# Sheet1.net
KiCad netlist of a schematic drawn in Altium Designer
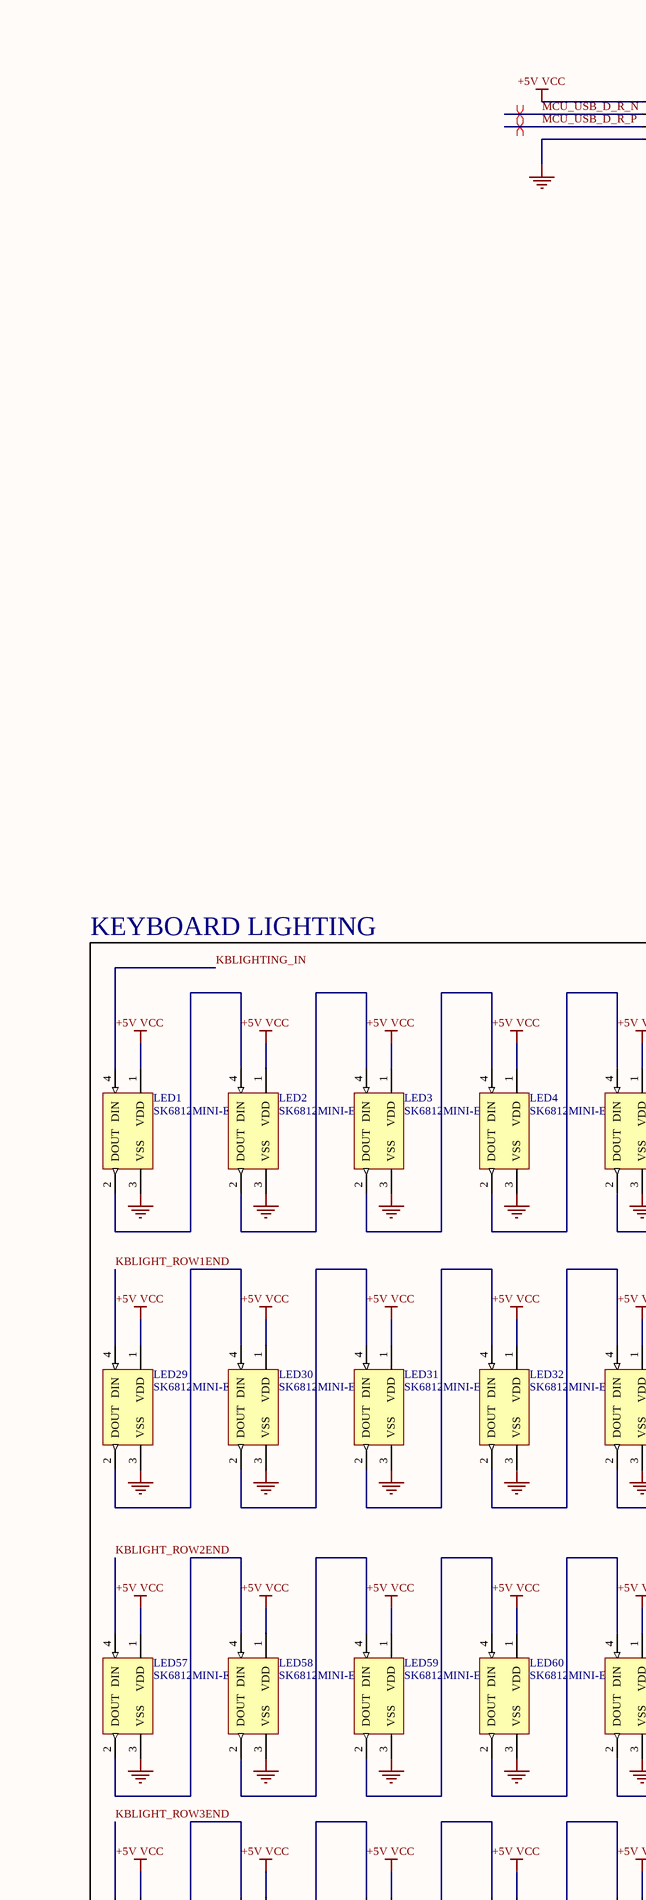
[diagram p0: Sheet1.SchDoc, top left]
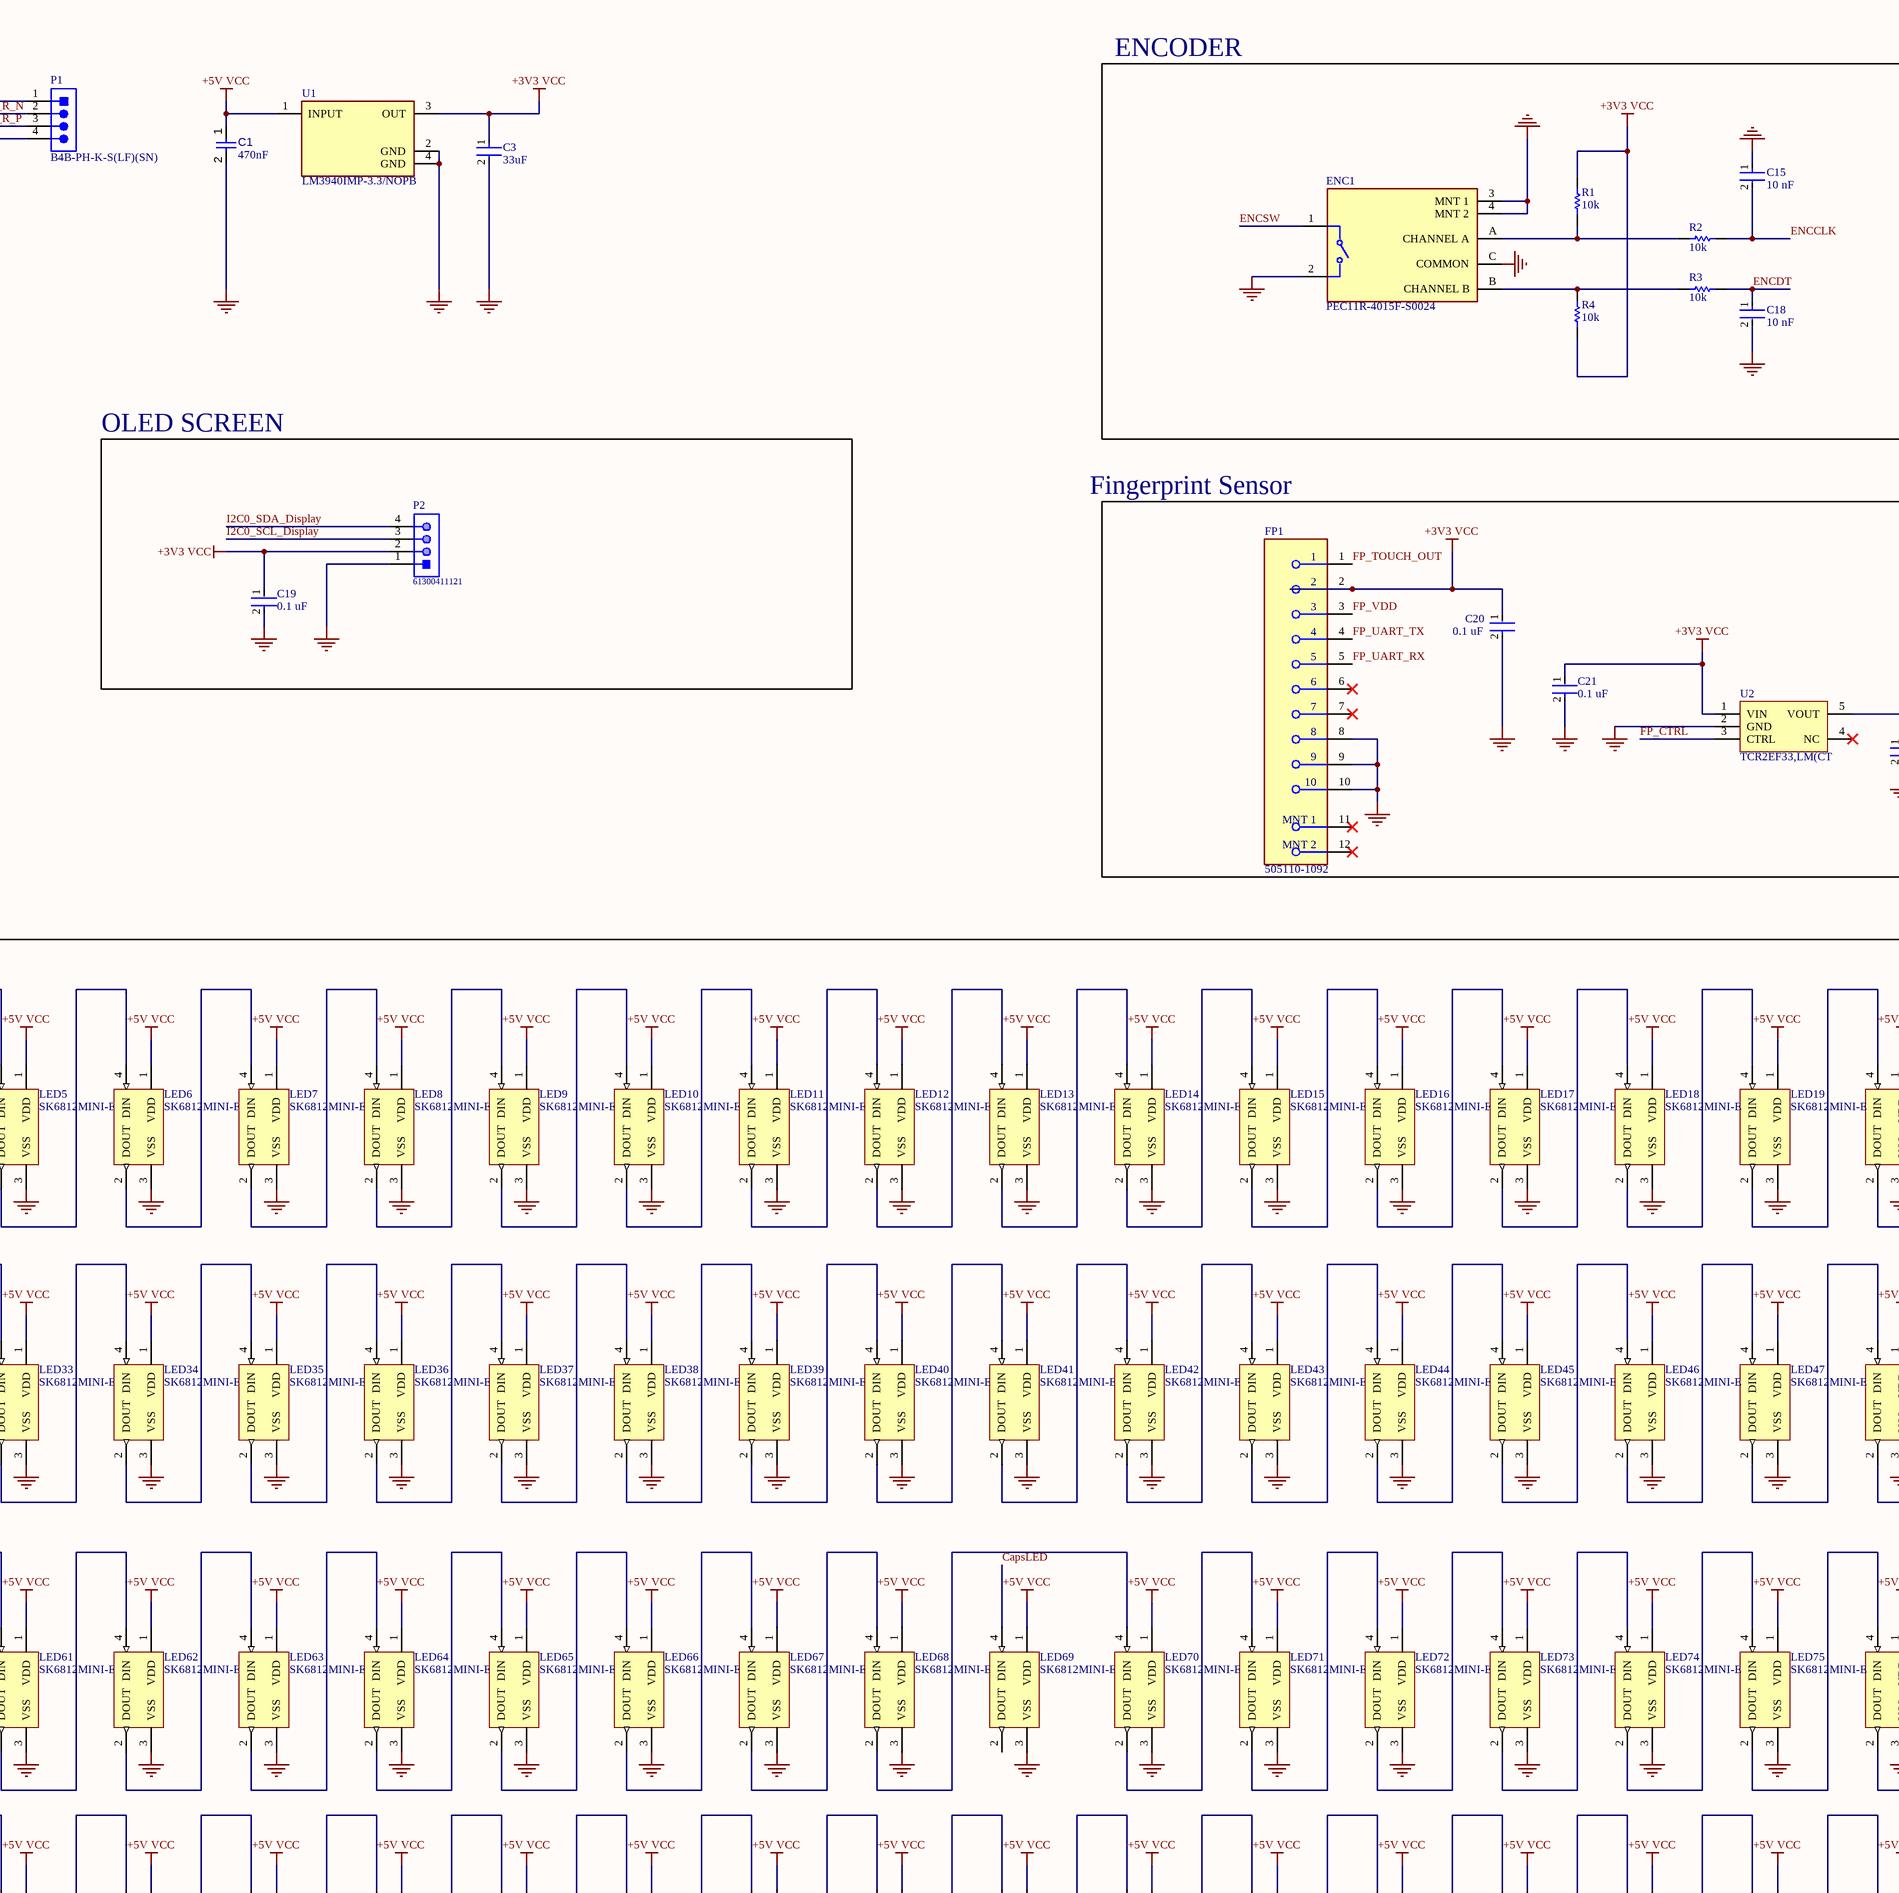
[diagram p1: Sheet1.SchDoc, top middle]
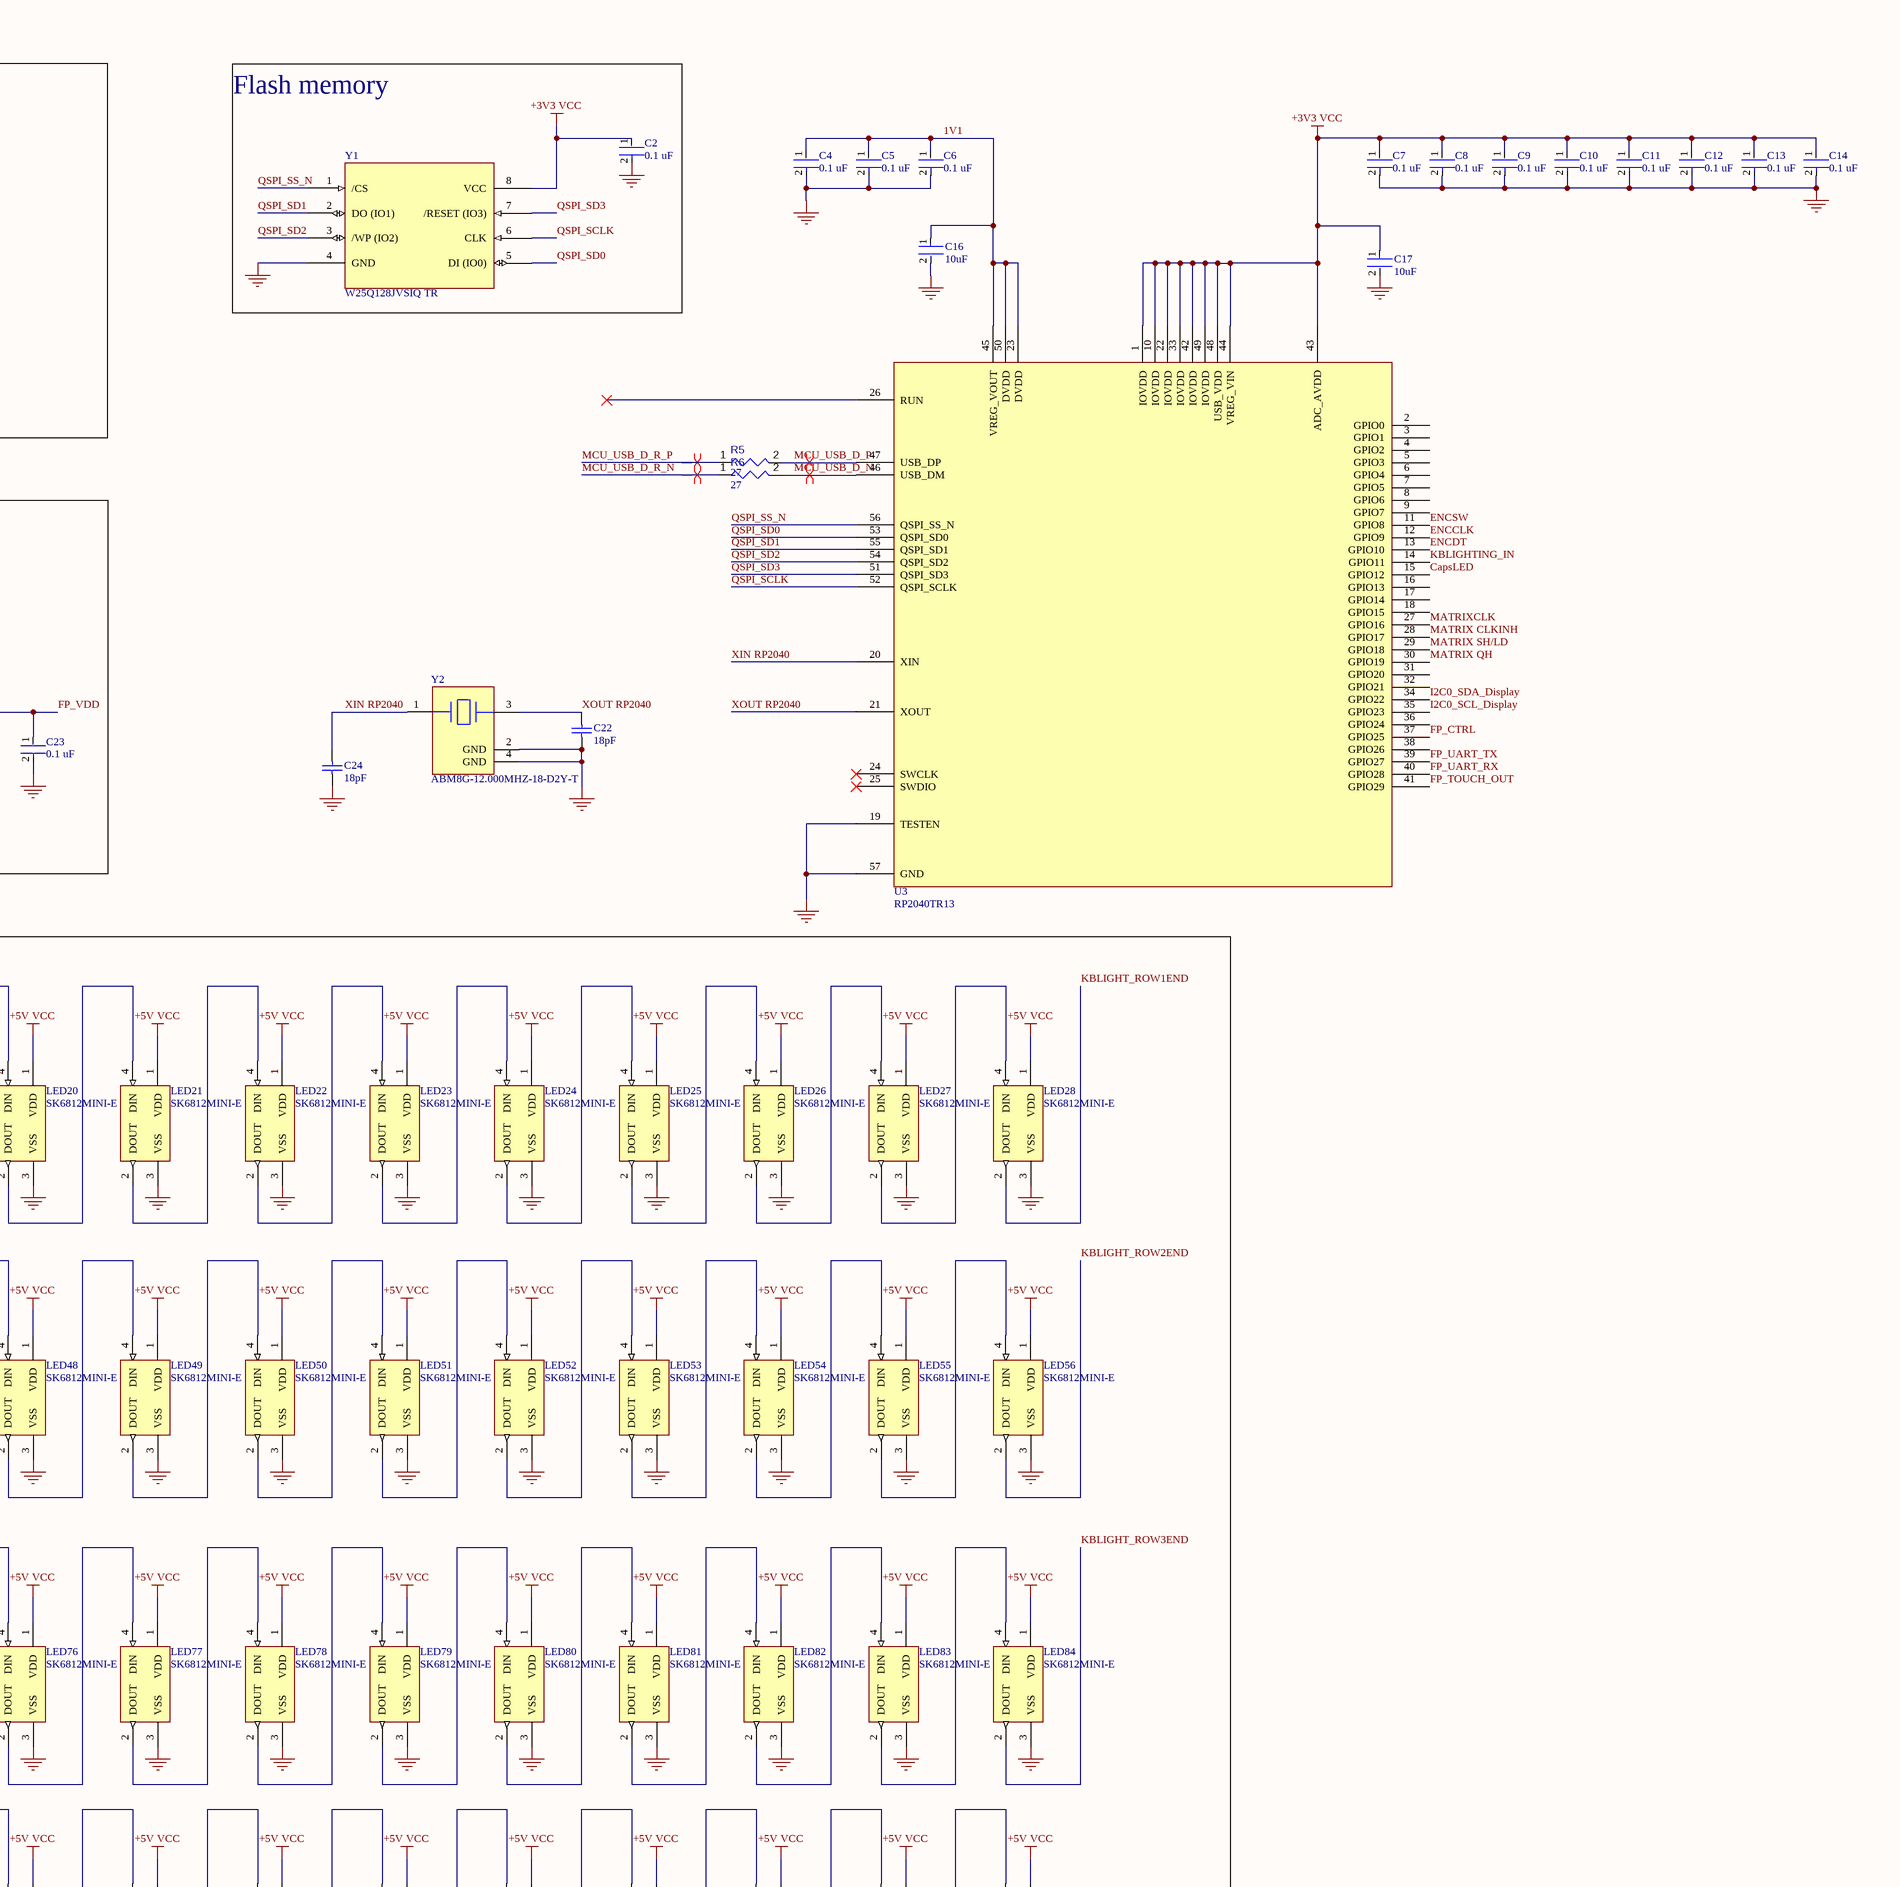
[diagram p2: Sheet1.SchDoc, top right]
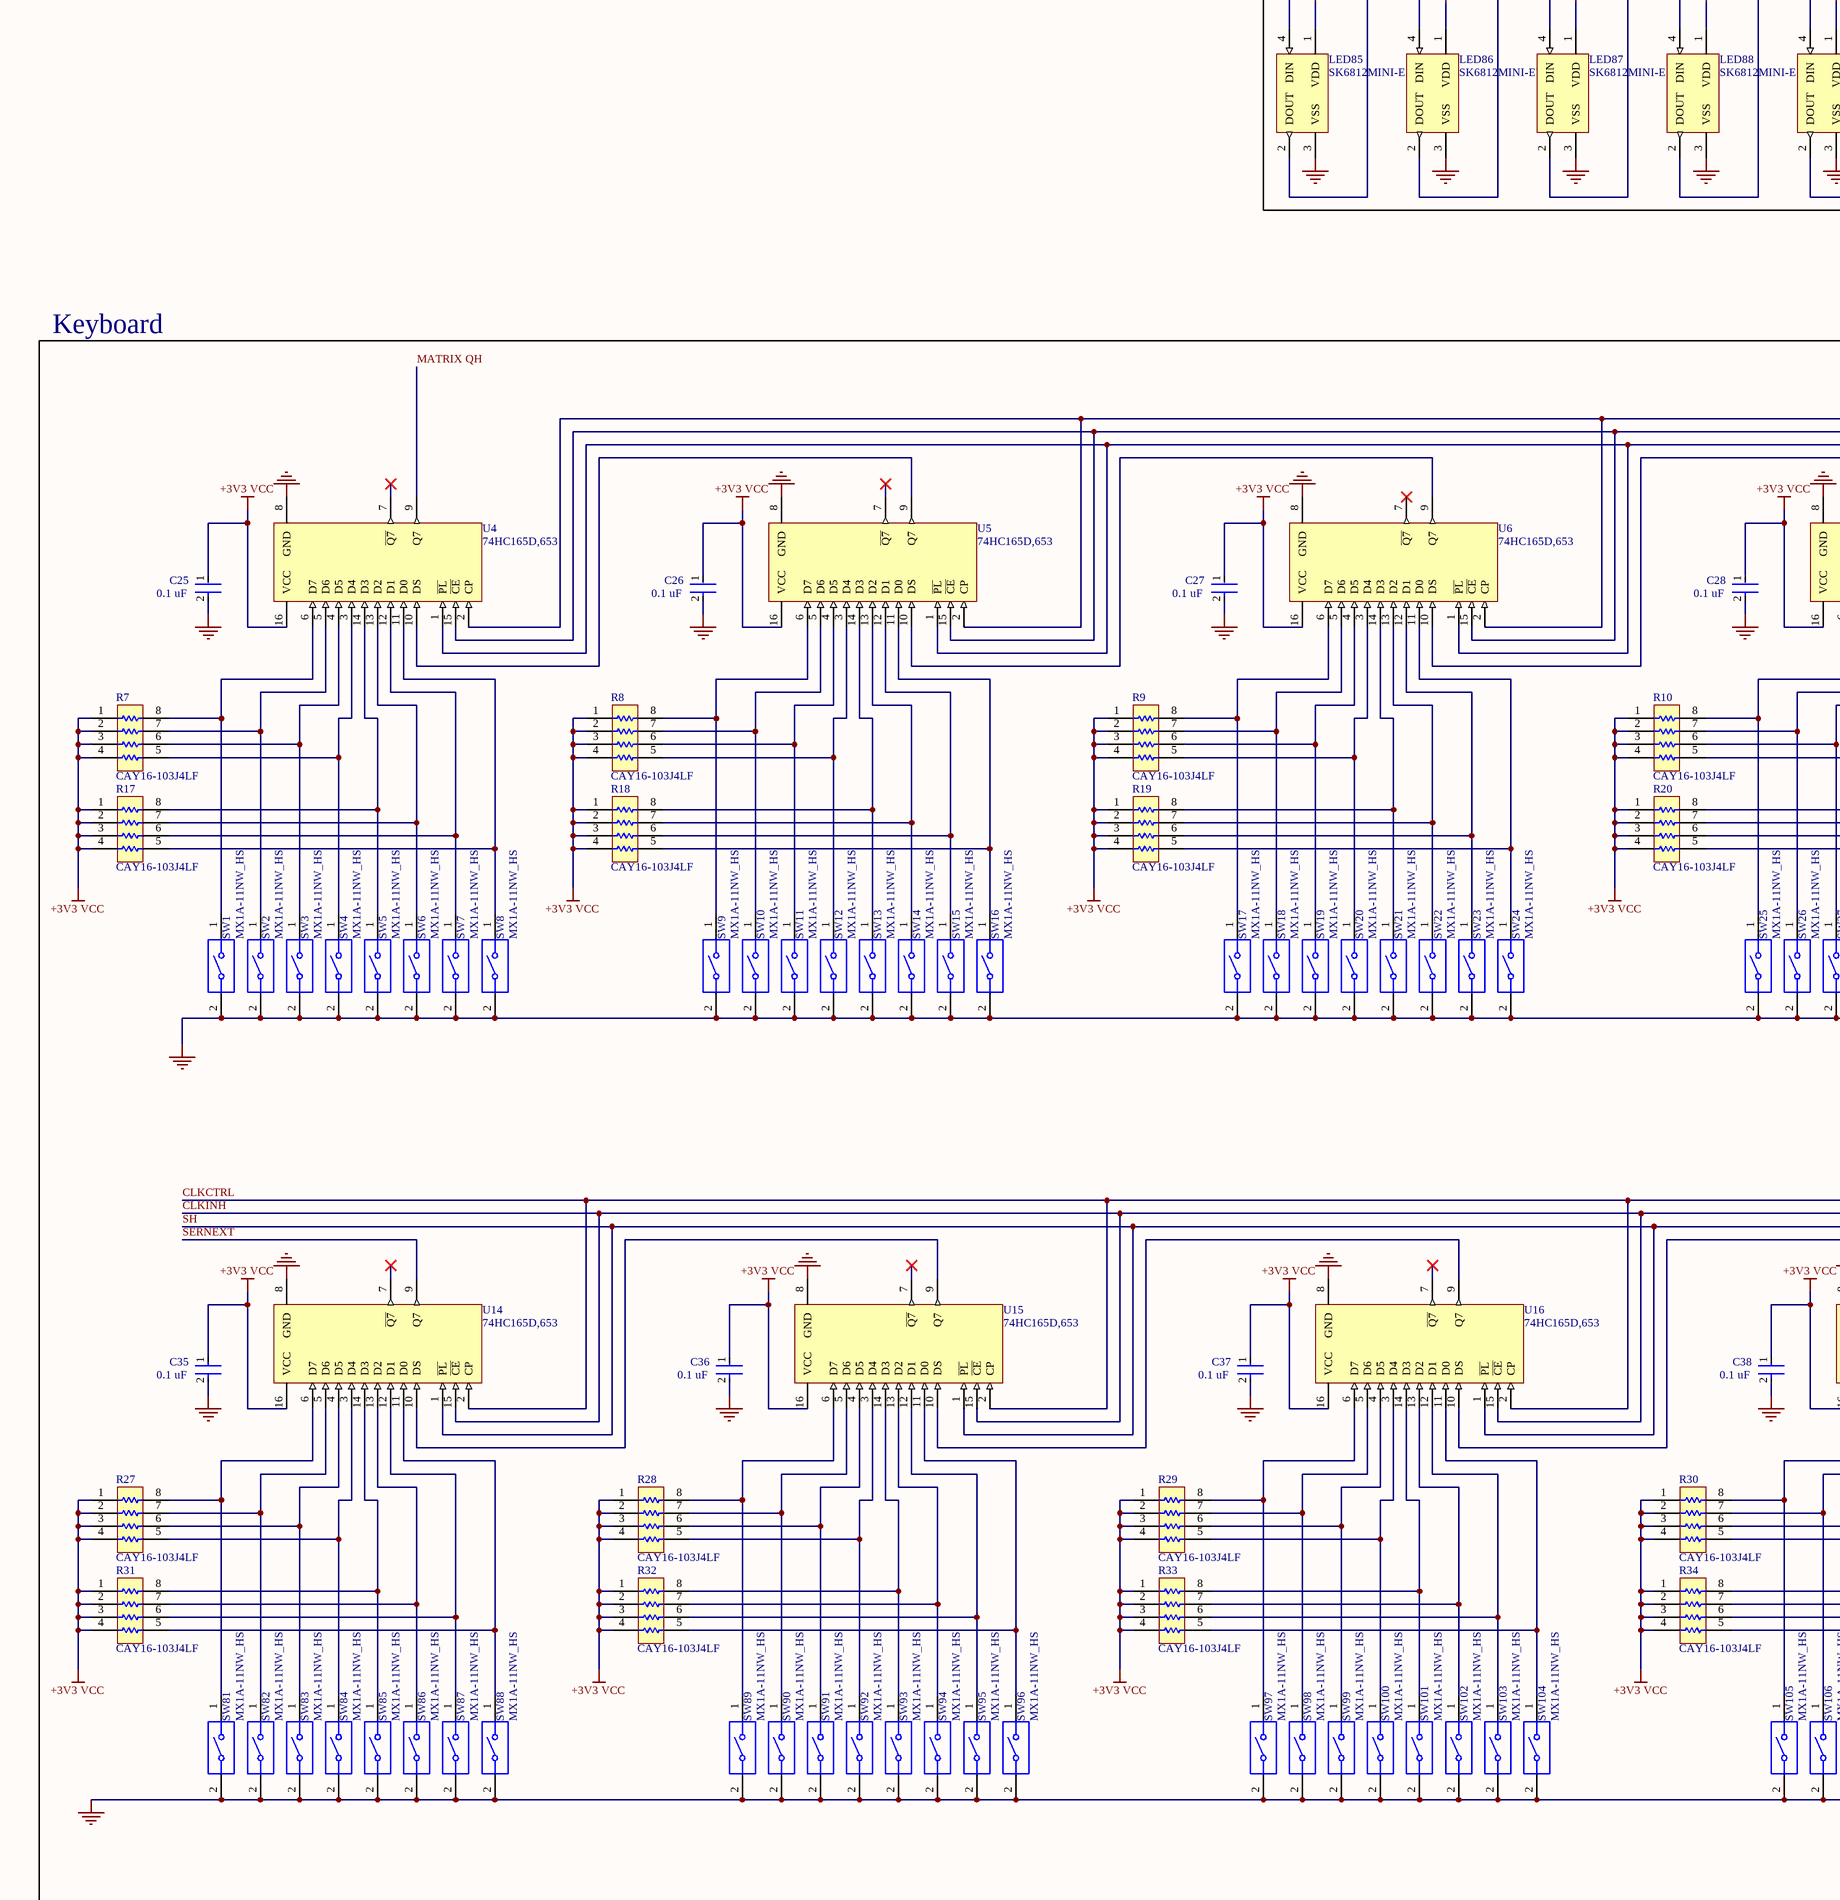
[diagram p3: Sheet1.SchDoc, bottom left]
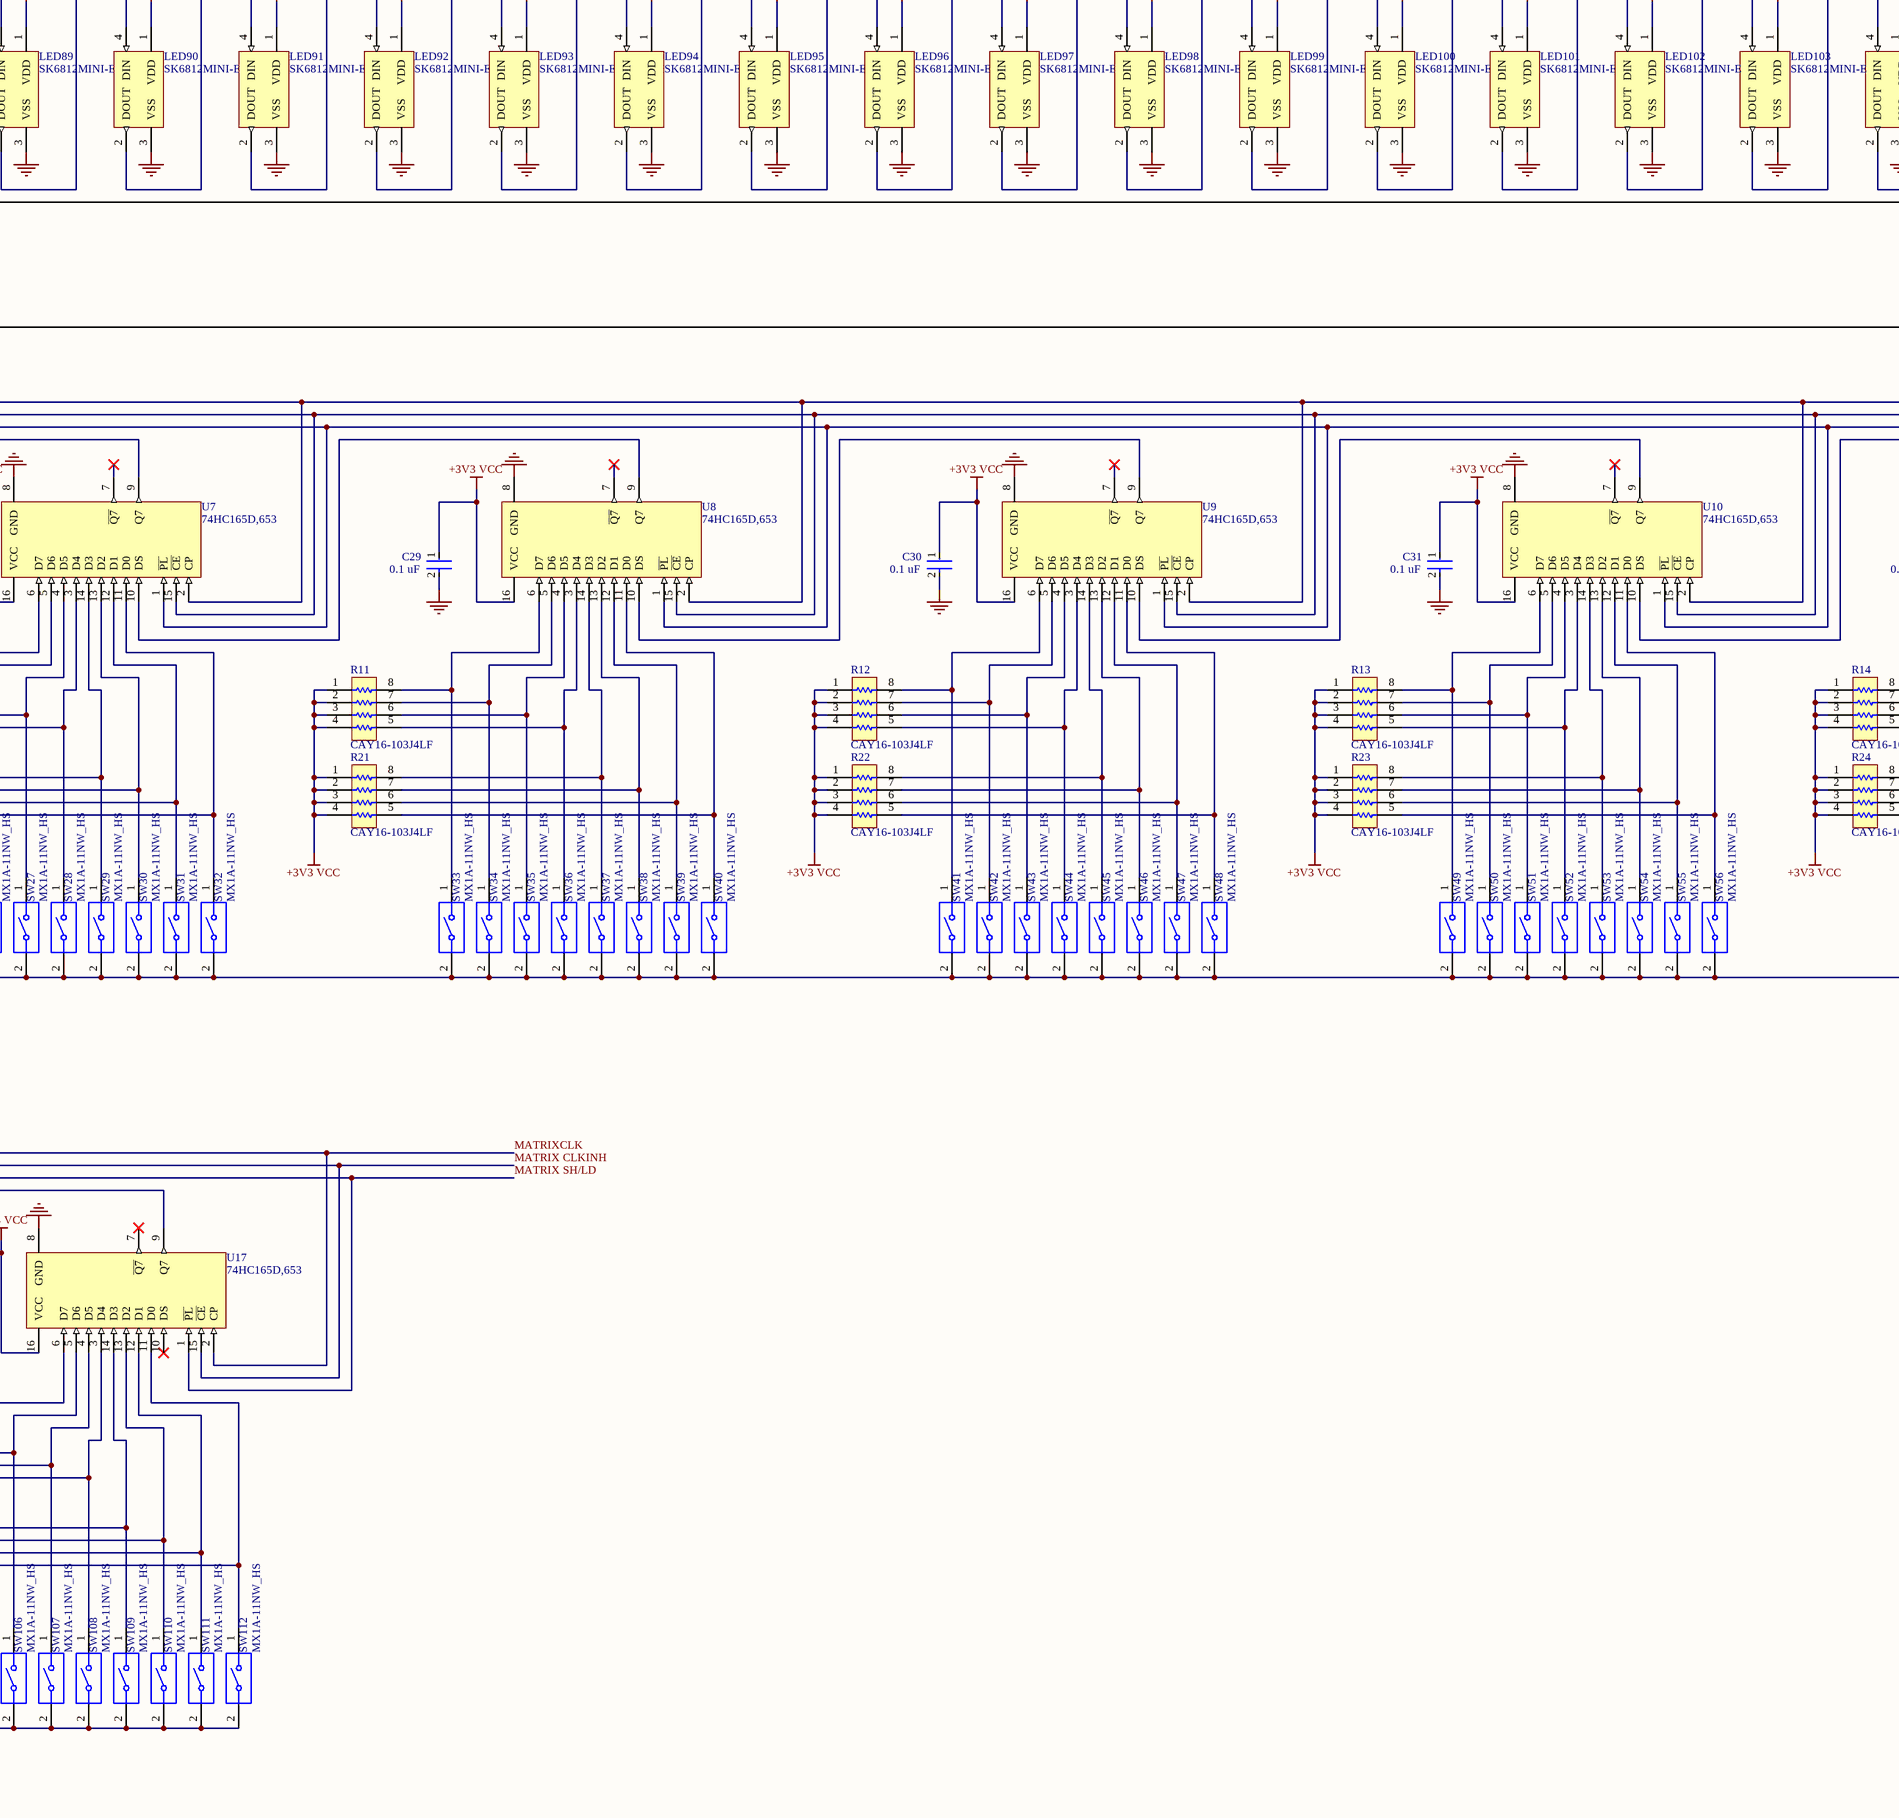
[diagram p4: Sheet1.SchDoc, bottom middle]
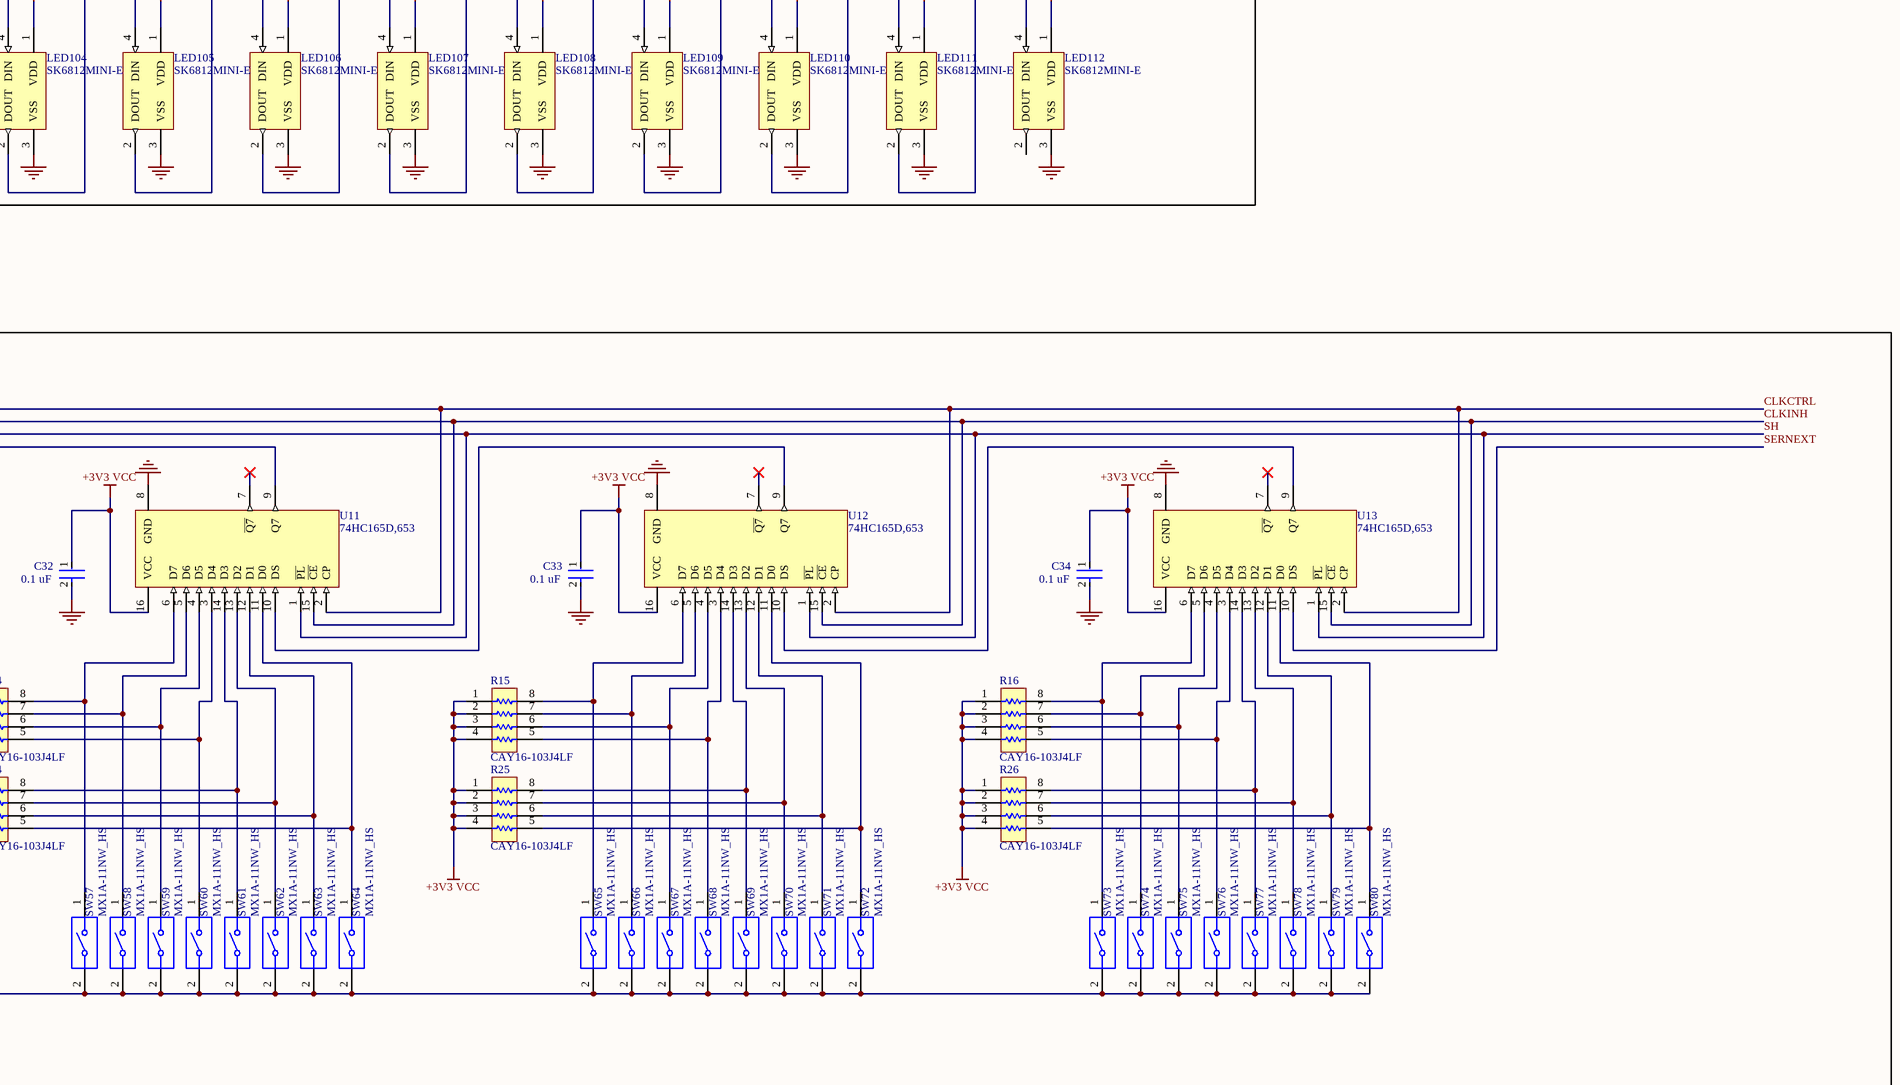
[diagram p5: Sheet1.SchDoc, bottom right]

(export (version "E")
  (design (tool "Eeschema 10.0.6"))
  (components
    (comp (ref "C1")
      (value "470nF")
      (footprint "CAPC0603(1608)100_L")
      (description "Chip Capacitor, 470nF +/-20%, 25V, 0603, Thickness 1 mm")
      (fields (field (name "TOLERANCE") "10%") (field (name "Comment") "Capacitor 470nF +/-20% 25V 0603"))
      (libsource (lib "Pennsylvania State University") (part "CAP-NP-2"))
    )
    (comp (ref "C2")
      (value "0.1 uF")
      (footprint "FP-GRM15-MFG")
      (description "CAP CER 0.1UF 16V X7R 0402\r\n GRM155R71C104KA88D")
      (fields (field (name "MANUFACTURER PART NUMBER") "GRM155R71C104KA88D") (field (name "TOLERANCE") "10%"))
      (libsource (lib "Altium Content Vault") (part "236180d848d6139a670b325ea6854c9"))
    )
    (comp (ref "C3")
      (value "33uF")
      (footprint "FP-C2012-125-0_2-IPC_A")
      (description "Multilayer Ceramic Capacitors 33μF ±20% 6.3V X5R SMD 0805\r\nC2012X5R0J336M125AC")
      (fields (field (name "TOLERANCE") "20%"))
      (libsource (lib "Altium Content Vault") (part "b4654b650e69147ec39a6b967a45e02"))
    )
    (comp (ref "C4")
      (value "0.1 uF")
      (footprint "FP-GRM15-MFG")
      (description "CAP CER 0.1UF 16V X7R 0402\r\n GRM155R71C104KA88D")
      (fields (field (name "MANUFACTURER PART NUMBER") "GRM155R71C104KA88D") (field (name "TOLERANCE") "10%"))
      (libsource (lib "Altium Content Vault") (part "236180d848d6139a670b325ea6854c9"))
    )
    (comp (ref "C5")
      (value "0.1 uF")
      (footprint "FP-GRM15-MFG")
      (description "CAP CER 0.1UF 16V X7R 0402\r\n GRM155R71C104KA88D")
      (fields (field (name "MANUFACTURER PART NUMBER") "GRM155R71C104KA88D") (field (name "TOLERANCE") "10%"))
      (libsource (lib "Altium Content Vault") (part "236180d848d6139a670b325ea6854c9"))
    )
    (comp (ref "C6")
      (value "0.1 uF")
      (footprint "FP-GRM15-MFG")
      (description "CAP CER 0.1UF 16V X7R 0402\r\n GRM155R71C104KA88D")
      (fields (field (name "MANUFACTURER PART NUMBER") "GRM155R71C104KA88D") (field (name "TOLERANCE") "10%"))
      (libsource (lib "Altium Content Vault") (part "236180d848d6139a670b325ea6854c9"))
    )
    (comp (ref "C7")
      (value "0.1 uF")
      (footprint "FP-GRM15-MFG")
      (description "CAP CER 0.1UF 16V X7R 0402\r\n GRM155R71C104KA88D")
      (fields (field (name "MANUFACTURER PART NUMBER") "GRM155R71C104KA88D") (field (name "TOLERANCE") "10%"))
      (libsource (lib "Altium Content Vault") (part "236180d848d6139a670b325ea6854c9"))
    )
    (comp (ref "C8")
      (value "0.1 uF")
      (footprint "FP-GRM15-MFG")
      (description "CAP CER 0.1UF 16V X7R 0402\r\n GRM155R71C104KA88D")
      (fields (field (name "MANUFACTURER PART NUMBER") "GRM155R71C104KA88D") (field (name "TOLERANCE") "10%"))
      (libsource (lib "Altium Content Vault") (part "236180d848d6139a670b325ea6854c9"))
    )
    (comp (ref "C9")
      (value "0.1 uF")
      (footprint "FP-GRM15-MFG")
      (description "CAP CER 0.1UF 16V X7R 0402\r\n GRM155R71C104KA88D")
      (fields (field (name "MANUFACTURER PART NUMBER") "GRM155R71C104KA88D") (field (name "TOLERANCE") "10%"))
      (libsource (lib "Altium Content Vault") (part "236180d848d6139a670b325ea6854c9"))
    )
    (comp (ref "C10")
      (value "0.1 uF")
      (footprint "FP-GRM15-MFG")
      (description "CAP CER 0.1UF 16V X7R 0402\r\n GRM155R71C104KA88D")
      (fields (field (name "MANUFACTURER PART NUMBER") "GRM155R71C104KA88D") (field (name "TOLERANCE") "10%"))
      (libsource (lib "Altium Content Vault") (part "236180d848d6139a670b325ea6854c9"))
    )
    (comp (ref "C11")
      (value "0.1 uF")
      (footprint "FP-GRM15-MFG")
      (description "CAP CER 0.1UF 16V X7R 0402\r\n GRM155R71C104KA88D")
      (fields (field (name "MANUFACTURER PART NUMBER") "GRM155R71C104KA88D") (field (name "TOLERANCE") "10%"))
      (libsource (lib "Altium Content Vault") (part "236180d848d6139a670b325ea6854c9"))
    )
    (comp (ref "C12")
      (value "0.1 uF")
      (footprint "FP-GRM15-MFG")
      (description "CAP CER 0.1UF 16V X7R 0402\r\n GRM155R71C104KA88D")
      (fields (field (name "MANUFACTURER PART NUMBER") "GRM155R71C104KA88D") (field (name "TOLERANCE") "10%"))
      (libsource (lib "Altium Content Vault") (part "236180d848d6139a670b325ea6854c9"))
    )
    (comp (ref "C13")
      (value "0.1 uF")
      (footprint "FP-GRM15-MFG")
      (description "CAP CER 0.1UF 16V X7R 0402\r\n GRM155R71C104KA88D")
      (fields (field (name "MANUFACTURER PART NUMBER") "GRM155R71C104KA88D") (field (name "TOLERANCE") "10%"))
      (libsource (lib "Altium Content Vault") (part "236180d848d6139a670b325ea6854c9"))
    )
    (comp (ref "C14")
      (value "0.1 uF")
      (footprint "FP-GRM15-MFG")
      (description "CAP CER 0.1UF 16V X7R 0402\r\n GRM155R71C104KA88D")
      (fields (field (name "MANUFACTURER PART NUMBER") "GRM155R71C104KA88D") (field (name "TOLERANCE") "10%"))
      (libsource (lib "Altium Content Vault") (part "236180d848d6139a670b325ea6854c9"))
    )
    (comp (ref "C15")
      (value "10 nF")
      (footprint "FP-GRM033-0_03-IPC_A")
      (fields (field (name "TOLERANCE") "10%") (field (name "VOLTAGE") "6.3V"))
      (libsource (lib "Altium Content Vault") (part "b4654b650e69147ec39a6b967a45e02"))
    )
    (comp (ref "C16")
      (value "10uF")
      (footprint "FP-GRM155-0_2-IPC_A")
      (libsource (lib "Altium Content Vault") (part "b4654b650e69147ec39a6b967a45e02"))
    )
    (comp (ref "C17")
      (value "10uF")
      (footprint "FP-GRM155-0_2-IPC_A")
      (libsource (lib "Altium Content Vault") (part "b4654b650e69147ec39a6b967a45e02"))
    )
    (comp (ref "C18")
      (value "10 nF")
      (footprint "FP-GRM033-0_03-IPC_A")
      (fields (field (name "TOLERANCE") "10%") (field (name "VOLTAGE") "6.3V"))
      (libsource (lib "Altium Content Vault") (part "b4654b650e69147ec39a6b967a45e02"))
    )
    (comp (ref "C19")
      (value "0.1 uF")
      (footprint "FP-GRM15-MFG")
      (description "CAP CER 0.1UF 16V X7R 0402\r\n GRM155R71C104KA88D")
      (fields (field (name "MANUFACTURER PART NUMBER") "GRM155R71C104KA88D") (field (name "TOLERANCE") "10%"))
      (libsource (lib "Altium Content Vault") (part "236180d848d6139a670b325ea6854c9"))
    )
    (comp (ref "C20")
      (value "0.1 uF")
      (footprint "FP-GRM15-MFG")
      (description "CAP CER 0.1UF 16V X7R 0402\r\n GRM155R71C104KA88D")
      (fields (field (name "MANUFACTURER PART NUMBER") "GRM155R71C104KA88D") (field (name "TOLERANCE") "10%"))
      (libsource (lib "Altium Content Vault") (part "236180d848d6139a670b325ea6854c9"))
    )
    (comp (ref "C21")
      (value "0.1 uF")
      (footprint "FP-GRM15-MFG")
      (description "CAP CER 0.1UF 16V X7R 0402\r\n GRM155R71C104KA88D")
      (fields (field (name "MANUFACTURER PART NUMBER") "GRM155R71C104KA88D") (field (name "TOLERANCE") "10%"))
      (libsource (lib "Altium Content Vault") (part "236180d848d6139a670b325ea6854c9"))
    )
    (comp (ref "C22")
      (value "18pF")
      (footprint "CAPC1608X90X35LL10T15")
      (fields (field (name "TOLERANCE") "±5%") (field (name "MANUFACTURER") "Murata"))
      (libsource (lib "Altium Content Vault") (part "CAP-NP-2"))
    )
    (comp (ref "C23")
      (value "0.1 uF")
      (footprint "FP-GRM15-MFG")
      (description "CAP CER 0.1UF 16V X7R 0402\r\n GRM155R71C104KA88D")
      (fields (field (name "MANUFACTURER PART NUMBER") "GRM155R71C104KA88D") (field (name "TOLERANCE") "10%"))
      (libsource (lib "Altium Content Vault") (part "236180d848d6139a670b325ea6854c9"))
    )
    (comp (ref "C24")
      (value "18pF")
      (footprint "CAPC1608X90X35LL10T15")
      (fields (field (name "TOLERANCE") "±5%") (field (name "MANUFACTURER") "Murata"))
      (libsource (lib "Altium Content Vault") (part "CAP-NP-2"))
    )
    (comp (ref "C25")
      (value "0.1 uF")
      (footprint "FP-GRM15-MFG")
      (description "CAP CER 0.1UF 16V X7R 0402\r\n GRM155R71C104KA88D")
      (fields (field (name "MANUFACTURER PART NUMBER") "GRM155R71C104KA88D") (field (name "TOLERANCE") "10%"))
      (libsource (lib "Altium Content Vault") (part "236180d848d6139a670b325ea6854c9"))
    )
    (comp (ref "C26")
      (value "0.1 uF")
      (footprint "FP-GRM15-MFG")
      (description "CAP CER 0.1UF 16V X7R 0402\r\n GRM155R71C104KA88D")
      (fields (field (name "MANUFACTURER PART NUMBER") "GRM155R71C104KA88D") (field (name "TOLERANCE") "10%"))
      (libsource (lib "Altium Content Vault") (part "236180d848d6139a670b325ea6854c9"))
    )
    (comp (ref "C27")
      (value "0.1 uF")
      (footprint "FP-GRM15-MFG")
      (description "CAP CER 0.1UF 16V X7R 0402\r\n GRM155R71C104KA88D")
      (fields (field (name "MANUFACTURER PART NUMBER") "GRM155R71C104KA88D") (field (name "TOLERANCE") "10%"))
      (libsource (lib "Altium Content Vault") (part "236180d848d6139a670b325ea6854c9"))
    )
    (comp (ref "C28")
      (value "0.1 uF")
      (footprint "FP-GRM15-MFG")
      (description "CAP CER 0.1UF 16V X7R 0402\r\n GRM155R71C104KA88D")
      (fields (field (name "MANUFACTURER PART NUMBER") "GRM155R71C104KA88D") (field (name "TOLERANCE") "10%"))
      (libsource (lib "Altium Content Vault") (part "236180d848d6139a670b325ea6854c9"))
    )
    (comp (ref "C29")
      (value "0.1 uF")
      (footprint "FP-GRM15-MFG")
      (description "CAP CER 0.1UF 16V X7R 0402\r\n GRM155R71C104KA88D")
      (fields (field (name "MANUFACTURER PART NUMBER") "GRM155R71C104KA88D") (field (name "TOLERANCE") "10%"))
      (libsource (lib "Altium Content Vault") (part "236180d848d6139a670b325ea6854c9"))
    )
    (comp (ref "C30")
      (value "0.1 uF")
      (footprint "FP-GRM15-MFG")
      (description "CAP CER 0.1UF 16V X7R 0402\r\n GRM155R71C104KA88D")
      (fields (field (name "MANUFACTURER PART NUMBER") "GRM155R71C104KA88D") (field (name "TOLERANCE") "10%"))
      (libsource (lib "Altium Content Vault") (part "236180d848d6139a670b325ea6854c9"))
    )
    (comp (ref "C31")
      (value "0.1 uF")
      (footprint "FP-GRM15-MFG")
      (description "CAP CER 0.1UF 16V X7R 0402\r\n GRM155R71C104KA88D")
      (fields (field (name "MANUFACTURER PART NUMBER") "GRM155R71C104KA88D") (field (name "TOLERANCE") "10%"))
      (libsource (lib "Altium Content Vault") (part "236180d848d6139a670b325ea6854c9"))
    )
    (comp (ref "C32")
      (value "0.1 uF")
      (footprint "FP-GRM15-MFG")
      (description "CAP CER 0.1UF 16V X7R 0402\r\n GRM155R71C104KA88D")
      (fields (field (name "MANUFACTURER PART NUMBER") "GRM155R71C104KA88D") (field (name "TOLERANCE") "10%"))
      (libsource (lib "Altium Content Vault") (part "236180d848d6139a670b325ea6854c9"))
    )
    (comp (ref "C33")
      (value "0.1 uF")
      (footprint "FP-GRM15-MFG")
      (description "CAP CER 0.1UF 16V X7R 0402\r\n GRM155R71C104KA88D")
      (fields (field (name "MANUFACTURER PART NUMBER") "GRM155R71C104KA88D") (field (name "TOLERANCE") "10%"))
      (libsource (lib "Altium Content Vault") (part "236180d848d6139a670b325ea6854c9"))
    )
    (comp (ref "C34")
      (value "0.1 uF")
      (footprint "FP-GRM15-MFG")
      (description "CAP CER 0.1UF 16V X7R 0402\r\n GRM155R71C104KA88D")
      (fields (field (name "MANUFACTURER PART NUMBER") "GRM155R71C104KA88D") (field (name "TOLERANCE") "10%"))
      (libsource (lib "Altium Content Vault") (part "236180d848d6139a670b325ea6854c9"))
    )
    (comp (ref "C35")
      (value "0.1 uF")
      (footprint "FP-GRM15-MFG")
      (description "CAP CER 0.1UF 16V X7R 0402\r\n GRM155R71C104KA88D")
      (fields (field (name "MANUFACTURER PART NUMBER") "GRM155R71C104KA88D") (field (name "TOLERANCE") "10%"))
      (libsource (lib "Altium Content Vault") (part "236180d848d6139a670b325ea6854c9"))
    )
    (comp (ref "C36")
      (value "0.1 uF")
      (footprint "FP-GRM15-MFG")
      (description "CAP CER 0.1UF 16V X7R 0402\r\n GRM155R71C104KA88D")
      (fields (field (name "MANUFACTURER PART NUMBER") "GRM155R71C104KA88D") (field (name "TOLERANCE") "10%"))
      (libsource (lib "Altium Content Vault") (part "236180d848d6139a670b325ea6854c9"))
    )
    (comp (ref "C37")
      (value "0.1 uF")
      (footprint "FP-GRM15-MFG")
      (description "CAP CER 0.1UF 16V X7R 0402\r\n GRM155R71C104KA88D")
      (fields (field (name "MANUFACTURER PART NUMBER") "GRM155R71C104KA88D") (field (name "TOLERANCE") "10%"))
      (libsource (lib "Altium Content Vault") (part "236180d848d6139a670b325ea6854c9"))
    )
    (comp (ref "C38")
      (value "0.1 uF")
      (footprint "FP-GRM15-MFG")
      (description "CAP CER 0.1UF 16V X7R 0402\r\n GRM155R71C104KA88D")
      (fields (field (name "MANUFACTURER PART NUMBER") "GRM155R71C104KA88D") (field (name "TOLERANCE") "10%"))
      (libsource (lib "Altium Content Vault") (part "236180d848d6139a670b325ea6854c9"))
    )
    (comp (ref "ENC1")
      (value "PEC11R-4015F-S0024")
      (footprint "FP-PEC11R-4015F-S0024-MFG")
      (description "ROTARY ENCODER MECHANICAL 24PPR")
      (libsource (lib "Altium Content Vault") (part "dd52def3fc7c65605180aef9223896d"))
    )
    (comp (ref "FP1")
      (value "505110-1092")
      (footprint "FP-505110-1092-MFG")
      (description "CONN FPC BOTTOM 10POS .5MM R/A")
      (libsource (lib "Altium Content Vault") (part "e361005953dc921e4dca60cbb3221aa"))
    )
    (comp (ref "LED1")
      (value "SK6812MINI-E")
      (footprint "1655-Footprint-1")
      (description "WS2812B 5050 RGB LED WITH INTEGRATED DRIVER CHIP PACK OF 10")
      (libsource (lib "Pennsylvania State University") (part "ADA-RGB-1655-4"))
    )
    (comp (ref "LED2")
      (value "SK6812MINI-E")
      (footprint "1655-Footprint-1")
      (description "WS2812B 5050 RGB LED WITH INTEGRATED DRIVER CHIP PACK OF 10")
      (libsource (lib "Pennsylvania State University") (part "ADA-RGB-1655-4"))
    )
    (comp (ref "LED3")
      (value "SK6812MINI-E")
      (footprint "1655-Footprint-1")
      (description "WS2812B 5050 RGB LED WITH INTEGRATED DRIVER CHIP PACK OF 10")
      (libsource (lib "Pennsylvania State University") (part "ADA-RGB-1655-4"))
    )
    (comp (ref "LED4")
      (value "SK6812MINI-E")
      (footprint "1655-Footprint-1")
      (description "WS2812B 5050 RGB LED WITH INTEGRATED DRIVER CHIP PACK OF 10")
      (libsource (lib "Pennsylvania State University") (part "ADA-RGB-1655-4"))
    )
    (comp (ref "LED5")
      (value "SK6812MINI-E")
      (footprint "1655-Footprint-1")
      (description "WS2812B 5050 RGB LED WITH INTEGRATED DRIVER CHIP PACK OF 10")
      (libsource (lib "Pennsylvania State University") (part "ADA-RGB-1655-4"))
    )
    (comp (ref "LED6")
      (value "SK6812MINI-E")
      (footprint "1655-Footprint-1")
      (description "WS2812B 5050 RGB LED WITH INTEGRATED DRIVER CHIP PACK OF 10")
      (libsource (lib "Pennsylvania State University") (part "ADA-RGB-1655-4"))
    )
    (comp (ref "LED7")
      (value "SK6812MINI-E")
      (footprint "1655-Footprint-1")
      (description "WS2812B 5050 RGB LED WITH INTEGRATED DRIVER CHIP PACK OF 10")
      (libsource (lib "Pennsylvania State University") (part "ADA-RGB-1655-4"))
    )
    (comp (ref "LED8")
      (value "SK6812MINI-E")
      (footprint "1655-Footprint-1")
      (description "WS2812B 5050 RGB LED WITH INTEGRATED DRIVER CHIP PACK OF 10")
      (libsource (lib "Pennsylvania State University") (part "ADA-RGB-1655-4"))
    )
    (comp (ref "LED9")
      (value "SK6812MINI-E")
      (footprint "1655-Footprint-1")
      (description "WS2812B 5050 RGB LED WITH INTEGRATED DRIVER CHIP PACK OF 10")
      (libsource (lib "Pennsylvania State University") (part "ADA-RGB-1655-4"))
    )
    (comp (ref "LED10")
      (value "SK6812MINI-E")
      (footprint "1655-Footprint-1")
      (description "WS2812B 5050 RGB LED WITH INTEGRATED DRIVER CHIP PACK OF 10")
      (libsource (lib "Pennsylvania State University") (part "ADA-RGB-1655-4"))
    )
    (comp (ref "LED11")
      (value "SK6812MINI-E")
      (footprint "1655-Footprint-1")
      (description "WS2812B 5050 RGB LED WITH INTEGRATED DRIVER CHIP PACK OF 10")
      (libsource (lib "Pennsylvania State University") (part "ADA-RGB-1655-4"))
    )
    (comp (ref "LED12")
      (value "SK6812MINI-E")
      (footprint "1655-Footprint-1")
      (description "WS2812B 5050 RGB LED WITH INTEGRATED DRIVER CHIP PACK OF 10")
      (libsource (lib "Pennsylvania State University") (part "ADA-RGB-1655-4"))
    )
    (comp (ref "LED13")
      (value "SK6812MINI-E")
      (footprint "1655-Footprint-1")
      (description "WS2812B 5050 RGB LED WITH INTEGRATED DRIVER CHIP PACK OF 10")
      (libsource (lib "Pennsylvania State University") (part "ADA-RGB-1655-4"))
    )
    (comp (ref "LED14")
      (value "SK6812MINI-E")
      (footprint "1655-Footprint-1")
      (description "WS2812B 5050 RGB LED WITH INTEGRATED DRIVER CHIP PACK OF 10")
      (libsource (lib "Pennsylvania State University") (part "ADA-RGB-1655-4"))
    )
    (comp (ref "LED15")
      (value "SK6812MINI-E")
      (footprint "1655-Footprint-1")
      (description "WS2812B 5050 RGB LED WITH INTEGRATED DRIVER CHIP PACK OF 10")
      (libsource (lib "Pennsylvania State University") (part "ADA-RGB-1655-4"))
    )
    (comp (ref "LED16")
      (value "SK6812MINI-E")
      (footprint "1655-Footprint-1")
      (description "WS2812B 5050 RGB LED WITH INTEGRATED DRIVER CHIP PACK OF 10")
      (libsource (lib "Pennsylvania State University") (part "ADA-RGB-1655-4"))
    )
    (comp (ref "LED17")
      (value "SK6812MINI-E")
      (footprint "1655-Footprint-1")
      (description "WS2812B 5050 RGB LED WITH INTEGRATED DRIVER CHIP PACK OF 10")
      (libsource (lib "Pennsylvania State University") (part "ADA-RGB-1655-4"))
    )
    (comp (ref "LED18")
      (value "SK6812MINI-E")
      (footprint "1655-Footprint-1")
      (description "WS2812B 5050 RGB LED WITH INTEGRATED DRIVER CHIP PACK OF 10")
      (libsource (lib "Pennsylvania State University") (part "ADA-RGB-1655-4"))
    )
    (comp (ref "LED19")
      (value "SK6812MINI-E")
      (footprint "1655-Footprint-1")
      (description "WS2812B 5050 RGB LED WITH INTEGRATED DRIVER CHIP PACK OF 10")
      (libsource (lib "Pennsylvania State University") (part "ADA-RGB-1655-4"))
    )
    (comp (ref "LED20")
      (value "SK6812MINI-E")
      (footprint "1655-Footprint-1")
      (description "WS2812B 5050 RGB LED WITH INTEGRATED DRIVER CHIP PACK OF 10")
      (libsource (lib "Pennsylvania State University") (part "ADA-RGB-1655-4"))
    )
    (comp (ref "LED21")
      (value "SK6812MINI-E")
      (footprint "1655-Footprint-1")
      (description "WS2812B 5050 RGB LED WITH INTEGRATED DRIVER CHIP PACK OF 10")
      (libsource (lib "Pennsylvania State University") (part "ADA-RGB-1655-4"))
    )
    (comp (ref "LED22")
      (value "SK6812MINI-E")
      (footprint "1655-Footprint-1")
      (description "WS2812B 5050 RGB LED WITH INTEGRATED DRIVER CHIP PACK OF 10")
      (libsource (lib "Pennsylvania State University") (part "ADA-RGB-1655-4"))
    )
    (comp (ref "LED23")
      (value "SK6812MINI-E")
      (footprint "1655-Footprint-1")
      (description "WS2812B 5050 RGB LED WITH INTEGRATED DRIVER CHIP PACK OF 10")
      (libsource (lib "Pennsylvania State University") (part "ADA-RGB-1655-4"))
    )
    (comp (ref "LED24")
      (value "SK6812MINI-E")
      (footprint "1655-Footprint-1")
      (description "WS2812B 5050 RGB LED WITH INTEGRATED DRIVER CHIP PACK OF 10")
      (libsource (lib "Pennsylvania State University") (part "ADA-RGB-1655-4"))
    )
    (comp (ref "LED25")
      (value "SK6812MINI-E")
      (footprint "1655-Footprint-1")
      (description "WS2812B 5050 RGB LED WITH INTEGRATED DRIVER CHIP PACK OF 10")
      (libsource (lib "Pennsylvania State University") (part "ADA-RGB-1655-4"))
    )
    (comp (ref "LED26")
      (value "SK6812MINI-E")
      (footprint "1655-Footprint-1")
      (description "WS2812B 5050 RGB LED WITH INTEGRATED DRIVER CHIP PACK OF 10")
      (libsource (lib "Pennsylvania State University") (part "ADA-RGB-1655-4"))
    )
    (comp (ref "LED27")
      (value "SK6812MINI-E")
      (footprint "1655-Footprint-1")
      (description "WS2812B 5050 RGB LED WITH INTEGRATED DRIVER CHIP PACK OF 10")
      (libsource (lib "Pennsylvania State University") (part "ADA-RGB-1655-4"))
    )
    (comp (ref "LED28")
      (value "SK6812MINI-E")
      (footprint "1655-Footprint-1")
      (description "WS2812B 5050 RGB LED WITH INTEGRATED DRIVER CHIP PACK OF 10")
      (libsource (lib "Pennsylvania State University") (part "ADA-RGB-1655-4"))
    )
    (comp (ref "LED29")
      (value "SK6812MINI-E")
      (footprint "1655-Footprint-1")
      (description "WS2812B 5050 RGB LED WITH INTEGRATED DRIVER CHIP PACK OF 10")
      (libsource (lib "Pennsylvania State University") (part "ADA-RGB-1655-4"))
    )
    (comp (ref "LED30")
      (value "SK6812MINI-E")
      (footprint "1655-Footprint-1")
      (description "WS2812B 5050 RGB LED WITH INTEGRATED DRIVER CHIP PACK OF 10")
      (libsource (lib "Pennsylvania State University") (part "ADA-RGB-1655-4"))
    )
    (comp (ref "LED31")
      (value "SK6812MINI-E")
      (footprint "1655-Footprint-1")
      (description "WS2812B 5050 RGB LED WITH INTEGRATED DRIVER CHIP PACK OF 10")
      (libsource (lib "Pennsylvania State University") (part "ADA-RGB-1655-4"))
    )
    (comp (ref "LED32")
      (value "SK6812MINI-E")
      (footprint "1655-Footprint-1")
      (description "WS2812B 5050 RGB LED WITH INTEGRATED DRIVER CHIP PACK OF 10")
      (libsource (lib "Pennsylvania State University") (part "ADA-RGB-1655-4"))
    )
    (comp (ref "LED33")
      (value "SK6812MINI-E")
      (footprint "1655-Footprint-1")
      (description "WS2812B 5050 RGB LED WITH INTEGRATED DRIVER CHIP PACK OF 10")
      (libsource (lib "Pennsylvania State University") (part "ADA-RGB-1655-4"))
    )
    (comp (ref "LED34")
      (value "SK6812MINI-E")
      (footprint "1655-Footprint-1")
      (description "WS2812B 5050 RGB LED WITH INTEGRATED DRIVER CHIP PACK OF 10")
      (libsource (lib "Pennsylvania State University") (part "ADA-RGB-1655-4"))
    )
    (comp (ref "LED35")
      (value "SK6812MINI-E")
      (footprint "1655-Footprint-1")
      (description "WS2812B 5050 RGB LED WITH INTEGRATED DRIVER CHIP PACK OF 10")
      (libsource (lib "Pennsylvania State University") (part "ADA-RGB-1655-4"))
    )
    (comp (ref "LED36")
      (value "SK6812MINI-E")
      (footprint "1655-Footprint-1")
      (description "WS2812B 5050 RGB LED WITH INTEGRATED DRIVER CHIP PACK OF 10")
      (libsource (lib "Pennsylvania State University") (part "ADA-RGB-1655-4"))
    )
    (comp (ref "LED37")
      (value "SK6812MINI-E")
      (footprint "1655-Footprint-1")
      (description "WS2812B 5050 RGB LED WITH INTEGRATED DRIVER CHIP PACK OF 10")
      (libsource (lib "Pennsylvania State University") (part "ADA-RGB-1655-4"))
    )
    (comp (ref "LED38")
      (value "SK6812MINI-E")
      (footprint "1655-Footprint-1")
      (description "WS2812B 5050 RGB LED WITH INTEGRATED DRIVER CHIP PACK OF 10")
      (libsource (lib "Pennsylvania State University") (part "ADA-RGB-1655-4"))
    )
    (comp (ref "LED39")
      (value "SK6812MINI-E")
      (footprint "1655-Footprint-1")
      (description "WS2812B 5050 RGB LED WITH INTEGRATED DRIVER CHIP PACK OF 10")
      (libsource (lib "Pennsylvania State University") (part "ADA-RGB-1655-4"))
    )
    (comp (ref "LED40")
      (value "SK6812MINI-E")
      (footprint "1655-Footprint-1")
      (description "WS2812B 5050 RGB LED WITH INTEGRATED DRIVER CHIP PACK OF 10")
      (libsource (lib "Pennsylvania State University") (part "ADA-RGB-1655-4"))
    )
    (comp (ref "LED41")
      (value "SK6812MINI-E")
      (footprint "1655-Footprint-1")
      (description "WS2812B 5050 RGB LED WITH INTEGRATED DRIVER CHIP PACK OF 10")
      (libsource (lib "Pennsylvania State University") (part "ADA-RGB-1655-4"))
    )
    (comp (ref "LED42")
      (value "SK6812MINI-E")
      (footprint "1655-Footprint-1")
      (description "WS2812B 5050 RGB LED WITH INTEGRATED DRIVER CHIP PACK OF 10")
      (libsource (lib "Pennsylvania State University") (part "ADA-RGB-1655-4"))
    )
    (comp (ref "LED43")
      (value "SK6812MINI-E")
      (footprint "1655-Footprint-1")
      (description "WS2812B 5050 RGB LED WITH INTEGRATED DRIVER CHIP PACK OF 10")
      (libsource (lib "Pennsylvania State University") (part "ADA-RGB-1655-4"))
    )
    (comp (ref "LED44")
      (value "SK6812MINI-E")
      (footprint "1655-Footprint-1")
      (description "WS2812B 5050 RGB LED WITH INTEGRATED DRIVER CHIP PACK OF 10")
      (libsource (lib "Pennsylvania State University") (part "ADA-RGB-1655-4"))
    )
    (comp (ref "LED45")
      (value "SK6812MINI-E")
      (footprint "1655-Footprint-1")
      (description "WS2812B 5050 RGB LED WITH INTEGRATED DRIVER CHIP PACK OF 10")
      (libsource (lib "Pennsylvania State University") (part "ADA-RGB-1655-4"))
    )
    (comp (ref "LED46")
      (value "SK6812MINI-E")
      (footprint "1655-Footprint-1")
      (description "WS2812B 5050 RGB LED WITH INTEGRATED DRIVER CHIP PACK OF 10")
      (libsource (lib "Pennsylvania State University") (part "ADA-RGB-1655-4"))
    )
    (comp (ref "LED47")
      (value "SK6812MINI-E")
      (footprint "1655-Footprint-1")
      (description "WS2812B 5050 RGB LED WITH INTEGRATED DRIVER CHIP PACK OF 10")
      (libsource (lib "Pennsylvania State University") (part "ADA-RGB-1655-4"))
    )
    (comp (ref "LED48")
      (value "SK6812MINI-E")
      (footprint "1655-Footprint-1")
      (description "WS2812B 5050 RGB LED WITH INTEGRATED DRIVER CHIP PACK OF 10")
      (libsource (lib "Pennsylvania State University") (part "ADA-RGB-1655-4"))
    )
    (comp (ref "LED49")
      (value "SK6812MINI-E")
      (footprint "1655-Footprint-1")
      (description "WS2812B 5050 RGB LED WITH INTEGRATED DRIVER CHIP PACK OF 10")
      (libsource (lib "Pennsylvania State University") (part "ADA-RGB-1655-4"))
    )
    (comp (ref "LED50")
      (value "SK6812MINI-E")
      (footprint "1655-Footprint-1")
      (description "WS2812B 5050 RGB LED WITH INTEGRATED DRIVER CHIP PACK OF 10")
      (libsource (lib "Pennsylvania State University") (part "ADA-RGB-1655-4"))
    )
    (comp (ref "LED51")
      (value "SK6812MINI-E")
      (footprint "1655-Footprint-1")
      (description "WS2812B 5050 RGB LED WITH INTEGRATED DRIVER CHIP PACK OF 10")
      (libsource (lib "Pennsylvania State University") (part "ADA-RGB-1655-4"))
    )
    (comp (ref "LED52")
      (value "SK6812MINI-E")
      (footprint "1655-Footprint-1")
      (description "WS2812B 5050 RGB LED WITH INTEGRATED DRIVER CHIP PACK OF 10")
      (libsource (lib "Pennsylvania State University") (part "ADA-RGB-1655-4"))
    )
    (comp (ref "LED53")
      (value "SK6812MINI-E")
      (footprint "1655-Footprint-1")
      (description "WS2812B 5050 RGB LED WITH INTEGRATED DRIVER CHIP PACK OF 10")
      (libsource (lib "Pennsylvania State University") (part "ADA-RGB-1655-4"))
    )
    (comp (ref "LED54")
      (value "SK6812MINI-E")
      (footprint "1655-Footprint-1")
      (description "WS2812B 5050 RGB LED WITH INTEGRATED DRIVER CHIP PACK OF 10")
      (libsource (lib "Pennsylvania State University") (part "ADA-RGB-1655-4"))
    )
    (comp (ref "LED55")
      (value "SK6812MINI-E")
      (footprint "1655-Footprint-1")
      (description "WS2812B 5050 RGB LED WITH INTEGRATED DRIVER CHIP PACK OF 10")
      (libsource (lib "Pennsylvania State University") (part "ADA-RGB-1655-4"))
    )
    (comp (ref "LED56")
      (value "SK6812MINI-E")
      (footprint "1655-Footprint-1")
      (description "WS2812B 5050 RGB LED WITH INTEGRATED DRIVER CHIP PACK OF 10")
      (libsource (lib "Pennsylvania State University") (part "ADA-RGB-1655-4"))
    )
    (comp (ref "LED57")
      (value "SK6812MINI-E")
      (footprint "1655-Footprint-1")
      (description "WS2812B 5050 RGB LED WITH INTEGRATED DRIVER CHIP PACK OF 10")
      (libsource (lib "Pennsylvania State University") (part "ADA-RGB-1655-4"))
    )
    (comp (ref "LED58")
      (value "SK6812MINI-E")
      (footprint "1655-Footprint-1")
      (description "WS2812B 5050 RGB LED WITH INTEGRATED DRIVER CHIP PACK OF 10")
      (libsource (lib "Pennsylvania State University") (part "ADA-RGB-1655-4"))
    )
    (comp (ref "LED59")
      (value "SK6812MINI-E")
      (footprint "1655-Footprint-1")
      (description "WS2812B 5050 RGB LED WITH INTEGRATED DRIVER CHIP PACK OF 10")
      (libsource (lib "Pennsylvania State University") (part "ADA-RGB-1655-4"))
    )
    (comp (ref "LED60")
      (value "SK6812MINI-E")
      (footprint "1655-Footprint-1")
      (description "WS2812B 5050 RGB LED WITH INTEGRATED DRIVER CHIP PACK OF 10")
      (libsource (lib "Pennsylvania State University") (part "ADA-RGB-1655-4"))
    )
    (comp (ref "LED61")
      (value "SK6812MINI-E")
      (footprint "1655-Footprint-1")
      (description "WS2812B 5050 RGB LED WITH INTEGRATED DRIVER CHIP PACK OF 10")
      (libsource (lib "Pennsylvania State University") (part "ADA-RGB-1655-4"))
    )
    (comp (ref "LED62")
      (value "SK6812MINI-E")
      (footprint "1655-Footprint-1")
      (description "WS2812B 5050 RGB LED WITH INTEGRATED DRIVER CHIP PACK OF 10")
      (libsource (lib "Pennsylvania State University") (part "ADA-RGB-1655-4"))
    )
    (comp (ref "LED63")
      (value "SK6812MINI-E")
      (footprint "1655-Footprint-1")
      (description "WS2812B 5050 RGB LED WITH INTEGRATED DRIVER CHIP PACK OF 10")
      (libsource (lib "Pennsylvania State University") (part "ADA-RGB-1655-4"))
    )
    (comp (ref "LED64")
      (value "SK6812MINI-E")
      (footprint "1655-Footprint-1")
      (description "WS2812B 5050 RGB LED WITH INTEGRATED DRIVER CHIP PACK OF 10")
      (libsource (lib "Pennsylvania State University") (part "ADA-RGB-1655-4"))
    )
    (comp (ref "LED65")
      (value "SK6812MINI-E")
      (footprint "1655-Footprint-1")
      (description "WS2812B 5050 RGB LED WITH INTEGRATED DRIVER CHIP PACK OF 10")
      (libsource (lib "Pennsylvania State University") (part "ADA-RGB-1655-4"))
    )
    (comp (ref "LED66")
      (value "SK6812MINI-E")
      (footprint "1655-Footprint-1")
      (description "WS2812B 5050 RGB LED WITH INTEGRATED DRIVER CHIP PACK OF 10")
      (libsource (lib "Pennsylvania State University") (part "ADA-RGB-1655-4"))
    )
    (comp (ref "LED67")
      (value "SK6812MINI-E")
      (footprint "1655-Footprint-1")
      (description "WS2812B 5050 RGB LED WITH INTEGRATED DRIVER CHIP PACK OF 10")
      (libsource (lib "Pennsylvania State University") (part "ADA-RGB-1655-4"))
    )
    (comp (ref "LED68")
      (value "SK6812MINI-E")
      (footprint "1655-Footprint-1")
      (description "WS2812B 5050 RGB LED WITH INTEGRATED DRIVER CHIP PACK OF 10")
      (libsource (lib "Pennsylvania State University") (part "ADA-RGB-1655-4"))
    )
    (comp (ref "LED69")
      (value "SK6812MINI-E")
      (footprint "1655-Footprint-1")
      (description "WS2812B 5050 RGB LED WITH INTEGRATED DRIVER CHIP PACK OF 10")
      (libsource (lib "Pennsylvania State University") (part "ADA-RGB-1655-4"))
    )
    (comp (ref "LED70")
      (value "SK6812MINI-E")
      (footprint "1655-Footprint-1")
      (description "WS2812B 5050 RGB LED WITH INTEGRATED DRIVER CHIP PACK OF 10")
      (libsource (lib "Pennsylvania State University") (part "ADA-RGB-1655-4"))
    )
    (comp (ref "LED71")
      (value "SK6812MINI-E")
      (footprint "1655-Footprint-1")
      (description "WS2812B 5050 RGB LED WITH INTEGRATED DRIVER CHIP PACK OF 10")
      (libsource (lib "Pennsylvania State University") (part "ADA-RGB-1655-4"))
    )
    (comp (ref "LED72")
      (value "SK6812MINI-E")
      (footprint "1655-Footprint-1")
      (description "WS2812B 5050 RGB LED WITH INTEGRATED DRIVER CHIP PACK OF 10")
      (libsource (lib "Pennsylvania State University") (part "ADA-RGB-1655-4"))
    )
    (comp (ref "LED73")
      (value "SK6812MINI-E")
      (footprint "1655-Footprint-1")
      (description "WS2812B 5050 RGB LED WITH INTEGRATED DRIVER CHIP PACK OF 10")
      (libsource (lib "Pennsylvania State University") (part "ADA-RGB-1655-4"))
    )
    (comp (ref "LED74")
      (value "SK6812MINI-E")
      (footprint "1655-Footprint-1")
      (description "WS2812B 5050 RGB LED WITH INTEGRATED DRIVER CHIP PACK OF 10")
      (libsource (lib "Pennsylvania State University") (part "ADA-RGB-1655-4"))
    )
    (comp (ref "LED75")
      (value "SK6812MINI-E")
      (footprint "1655-Footprint-1")
      (description "WS2812B 5050 RGB LED WITH INTEGRATED DRIVER CHIP PACK OF 10")
      (libsource (lib "Pennsylvania State University") (part "ADA-RGB-1655-4"))
    )
    (comp (ref "LED76")
      (value "SK6812MINI-E")
      (footprint "1655-Footprint-1")
      (description "WS2812B 5050 RGB LED WITH INTEGRATED DRIVER CHIP PACK OF 10")
      (libsource (lib "Pennsylvania State University") (part "ADA-RGB-1655-4"))
    )
    (comp (ref "LED77")
      (value "SK6812MINI-E")
      (footprint "1655-Footprint-1")
      (description "WS2812B 5050 RGB LED WITH INTEGRATED DRIVER CHIP PACK OF 10")
      (libsource (lib "Pennsylvania State University") (part "ADA-RGB-1655-4"))
    )
    (comp (ref "LED78")
      (value "SK6812MINI-E")
      (footprint "1655-Footprint-1")
      (description "WS2812B 5050 RGB LED WITH INTEGRATED DRIVER CHIP PACK OF 10")
      (libsource (lib "Pennsylvania State University") (part "ADA-RGB-1655-4"))
    )
    (comp (ref "LED79")
      (value "SK6812MINI-E")
      (footprint "1655-Footprint-1")
      (description "WS2812B 5050 RGB LED WITH INTEGRATED DRIVER CHIP PACK OF 10")
      (libsource (lib "Pennsylvania State University") (part "ADA-RGB-1655-4"))
    )
    (comp (ref "LED80")
      (value "SK6812MINI-E")
      (footprint "1655-Footprint-1")
      (description "WS2812B 5050 RGB LED WITH INTEGRATED DRIVER CHIP PACK OF 10")
      (libsource (lib "Pennsylvania State University") (part "ADA-RGB-1655-4"))
    )
    (comp (ref "LED81")
      (value "SK6812MINI-E")
      (footprint "1655-Footprint-1")
      (description "WS2812B 5050 RGB LED WITH INTEGRATED DRIVER CHIP PACK OF 10")
      (libsource (lib "Pennsylvania State University") (part "ADA-RGB-1655-4"))
    )
    (comp (ref "LED82")
      (value "SK6812MINI-E")
      (footprint "1655-Footprint-1")
      (description "WS2812B 5050 RGB LED WITH INTEGRATED DRIVER CHIP PACK OF 10")
      (libsource (lib "Pennsylvania State University") (part "ADA-RGB-1655-4"))
    )
    (comp (ref "LED83")
      (value "SK6812MINI-E")
      (footprint "1655-Footprint-1")
      (description "WS2812B 5050 RGB LED WITH INTEGRATED DRIVER CHIP PACK OF 10")
      (libsource (lib "Pennsylvania State University") (part "ADA-RGB-1655-4"))
    )
    (comp (ref "LED84")
      (value "SK6812MINI-E")
      (footprint "1655-Footprint-1")
      (description "WS2812B 5050 RGB LED WITH INTEGRATED DRIVER CHIP PACK OF 10")
      (libsource (lib "Pennsylvania State University") (part "ADA-RGB-1655-4"))
    )
    (comp (ref "LED85")
      (value "SK6812MINI-E")
      (footprint "1655-Footprint-1")
      (description "WS2812B 5050 RGB LED WITH INTEGRATED DRIVER CHIP PACK OF 10")
      (libsource (lib "Pennsylvania State University") (part "ADA-RGB-1655-4"))
    )
    (comp (ref "LED86")
      (value "SK6812MINI-E")
      (footprint "1655-Footprint-1")
      (description "WS2812B 5050 RGB LED WITH INTEGRATED DRIVER CHIP PACK OF 10")
      (libsource (lib "Pennsylvania State University") (part "ADA-RGB-1655-4"))
    )
    (comp (ref "LED87")
      (value "SK6812MINI-E")
      (footprint "1655-Footprint-1")
      (description "WS2812B 5050 RGB LED WITH INTEGRATED DRIVER CHIP PACK OF 10")
      (libsource (lib "Pennsylvania State University") (part "ADA-RGB-1655-4"))
    )
    (comp (ref "LED88")
      (value "SK6812MINI-E")
      (footprint "1655-Footprint-1")
      (description "WS2812B 5050 RGB LED WITH INTEGRATED DRIVER CHIP PACK OF 10")
      (libsource (lib "Pennsylvania State University") (part "ADA-RGB-1655-4"))
    )
    (comp (ref "LED89")
      (value "SK6812MINI-E")
      (footprint "1655-Footprint-1")
      (description "WS2812B 5050 RGB LED WITH INTEGRATED DRIVER CHIP PACK OF 10")
      (libsource (lib "Pennsylvania State University") (part "ADA-RGB-1655-4"))
    )
    (comp (ref "LED90")
      (value "SK6812MINI-E")
      (footprint "1655-Footprint-1")
      (description "WS2812B 5050 RGB LED WITH INTEGRATED DRIVER CHIP PACK OF 10")
      (libsource (lib "Pennsylvania State University") (part "ADA-RGB-1655-4"))
    )
    (comp (ref "LED91")
      (value "SK6812MINI-E")
      (footprint "1655-Footprint-1")
      (description "WS2812B 5050 RGB LED WITH INTEGRATED DRIVER CHIP PACK OF 10")
      (libsource (lib "Pennsylvania State University") (part "ADA-RGB-1655-4"))
    )
    (comp (ref "LED92")
      (value "SK6812MINI-E")
      (footprint "1655-Footprint-1")
      (description "WS2812B 5050 RGB LED WITH INTEGRATED DRIVER CHIP PACK OF 10")
      (libsource (lib "Pennsylvania State University") (part "ADA-RGB-1655-4"))
    )
    (comp (ref "LED93")
      (value "SK6812MINI-E")
      (footprint "1655-Footprint-1")
      (description "WS2812B 5050 RGB LED WITH INTEGRATED DRIVER CHIP PACK OF 10")
      (libsource (lib "Pennsylvania State University") (part "ADA-RGB-1655-4"))
    )
    (comp (ref "LED94")
      (value "SK6812MINI-E")
      (footprint "1655-Footprint-1")
      (description "WS2812B 5050 RGB LED WITH INTEGRATED DRIVER CHIP PACK OF 10")
      (libsource (lib "Pennsylvania State University") (part "ADA-RGB-1655-4"))
    )
    (comp (ref "LED95")
      (value "SK6812MINI-E")
      (footprint "1655-Footprint-1")
      (description "WS2812B 5050 RGB LED WITH INTEGRATED DRIVER CHIP PACK OF 10")
      (libsource (lib "Pennsylvania State University") (part "ADA-RGB-1655-4"))
    )
    (comp (ref "LED96")
      (value "SK6812MINI-E")
      (footprint "1655-Footprint-1")
      (description "WS2812B 5050 RGB LED WITH INTEGRATED DRIVER CHIP PACK OF 10")
      (libsource (lib "Pennsylvania State University") (part "ADA-RGB-1655-4"))
    )
    (comp (ref "LED97")
      (value "SK6812MINI-E")
      (footprint "1655-Footprint-1")
      (description "WS2812B 5050 RGB LED WITH INTEGRATED DRIVER CHIP PACK OF 10")
      (libsource (lib "Pennsylvania State University") (part "ADA-RGB-1655-4"))
    )
    (comp (ref "LED98")
      (value "SK6812MINI-E")
      (footprint "1655-Footprint-1")
      (description "WS2812B 5050 RGB LED WITH INTEGRATED DRIVER CHIP PACK OF 10")
      (libsource (lib "Pennsylvania State University") (part "ADA-RGB-1655-4"))
    )
    (comp (ref "LED99")
      (value "SK6812MINI-E")
      (footprint "1655-Footprint-1")
      (description "WS2812B 5050 RGB LED WITH INTEGRATED DRIVER CHIP PACK OF 10")
      (libsource (lib "Pennsylvania State University") (part "ADA-RGB-1655-4"))
    )
    (comp (ref "LED100")
      (value "SK6812MINI-E")
      (footprint "1655-Footprint-1")
      (description "WS2812B 5050 RGB LED WITH INTEGRATED DRIVER CHIP PACK OF 10")
      (libsource (lib "Pennsylvania State University") (part "ADA-RGB-1655-4"))
    )
    (comp (ref "LED101")
      (value "SK6812MINI-E")
      (footprint "1655-Footprint-1")
      (description "WS2812B 5050 RGB LED WITH INTEGRATED DRIVER CHIP PACK OF 10")
      (libsource (lib "Pennsylvania State University") (part "ADA-RGB-1655-4"))
    )
    (comp (ref "LED102")
      (value "SK6812MINI-E")
      (footprint "1655-Footprint-1")
      (description "WS2812B 5050 RGB LED WITH INTEGRATED DRIVER CHIP PACK OF 10")
      (libsource (lib "Pennsylvania State University") (part "ADA-RGB-1655-4"))
    )
    (comp (ref "LED103")
      (value "SK6812MINI-E")
      (footprint "1655-Footprint-1")
      (description "WS2812B 5050 RGB LED WITH INTEGRATED DRIVER CHIP PACK OF 10")
      (libsource (lib "Pennsylvania State University") (part "ADA-RGB-1655-4"))
    )
    (comp (ref "LED104")
      (value "SK6812MINI-E")
      (footprint "1655-Footprint-1")
      (description "WS2812B 5050 RGB LED WITH INTEGRATED DRIVER CHIP PACK OF 10")
      (libsource (lib "Pennsylvania State University") (part "ADA-RGB-1655-4"))
    )
    (comp (ref "LED105")
      (value "SK6812MINI-E")
      (footprint "1655-Footprint-1")
      (description "WS2812B 5050 RGB LED WITH INTEGRATED DRIVER CHIP PACK OF 10")
      (libsource (lib "Pennsylvania State University") (part "ADA-RGB-1655-4"))
    )
    (comp (ref "LED106")
      (value "SK6812MINI-E")
      (footprint "1655-Footprint-1")
      (description "WS2812B 5050 RGB LED WITH INTEGRATED DRIVER CHIP PACK OF 10")
      (libsource (lib "Pennsylvania State University") (part "ADA-RGB-1655-4"))
    )
    (comp (ref "LED107")
      (value "SK6812MINI-E")
      (footprint "1655-Footprint-1")
      (description "WS2812B 5050 RGB LED WITH INTEGRATED DRIVER CHIP PACK OF 10")
      (libsource (lib "Pennsylvania State University") (part "ADA-RGB-1655-4"))
    )
    (comp (ref "LED108")
      (value "SK6812MINI-E")
      (footprint "1655-Footprint-1")
      (description "WS2812B 5050 RGB LED WITH INTEGRATED DRIVER CHIP PACK OF 10")
      (libsource (lib "Pennsylvania State University") (part "ADA-RGB-1655-4"))
    )
    (comp (ref "LED109")
      (value "SK6812MINI-E")
      (footprint "1655-Footprint-1")
      (description "WS2812B 5050 RGB LED WITH INTEGRATED DRIVER CHIP PACK OF 10")
      (libsource (lib "Pennsylvania State University") (part "ADA-RGB-1655-4"))
    )
    (comp (ref "LED110")
      (value "SK6812MINI-E")
      (footprint "1655-Footprint-1")
      (description "WS2812B 5050 RGB LED WITH INTEGRATED DRIVER CHIP PACK OF 10")
      (libsource (lib "Pennsylvania State University") (part "ADA-RGB-1655-4"))
    )
    (comp (ref "LED111")
      (value "SK6812MINI-E")
      (footprint "1655-Footprint-1")
      (description "WS2812B 5050 RGB LED WITH INTEGRATED DRIVER CHIP PACK OF 10")
      (libsource (lib "Pennsylvania State University") (part "ADA-RGB-1655-4"))
    )
    (comp (ref "LED112")
      (value "SK6812MINI-E")
      (footprint "1655-Footprint-1")
      (description "WS2812B 5050 RGB LED WITH INTEGRATED DRIVER CHIP PACK OF 10")
      (libsource (lib "Pennsylvania State University") (part "ADA-RGB-1655-4"))
    )
    (comp (ref "P1")
      (value "B4B-PH-K-S(LF)(SN)")
      (footprint "JST-B4B-PH-K-S_V")
      (fields (field (name "MANUFACTURER") "JST"))
      (libsource (lib "Altium Content Vault") (part "CN-1P-M-R4"))
    )
    (comp (ref "P2")
      (value "61300411121")
      (footprint "61300411121")
      (description "THT Vertical Pin Header WR-PHD, Pitch 2.54 mm, Single Row, 4 pins")
      (fields (field (name "MANUFACTURER") "Wurth Elektronik") (field (name "PUBLISHER") "WurthElektronik"))
      (libsource (lib "Altium Content Vault") (part "WE-CN-1P-M-R4"))
    )
    (comp (ref "R1")
      (value "10k")
      (footprint "RESC1005X40X25ML05T05")
      (description "ERJ-2GEJ103X\r\n10kohm resistor")
      (fields (field (name "PART NUMBER") "ERJ-2GEJ103X") (field (name "MANUFACTURER") "Panasonic"))
      (libsource (lib "Altium Content Vault") (part "RES"))
    )
    (comp (ref "R2")
      (value "10k")
      (footprint "RESC1005X40X25ML05T05")
      (description "ERJ-2GEJ103X\r\n10kohm resistor")
      (fields (field (name "PART NUMBER") "ERJ-2GEJ103X") (field (name "MANUFACTURER") "Panasonic"))
      (libsource (lib "Altium Content Vault") (part "RES"))
    )
    (comp (ref "R3")
      (value "10k")
      (footprint "RESC1005X40X25ML05T05")
      (description "ERJ-2GEJ103X\r\n10kohm resistor")
      (fields (field (name "PART NUMBER") "ERJ-2GEJ103X") (field (name "MANUFACTURER") "Panasonic"))
      (libsource (lib "Altium Content Vault") (part "RES"))
    )
    (comp (ref "R4")
      (value "10k")
      (footprint "RESC1005X40X25ML05T05")
      (description "ERJ-2GEJ103X\r\n10kohm resistor")
      (fields (field (name "PART NUMBER") "ERJ-2GEJ103X") (field (name "MANUFACTURER") "Panasonic"))
      (libsource (lib "Altium Content Vault") (part "RES"))
    )
    (comp (ref "R5")
      (value "27")
      (footprint "RESC1005X40X25NL05T10")
      (fields
        (field (name "POWER") "62.5mW")
        (field (name "TOLERANCE") "1%")
        (field (name "Comment") "RC0402FR-0727RL")
      )
      (libsource (lib "Pennsylvania State University") (part "RES-2"))
    )
    (comp (ref "R6")
      (value "27")
      (footprint "RESC1005X40X25NL05T10")
      (fields
        (field (name "POWER") "62.5mW")
        (field (name "TOLERANCE") "1%")
        (field (name "Comment") "RC0402FR-0727RL")
      )
      (libsource (lib "Pennsylvania State University") (part "RES-2"))
    )
    (comp (ref "R7")
      (value "CAY16-103J4LF")
      (footprint "BOUR-CAY16-J4_V")
      (description "Chip Resistor Array, 10 KOhm, +/- 5%, 62.5 mW, -55 to 125 degC, 8-Pin SMD, RoHS, Tape and Reel")
      (fields (field (name "TOLERANCE") "1%"))
      (libsource (lib "Altium Content Vault") (part "RES-P-8"))
    )
    (comp (ref "R8")
      (value "CAY16-103J4LF")
      (footprint "BOUR-CAY16-J4_V")
      (description "Chip Resistor Array, 10 KOhm, +/- 5%, 62.5 mW, -55 to 125 degC, 8-Pin SMD, RoHS, Tape and Reel")
      (fields (field (name "TOLERANCE") "1%"))
      (libsource (lib "Altium Content Vault") (part "RES-P-8"))
    )
    (comp (ref "R9")
      (value "CAY16-103J4LF")
      (footprint "BOUR-CAY16-J4_V")
      (description "Chip Resistor Array, 10 KOhm, +/- 5%, 62.5 mW, -55 to 125 degC, 8-Pin SMD, RoHS, Tape and Reel")
      (fields (field (name "TOLERANCE") "1%"))
      (libsource (lib "Altium Content Vault") (part "RES-P-8"))
    )
    (comp (ref "R10")
      (value "CAY16-103J4LF")
      (footprint "BOUR-CAY16-J4_V")
      (description "Chip Resistor Array, 10 KOhm, +/- 5%, 62.5 mW, -55 to 125 degC, 8-Pin SMD, RoHS, Tape and Reel")
      (fields (field (name "TOLERANCE") "1%"))
      (libsource (lib "Altium Content Vault") (part "RES-P-8"))
    )
    (comp (ref "R11")
      (value "CAY16-103J4LF")
      (footprint "BOUR-CAY16-J4_V")
      (description "Chip Resistor Array, 10 KOhm, +/- 5%, 62.5 mW, -55 to 125 degC, 8-Pin SMD, RoHS, Tape and Reel")
      (fields (field (name "TOLERANCE") "1%"))
      (libsource (lib "Altium Content Vault") (part "RES-P-8"))
    )
    (comp (ref "R12")
      (value "CAY16-103J4LF")
      (footprint "BOUR-CAY16-J4_V")
      (description "Chip Resistor Array, 10 KOhm, +/- 5%, 62.5 mW, -55 to 125 degC, 8-Pin SMD, RoHS, Tape and Reel")
      (fields (field (name "TOLERANCE") "1%"))
      (libsource (lib "Altium Content Vault") (part "RES-P-8"))
    )
    (comp (ref "R13")
      (value "CAY16-103J4LF")
      (footprint "BOUR-CAY16-J4_V")
      (description "Chip Resistor Array, 10 KOhm, +/- 5%, 62.5 mW, -55 to 125 degC, 8-Pin SMD, RoHS, Tape and Reel")
      (fields (field (name "TOLERANCE") "1%"))
      (libsource (lib "Altium Content Vault") (part "RES-P-8"))
    )
    (comp (ref "R14")
      (value "CAY16-103J4LF")
      (footprint "BOUR-CAY16-J4_V")
      (description "Chip Resistor Array, 10 KOhm, +/- 5%, 62.5 mW, -55 to 125 degC, 8-Pin SMD, RoHS, Tape and Reel")
      (fields (field (name "TOLERANCE") "1%"))
      (libsource (lib "Altium Content Vault") (part "RES-P-8"))
    )
    (comp (ref "R15")
      (value "CAY16-103J4LF")
      (footprint "BOUR-CAY16-J4_V")
      (description "Chip Resistor Array, 10 KOhm, +/- 5%, 62.5 mW, -55 to 125 degC, 8-Pin SMD, RoHS, Tape and Reel")
      (fields (field (name "TOLERANCE") "1%"))
      (libsource (lib "Altium Content Vault") (part "RES-P-8"))
    )
    (comp (ref "R16")
      (value "CAY16-103J4LF")
      (footprint "BOUR-CAY16-J4_V")
      (description "Chip Resistor Array, 10 KOhm, +/- 5%, 62.5 mW, -55 to 125 degC, 8-Pin SMD, RoHS, Tape and Reel")
      (fields (field (name "TOLERANCE") "1%"))
      (libsource (lib "Altium Content Vault") (part "RES-P-8"))
    )
    (comp (ref "R17")
      (value "CAY16-103J4LF")
      (footprint "BOUR-CAY16-J4_V")
      (description "Chip Resistor Array, 10 KOhm, +/- 5%, 62.5 mW, -55 to 125 degC, 8-Pin SMD, RoHS, Tape and Reel")
      (fields (field (name "TOLERANCE") "1%"))
      (libsource (lib "Altium Content Vault") (part "RES-P-8"))
    )
    (comp (ref "R18")
      (value "CAY16-103J4LF")
      (footprint "BOUR-CAY16-J4_V")
      (description "Chip Resistor Array, 10 KOhm, +/- 5%, 62.5 mW, -55 to 125 degC, 8-Pin SMD, RoHS, Tape and Reel")
      (fields (field (name "TOLERANCE") "1%"))
      (libsource (lib "Altium Content Vault") (part "RES-P-8"))
    )
    (comp (ref "R19")
      (value "CAY16-103J4LF")
      (footprint "BOUR-CAY16-J4_V")
      (description "Chip Resistor Array, 10 KOhm, +/- 5%, 62.5 mW, -55 to 125 degC, 8-Pin SMD, RoHS, Tape and Reel")
      (fields (field (name "TOLERANCE") "1%"))
      (libsource (lib "Altium Content Vault") (part "RES-P-8"))
    )
    (comp (ref "R20")
      (value "CAY16-103J4LF")
      (footprint "BOUR-CAY16-J4_V")
      (description "Chip Resistor Array, 10 KOhm, +/- 5%, 62.5 mW, -55 to 125 degC, 8-Pin SMD, RoHS, Tape and Reel")
      (fields (field (name "TOLERANCE") "1%"))
      (libsource (lib "Altium Content Vault") (part "RES-P-8"))
    )
    (comp (ref "R21")
      (value "CAY16-103J4LF")
      (footprint "BOUR-CAY16-J4_V")
      (description "Chip Resistor Array, 10 KOhm, +/- 5%, 62.5 mW, -55 to 125 degC, 8-Pin SMD, RoHS, Tape and Reel")
      (fields (field (name "TOLERANCE") "1%"))
      (libsource (lib "Altium Content Vault") (part "RES-P-8"))
    )
    (comp (ref "R22")
      (value "CAY16-103J4LF")
      (footprint "BOUR-CAY16-J4_V")
      (description "Chip Resistor Array, 10 KOhm, +/- 5%, 62.5 mW, -55 to 125 degC, 8-Pin SMD, RoHS, Tape and Reel")
      (fields (field (name "TOLERANCE") "1%"))
      (libsource (lib "Altium Content Vault") (part "RES-P-8"))
    )
    (comp (ref "R23")
      (value "CAY16-103J4LF")
      (footprint "BOUR-CAY16-J4_V")
      (description "Chip Resistor Array, 10 KOhm, +/- 5%, 62.5 mW, -55 to 125 degC, 8-Pin SMD, RoHS, Tape and Reel")
      (fields (field (name "TOLERANCE") "1%"))
      (libsource (lib "Altium Content Vault") (part "RES-P-8"))
    )
    (comp (ref "R24")
      (value "CAY16-103J4LF")
      (footprint "BOUR-CAY16-J4_V")
      (description "Chip Resistor Array, 10 KOhm, +/- 5%, 62.5 mW, -55 to 125 degC, 8-Pin SMD, RoHS, Tape and Reel")
      (fields (field (name "TOLERANCE") "1%"))
      (libsource (lib "Altium Content Vault") (part "RES-P-8"))
    )
    (comp (ref "R25")
      (value "CAY16-103J4LF")
      (footprint "BOUR-CAY16-J4_V")
      (description "Chip Resistor Array, 10 KOhm, +/- 5%, 62.5 mW, -55 to 125 degC, 8-Pin SMD, RoHS, Tape and Reel")
      (fields (field (name "TOLERANCE") "1%"))
      (libsource (lib "Altium Content Vault") (part "RES-P-8"))
    )
    (comp (ref "R26")
      (value "CAY16-103J4LF")
      (footprint "BOUR-CAY16-J4_V")
      (description "Chip Resistor Array, 10 KOhm, +/- 5%, 62.5 mW, -55 to 125 degC, 8-Pin SMD, RoHS, Tape and Reel")
      (fields (field (name "TOLERANCE") "1%"))
      (libsource (lib "Altium Content Vault") (part "RES-P-8"))
    )
    (comp (ref "R27")
      (value "CAY16-103J4LF")
      (footprint "BOUR-CAY16-J4_V")
      (description "Chip Resistor Array, 10 KOhm, +/- 5%, 62.5 mW, -55 to 125 degC, 8-Pin SMD, RoHS, Tape and Reel")
      (fields (field (name "TOLERANCE") "1%"))
      (libsource (lib "Altium Content Vault") (part "RES-P-8"))
    )
    (comp (ref "R28")
      (value "CAY16-103J4LF")
      (footprint "BOUR-CAY16-J4_V")
      (description "Chip Resistor Array, 10 KOhm, +/- 5%, 62.5 mW, -55 to 125 degC, 8-Pin SMD, RoHS, Tape and Reel")
      (fields (field (name "TOLERANCE") "1%"))
      (libsource (lib "Altium Content Vault") (part "RES-P-8"))
    )
    (comp (ref "R29")
      (value "CAY16-103J4LF")
      (footprint "BOUR-CAY16-J4_V")
      (description "Chip Resistor Array, 10 KOhm, +/- 5%, 62.5 mW, -55 to 125 degC, 8-Pin SMD, RoHS, Tape and Reel")
      (fields (field (name "TOLERANCE") "1%"))
      (libsource (lib "Altium Content Vault") (part "RES-P-8"))
    )
    (comp (ref "R30")
      (value "CAY16-103J4LF")
      (footprint "BOUR-CAY16-J4_V")
      (description "Chip Resistor Array, 10 KOhm, +/- 5%, 62.5 mW, -55 to 125 degC, 8-Pin SMD, RoHS, Tape and Reel")
      (fields (field (name "TOLERANCE") "1%"))
      (libsource (lib "Altium Content Vault") (part "RES-P-8"))
    )
    (comp (ref "R31")
      (value "CAY16-103J4LF")
      (footprint "BOUR-CAY16-J4_V")
      (description "Chip Resistor Array, 10 KOhm, +/- 5%, 62.5 mW, -55 to 125 degC, 8-Pin SMD, RoHS, Tape and Reel")
      (fields (field (name "TOLERANCE") "1%"))
      (libsource (lib "Altium Content Vault") (part "RES-P-8"))
    )
    (comp (ref "R32")
      (value "CAY16-103J4LF")
      (footprint "BOUR-CAY16-J4_V")
      (description "Chip Resistor Array, 10 KOhm, +/- 5%, 62.5 mW, -55 to 125 degC, 8-Pin SMD, RoHS, Tape and Reel")
      (fields (field (name "TOLERANCE") "1%"))
      (libsource (lib "Altium Content Vault") (part "RES-P-8"))
    )
    (comp (ref "R33")
      (value "CAY16-103J4LF")
      (footprint "BOUR-CAY16-J4_V")
      (description "Chip Resistor Array, 10 KOhm, +/- 5%, 62.5 mW, -55 to 125 degC, 8-Pin SMD, RoHS, Tape and Reel")
      (fields (field (name "TOLERANCE") "1%"))
      (libsource (lib "Altium Content Vault") (part "RES-P-8"))
    )
    (comp (ref "R34")
      (value "CAY16-103J4LF")
      (footprint "BOUR-CAY16-J4_V")
      (description "Chip Resistor Array, 10 KOhm, +/- 5%, 62.5 mW, -55 to 125 degC, 8-Pin SMD, RoHS, Tape and Reel")
      (fields (field (name "TOLERANCE") "1%"))
      (libsource (lib "Altium Content Vault") (part "RES-P-8"))
    )
    (comp (ref "SW1")
      (value "MX1A-11NW_HS")
      (footprint "MX1A-11NW-Footprint-1")
      (libsource (lib "Pennsylvania State University") (part "KEYSW-SPST-2"))
    )
    (comp (ref "SW2")
      (value "MX1A-11NW_HS")
      (footprint "MX1A-11NW-Footprint-1")
      (libsource (lib "Pennsylvania State University") (part "KEYSW-SPST-2"))
    )
    (comp (ref "SW3")
      (value "MX1A-11NW_HS")
      (footprint "MX1A-11NW-Footprint-1")
      (libsource (lib "Pennsylvania State University") (part "KEYSW-SPST-2"))
    )
    (comp (ref "SW4")
      (value "MX1A-11NW_HS")
      (footprint "MX1A-11NW-Footprint-1")
      (libsource (lib "Pennsylvania State University") (part "KEYSW-SPST-2"))
    )
    (comp (ref "SW5")
      (value "MX1A-11NW_HS")
      (footprint "MX1A-11NW-Footprint-1")
      (libsource (lib "Pennsylvania State University") (part "KEYSW-SPST-2"))
    )
    (comp (ref "SW6")
      (value "MX1A-11NW_HS")
      (footprint "MX1A-11NW-Footprint-1")
      (libsource (lib "Pennsylvania State University") (part "KEYSW-SPST-2"))
    )
    (comp (ref "SW7")
      (value "MX1A-11NW_HS")
      (footprint "MX1A-11NW-Footprint-1")
      (libsource (lib "Pennsylvania State University") (part "KEYSW-SPST-2"))
    )
    (comp (ref "SW8")
      (value "MX1A-11NW_HS")
      (footprint "MX1A-11NW-Footprint-1")
      (libsource (lib "Pennsylvania State University") (part "KEYSW-SPST-2"))
    )
    (comp (ref "SW9")
      (value "MX1A-11NW_HS")
      (footprint "MX1A-11NW-Footprint-1")
      (libsource (lib "Pennsylvania State University") (part "KEYSW-SPST-2"))
    )
    (comp (ref "SW10")
      (value "MX1A-11NW_HS")
      (footprint "MX1A-11NW-Footprint-1")
      (libsource (lib "Pennsylvania State University") (part "KEYSW-SPST-2"))
    )
    (comp (ref "SW11")
      (value "MX1A-11NW_HS")
      (footprint "MX1A-11NW-Footprint-1")
      (libsource (lib "Pennsylvania State University") (part "KEYSW-SPST-2"))
    )
    (comp (ref "SW12")
      (value "MX1A-11NW_HS")
      (footprint "MX1A-11NW-Footprint-1")
      (libsource (lib "Pennsylvania State University") (part "KEYSW-SPST-2"))
    )
    (comp (ref "SW13")
      (value "MX1A-11NW_HS")
      (footprint "MX1A-11NW-Footprint-1")
      (libsource (lib "Pennsylvania State University") (part "KEYSW-SPST-2"))
    )
    (comp (ref "SW14")
      (value "MX1A-11NW_HS")
      (footprint "MX1A-11NW-Footprint-1")
      (libsource (lib "Pennsylvania State University") (part "KEYSW-SPST-2"))
    )
    (comp (ref "SW15")
      (value "MX1A-11NW_HS")
      (footprint "MX1A-11NW-Footprint-1")
      (libsource (lib "Pennsylvania State University") (part "KEYSW-SPST-2"))
    )
    (comp (ref "SW16")
      (value "MX1A-11NW_HS")
      (footprint "MX1A-11NW-Footprint-1")
      (libsource (lib "Pennsylvania State University") (part "KEYSW-SPST-2"))
    )
    (comp (ref "SW17")
      (value "MX1A-11NW_HS")
      (footprint "MX1A-11NW-Footprint-1")
      (libsource (lib "Pennsylvania State University") (part "KEYSW-SPST-2"))
    )
    (comp (ref "SW18")
      (value "MX1A-11NW_HS")
      (footprint "MX1A-11NW-Footprint-1")
      (libsource (lib "Pennsylvania State University") (part "KEYSW-SPST-2"))
    )
    (comp (ref "SW19")
      (value "MX1A-11NW_HS")
      (footprint "MX1A-11NW-Footprint-1")
      (libsource (lib "Pennsylvania State University") (part "KEYSW-SPST-2"))
    )
    (comp (ref "SW20")
      (value "MX1A-11NW_HS")
      (footprint "MX1A-11NW-Footprint-1")
      (libsource (lib "Pennsylvania State University") (part "KEYSW-SPST-2"))
    )
    (comp (ref "SW21")
      (value "MX1A-11NW_HS")
      (footprint "MX1A-11NW-Footprint-1")
      (libsource (lib "Pennsylvania State University") (part "KEYSW-SPST-2"))
    )
    (comp (ref "SW22")
      (value "MX1A-11NW_HS")
      (footprint "MX1A-11NW-Footprint-1")
      (libsource (lib "Pennsylvania State University") (part "KEYSW-SPST-2"))
    )
    (comp (ref "SW23")
      (value "MX1A-11NW_HS")
      (footprint "MX1A-11NW-Footprint-1")
      (libsource (lib "Pennsylvania State University") (part "KEYSW-SPST-2"))
    )
    (comp (ref "SW24")
      (value "MX1A-11NW_HS")
      (footprint "MX1A-11NW-Footprint-1")
      (libsource (lib "Pennsylvania State University") (part "KEYSW-SPST-2"))
    )
    (comp (ref "SW25")
      (value "MX1A-11NW_HS")
      (footprint "MX1A-11NW-Footprint-1")
      (libsource (lib "Pennsylvania State University") (part "KEYSW-SPST-2"))
    )
    (comp (ref "SW26")
      (value "MX1A-11NW_HS")
      (footprint "MX1A-11NW-Footprint-1")
      (libsource (lib "Pennsylvania State University") (part "KEYSW-SPST-2"))
    )
    (comp (ref "SW27")
      (value "MX1A-11NW_HS")
      (footprint "MX1A-11NW-Footprint-1")
      (libsource (lib "Pennsylvania State University") (part "KEYSW-SPST-2"))
    )
    (comp (ref "SW28")
      (value "MX1A-11NW_HS")
      (footprint "MX1A-11NW-Footprint-1")
      (libsource (lib "Pennsylvania State University") (part "KEYSW-SPST-2"))
    )
    (comp (ref "SW29")
      (value "MX1A-11NW_HS")
      (footprint "MX1A-11NW-Footprint-1")
      (libsource (lib "Pennsylvania State University") (part "KEYSW-SPST-2"))
    )
    (comp (ref "SW30")
      (value "MX1A-11NW_HS")
      (footprint "MX1A-11NW-Footprint-1")
      (libsource (lib "Pennsylvania State University") (part "KEYSW-SPST-2"))
    )
    (comp (ref "SW31")
      (value "MX1A-11NW_HS")
      (footprint "MX1A-11NW-Footprint-1")
      (libsource (lib "Pennsylvania State University") (part "KEYSW-SPST-2"))
    )
    (comp (ref "SW32")
      (value "MX1A-11NW_HS")
      (footprint "MX1A-11NW-Footprint-1")
      (libsource (lib "Pennsylvania State University") (part "KEYSW-SPST-2"))
    )
    (comp (ref "SW33")
      (value "MX1A-11NW_HS")
      (footprint "MX1A-11NW-Footprint-1")
      (libsource (lib "Pennsylvania State University") (part "KEYSW-SPST-2"))
    )
    (comp (ref "SW34")
      (value "MX1A-11NW_HS")
      (footprint "MX1A-11NW-Footprint-1")
      (libsource (lib "Pennsylvania State University") (part "KEYSW-SPST-2"))
    )
    (comp (ref "SW35")
      (value "MX1A-11NW_HS")
      (footprint "MX1A-11NW-Footprint-1")
      (libsource (lib "Pennsylvania State University") (part "KEYSW-SPST-2"))
    )
    (comp (ref "SW36")
      (value "MX1A-11NW_HS")
      (footprint "MX1A-11NW-Footprint-1")
      (libsource (lib "Pennsylvania State University") (part "KEYSW-SPST-2"))
    )
    (comp (ref "SW37")
      (value "MX1A-11NW_HS")
      (footprint "MX1A-11NW-Footprint-1")
      (libsource (lib "Pennsylvania State University") (part "KEYSW-SPST-2"))
    )
    (comp (ref "SW38")
      (value "MX1A-11NW_HS")
      (footprint "MX1A-11NW-Footprint-1")
      (libsource (lib "Pennsylvania State University") (part "KEYSW-SPST-2"))
    )
    (comp (ref "SW39")
      (value "MX1A-11NW_HS")
      (footprint "MX1A-11NW-Footprint-1")
      (libsource (lib "Pennsylvania State University") (part "KEYSW-SPST-2"))
    )
    (comp (ref "SW40")
      (value "MX1A-11NW_HS")
      (footprint "MX1A-11NW-Footprint-1")
      (libsource (lib "Pennsylvania State University") (part "KEYSW-SPST-2"))
    )
    (comp (ref "SW41")
      (value "MX1A-11NW_HS")
      (footprint "MX1A-11NW-Footprint-1")
      (libsource (lib "Pennsylvania State University") (part "KEYSW-SPST-2"))
    )
    (comp (ref "SW42")
      (value "MX1A-11NW_HS")
      (footprint "MX1A-11NW-Footprint-1")
      (libsource (lib "Pennsylvania State University") (part "KEYSW-SPST-2"))
    )
    (comp (ref "SW43")
      (value "MX1A-11NW_HS")
      (footprint "MX1A-11NW-Footprint-1")
      (libsource (lib "Pennsylvania State University") (part "KEYSW-SPST-2"))
    )
    (comp (ref "SW44")
      (value "MX1A-11NW_HS")
      (footprint "MX1A-11NW-Footprint-1")
      (libsource (lib "Pennsylvania State University") (part "KEYSW-SPST-2"))
    )
    (comp (ref "SW45")
      (value "MX1A-11NW_HS")
      (footprint "MX1A-11NW-Footprint-1")
      (libsource (lib "Pennsylvania State University") (part "KEYSW-SPST-2"))
    )
    (comp (ref "SW46")
      (value "MX1A-11NW_HS")
      (footprint "MX1A-11NW-Footprint-1")
      (libsource (lib "Pennsylvania State University") (part "KEYSW-SPST-2"))
    )
    (comp (ref "SW47")
      (value "MX1A-11NW_HS")
      (footprint "MX1A-11NW-Footprint-1")
      (libsource (lib "Pennsylvania State University") (part "KEYSW-SPST-2"))
    )
    (comp (ref "SW48")
      (value "MX1A-11NW_HS")
      (footprint "MX1A-11NW-Footprint-1")
      (libsource (lib "Pennsylvania State University") (part "KEYSW-SPST-2"))
    )
    (comp (ref "SW49")
      (value "MX1A-11NW_HS")
      (footprint "MX1A-11NW-Footprint-1")
      (libsource (lib "Pennsylvania State University") (part "KEYSW-SPST-2"))
    )
    (comp (ref "SW50")
      (value "MX1A-11NW_HS")
      (footprint "MX1A-11NW-Footprint-1")
      (libsource (lib "Pennsylvania State University") (part "KEYSW-SPST-2"))
    )
    (comp (ref "SW51")
      (value "MX1A-11NW_HS")
      (footprint "MX1A-11NW-Footprint-1")
      (libsource (lib "Pennsylvania State University") (part "KEYSW-SPST-2"))
    )
    (comp (ref "SW52")
      (value "MX1A-11NW_HS")
      (footprint "MX1A-11NW-Footprint-1")
      (libsource (lib "Pennsylvania State University") (part "KEYSW-SPST-2"))
    )
    (comp (ref "SW53")
      (value "MX1A-11NW_HS")
      (footprint "MX1A-11NW-Footprint-1")
      (libsource (lib "Pennsylvania State University") (part "KEYSW-SPST-2"))
    )
    (comp (ref "SW54")
      (value "MX1A-11NW_HS")
      (footprint "MX1A-11NW-Footprint-1")
      (libsource (lib "Pennsylvania State University") (part "KEYSW-SPST-2"))
    )
    (comp (ref "SW55")
      (value "MX1A-11NW_HS")
      (footprint "MX1A-11NW-Footprint-1")
      (libsource (lib "Pennsylvania State University") (part "KEYSW-SPST-2"))
    )
    (comp (ref "SW56")
      (value "MX1A-11NW_HS")
      (footprint "MX1A-11NW-Footprint-1")
      (libsource (lib "Pennsylvania State University") (part "KEYSW-SPST-2"))
    )
    (comp (ref "SW57")
      (value "MX1A-11NW_HS")
      (footprint "MX1A-11NW-Footprint-1")
      (libsource (lib "Pennsylvania State University") (part "KEYSW-SPST-2"))
    )
    (comp (ref "SW58")
      (value "MX1A-11NW_HS")
      (footprint "MX1A-11NW-Footprint-1")
      (libsource (lib "Pennsylvania State University") (part "KEYSW-SPST-2"))
    )
    (comp (ref "SW59")
      (value "MX1A-11NW_HS")
      (footprint "MX1A-11NW-Footprint-1")
      (libsource (lib "Pennsylvania State University") (part "KEYSW-SPST-2"))
    )
    (comp (ref "SW60")
      (value "MX1A-11NW_HS")
      (footprint "MX1A-11NW-Footprint-1")
      (libsource (lib "Pennsylvania State University") (part "KEYSW-SPST-2"))
    )
    (comp (ref "SW61")
      (value "MX1A-11NW_HS")
      (footprint "MX1A-11NW-Footprint-1")
      (libsource (lib "Pennsylvania State University") (part "KEYSW-SPST-2"))
    )
    (comp (ref "SW62")
      (value "MX1A-11NW_HS")
      (footprint "MX1A-11NW-Footprint-1")
      (libsource (lib "Pennsylvania State University") (part "KEYSW-SPST-2"))
    )
    (comp (ref "SW63")
      (value "MX1A-11NW_HS")
      (footprint "MX1A-11NW-Footprint-1")
      (libsource (lib "Pennsylvania State University") (part "KEYSW-SPST-2"))
    )
    (comp (ref "SW64")
      (value "MX1A-11NW_HS")
      (footprint "MX1A-11NW-Footprint-1")
      (libsource (lib "Pennsylvania State University") (part "KEYSW-SPST-2"))
    )
    (comp (ref "SW65")
      (value "MX1A-11NW_HS")
      (footprint "MX1A-11NW-Footprint-1")
      (libsource (lib "Pennsylvania State University") (part "KEYSW-SPST-2"))
    )
    (comp (ref "SW66")
      (value "MX1A-11NW_HS")
      (footprint "MX1A-11NW-Footprint-1")
      (libsource (lib "Pennsylvania State University") (part "KEYSW-SPST-2"))
    )
    (comp (ref "SW67")
      (value "MX1A-11NW_HS")
      (footprint "MX1A-11NW-Footprint-1")
      (libsource (lib "Pennsylvania State University") (part "KEYSW-SPST-2"))
    )
    (comp (ref "SW68")
      (value "MX1A-11NW_HS")
      (footprint "MX1A-11NW-Footprint-1")
      (libsource (lib "Pennsylvania State University") (part "KEYSW-SPST-2"))
    )
    (comp (ref "SW69")
      (value "MX1A-11NW_HS")
      (footprint "MX1A-11NW-Footprint-1")
      (libsource (lib "Pennsylvania State University") (part "KEYSW-SPST-2"))
    )
    (comp (ref "SW70")
      (value "MX1A-11NW_HS")
      (footprint "MX1A-11NW-Footprint-1")
      (libsource (lib "Pennsylvania State University") (part "KEYSW-SPST-2"))
    )
    (comp (ref "SW71")
      (value "MX1A-11NW_HS")
      (footprint "MX1A-11NW-Footprint-1")
      (libsource (lib "Pennsylvania State University") (part "KEYSW-SPST-2"))
    )
    (comp (ref "SW72")
      (value "MX1A-11NW_HS")
      (footprint "MX1A-11NW-Footprint-1")
      (libsource (lib "Pennsylvania State University") (part "KEYSW-SPST-2"))
    )
    (comp (ref "SW73")
      (value "MX1A-11NW_HS")
      (footprint "MX1A-11NW-Footprint-1")
      (libsource (lib "Pennsylvania State University") (part "KEYSW-SPST-2"))
    )
    (comp (ref "SW74")
      (value "MX1A-11NW_HS")
      (footprint "MX1A-11NW-Footprint-1")
      (libsource (lib "Pennsylvania State University") (part "KEYSW-SPST-2"))
    )
    (comp (ref "SW75")
      (value "MX1A-11NW_HS")
      (footprint "MX1A-11NW-Footprint-1")
      (libsource (lib "Pennsylvania State University") (part "KEYSW-SPST-2"))
    )
    (comp (ref "SW76")
      (value "MX1A-11NW_HS")
      (footprint "MX1A-11NW-Footprint-1")
      (libsource (lib "Pennsylvania State University") (part "KEYSW-SPST-2"))
    )
    (comp (ref "SW77")
      (value "MX1A-11NW_HS")
      (footprint "MX1A-11NW-Footprint-1")
      (libsource (lib "Pennsylvania State University") (part "KEYSW-SPST-2"))
    )
    (comp (ref "SW78")
      (value "MX1A-11NW_HS")
      (footprint "MX1A-11NW-Footprint-1")
      (libsource (lib "Pennsylvania State University") (part "KEYSW-SPST-2"))
    )
    (comp (ref "SW79")
      (value "MX1A-11NW_HS")
      (footprint "MX1A-11NW-Footprint-1")
      (libsource (lib "Pennsylvania State University") (part "KEYSW-SPST-2"))
    )
    (comp (ref "SW80")
      (value "MX1A-11NW_HS")
      (footprint "MX1A-11NW-Footprint-1")
      (libsource (lib "Pennsylvania State University") (part "KEYSW-SPST-2"))
    )
    (comp (ref "SW81")
      (value "MX1A-11NW_HS")
      (footprint "MX1A-11NW-Footprint-1")
      (libsource (lib "Pennsylvania State University") (part "KEYSW-SPST-2"))
    )
    (comp (ref "SW82")
      (value "MX1A-11NW_HS")
      (footprint "MX1A-11NW-Footprint-1")
      (libsource (lib "Pennsylvania State University") (part "KEYSW-SPST-2"))
    )
    (comp (ref "SW83")
      (value "MX1A-11NW_HS")
      (footprint "MX1A-11NW-Footprint-1")
      (libsource (lib "Pennsylvania State University") (part "KEYSW-SPST-2"))
    )
    (comp (ref "SW84")
      (value "MX1A-11NW_HS")
      (footprint "MX1A-11NW-Footprint-1")
      (libsource (lib "Pennsylvania State University") (part "KEYSW-SPST-2"))
    )
    (comp (ref "SW85")
      (value "MX1A-11NW_HS")
      (footprint "MX1A-11NW-Footprint-1")
      (libsource (lib "Pennsylvania State University") (part "KEYSW-SPST-2"))
    )
    (comp (ref "SW86")
      (value "MX1A-11NW_HS")
      (footprint "MX1A-11NW-Footprint-1")
      (libsource (lib "Pennsylvania State University") (part "KEYSW-SPST-2"))
    )
    (comp (ref "SW87")
      (value "MX1A-11NW_HS")
      (footprint "MX1A-11NW-Footprint-1")
      (libsource (lib "Pennsylvania State University") (part "KEYSW-SPST-2"))
    )
    (comp (ref "SW88")
      (value "MX1A-11NW_HS")
      (footprint "MX1A-11NW-Footprint-1")
      (libsource (lib "Pennsylvania State University") (part "KEYSW-SPST-2"))
    )
    (comp (ref "SW89")
      (value "MX1A-11NW_HS")
      (footprint "MX1A-11NW-Footprint-1")
      (libsource (lib "Pennsylvania State University") (part "KEYSW-SPST-2"))
    )
    (comp (ref "SW90")
      (value "MX1A-11NW_HS")
      (footprint "MX1A-11NW-Footprint-1")
      (libsource (lib "Pennsylvania State University") (part "KEYSW-SPST-2"))
    )
    (comp (ref "SW91")
      (value "MX1A-11NW_HS")
      (footprint "MX1A-11NW-Footprint-1")
      (libsource (lib "Pennsylvania State University") (part "KEYSW-SPST-2"))
    )
    (comp (ref "SW92")
      (value "MX1A-11NW_HS")
      (footprint "MX1A-11NW-Footprint-1")
      (libsource (lib "Pennsylvania State University") (part "KEYSW-SPST-2"))
    )
    (comp (ref "SW93")
      (value "MX1A-11NW_HS")
      (footprint "MX1A-11NW-Footprint-1")
      (libsource (lib "Pennsylvania State University") (part "KEYSW-SPST-2"))
    )
    (comp (ref "SW94")
      (value "MX1A-11NW_HS")
      (footprint "MX1A-11NW-Footprint-1")
      (libsource (lib "Pennsylvania State University") (part "KEYSW-SPST-2"))
    )
    (comp (ref "SW95")
      (value "MX1A-11NW_HS")
      (footprint "MX1A-11NW-Footprint-1")
      (libsource (lib "Pennsylvania State University") (part "KEYSW-SPST-2"))
    )
    (comp (ref "SW96")
      (value "MX1A-11NW_HS")
      (footprint "MX1A-11NW-Footprint-1")
      (libsource (lib "Pennsylvania State University") (part "KEYSW-SPST-2"))
    )
    (comp (ref "SW97")
      (value "MX1A-11NW_HS")
      (footprint "MX1A-11NW-Footprint-1")
      (libsource (lib "Pennsylvania State University") (part "KEYSW-SPST-2"))
    )
    (comp (ref "SW98")
      (value "MX1A-11NW_HS")
      (footprint "MX1A-11NW-Footprint-1")
      (libsource (lib "Pennsylvania State University") (part "KEYSW-SPST-2"))
    )
    (comp (ref "SW99")
      (value "MX1A-11NW_HS")
      (footprint "MX1A-11NW-Footprint-1")
      (libsource (lib "Pennsylvania State University") (part "KEYSW-SPST-2"))
    )
    (comp (ref "SW100")
      (value "MX1A-11NW_HS")
      (footprint "MX1A-11NW-Footprint-1")
      (libsource (lib "Pennsylvania State University") (part "KEYSW-SPST-2"))
    )
    (comp (ref "SW101")
      (value "MX1A-11NW_HS")
      (footprint "MX1A-11NW-Footprint-1")
      (libsource (lib "Pennsylvania State University") (part "KEYSW-SPST-2"))
    )
    (comp (ref "SW102")
      (value "MX1A-11NW_HS")
      (footprint "MX1A-11NW-Footprint-1")
      (libsource (lib "Pennsylvania State University") (part "KEYSW-SPST-2"))
    )
    (comp (ref "SW103")
      (value "MX1A-11NW_HS")
      (footprint "MX1A-11NW-Footprint-1")
      (libsource (lib "Pennsylvania State University") (part "KEYSW-SPST-2"))
    )
    (comp (ref "SW104")
      (value "MX1A-11NW_HS")
      (footprint "MX1A-11NW-Footprint-1")
      (libsource (lib "Pennsylvania State University") (part "KEYSW-SPST-2"))
    )
    (comp (ref "SW105")
      (value "MX1A-11NW_HS")
      (footprint "MX1A-11NW-Footprint-1")
      (libsource (lib "Pennsylvania State University") (part "KEYSW-SPST-2"))
    )
    (comp (ref "SW106")
      (value "MX1A-11NW_HS")
      (footprint "MX1A-11NW-Footprint-1")
      (libsource (lib "Pennsylvania State University") (part "KEYSW-SPST-2"))
    )
    (comp (ref "SW107")
      (value "MX1A-11NW_HS")
      (footprint "MX1A-11NW-Footprint-1")
      (libsource (lib "Pennsylvania State University") (part "KEYSW-SPST-2"))
    )
    (comp (ref "SW108")
      (value "MX1A-11NW_HS")
      (footprint "MX1A-11NW-Footprint-1")
      (libsource (lib "Pennsylvania State University") (part "KEYSW-SPST-2"))
    )
    (comp (ref "SW109")
      (value "MX1A-11NW_HS")
      (footprint "MX1A-11NW-Footprint-1")
      (libsource (lib "Pennsylvania State University") (part "KEYSW-SPST-2"))
    )
    (comp (ref "SW110")
      (value "MX1A-11NW_HS")
      (footprint "MX1A-11NW-Footprint-1")
      (libsource (lib "Pennsylvania State University") (part "KEYSW-SPST-2"))
    )
    (comp (ref "SW111")
      (value "MX1A-11NW_HS")
      (footprint "MX1A-11NW-Footprint-1")
      (libsource (lib "Pennsylvania State University") (part "KEYSW-SPST-2"))
    )
    (comp (ref "SW112")
      (value "MX1A-11NW_HS")
      (footprint "MX1A-11NW-Footprint-1")
      (libsource (lib "Pennsylvania State University") (part "KEYSW-SPST-2"))
    )
    (comp (ref "U1")
      (value "LM3940IMP-3.3/NOPB")
      (footprint "FP-DCY0004A-MFG")
      (description "IC REG LINEAR 3.3V 1A SOT223-4")
      (libsource (lib "Altium Content Vault") (part "ef78896361455d16e3252a05c23564e"))
    )
    (comp (ref "U2")
      (value "TCR2EF33,LM(CT")
      (footprint "SOT95P275X140-5N")
      (description "Fixed Positive LDO Regulator, 3.3V, 0.2V Dropout, CMOS, PDSO5")
      (libsource (lib "Pennsylvania State University") (part "TCR2EF33,LM(CT-Symbol-1"))
    )
    (comp (ref "U3")
      (value "RP2040TR13")
      (footprint "QFN40P700X700X90_HS-57N")
      (description "Mcu, 32 Bit, 133MHZ, QFN-56;")
      (libsource (lib "Pennsylvania State University") (part "RP2040TR13"))
    )
    (comp (ref "U4")
      (value "74HC165D,653")
      (footprint "FP-SOT109-1-IPC_B")
      (description "Parallel In Serial Out, HC/UH Series, 8-Bit, Right Direction, Complementary Output, CMOS, PDSO16")
      (libsource (lib "Pennsylvania State University") (part "74HC165D,653-Symbol-1"))
    )
    (comp (ref "U5")
      (value "74HC165D,653")
      (footprint "FP-SOT109-1-IPC_B")
      (description "Parallel In Serial Out, HC/UH Series, 8-Bit, Right Direction, Complementary Output, CMOS, PDSO16")
      (libsource (lib "Pennsylvania State University") (part "74HC165D,653-Symbol-1"))
    )
    (comp (ref "U6")
      (value "74HC165D,653")
      (footprint "FP-SOT109-1-IPC_B")
      (description "Parallel In Serial Out, HC/UH Series, 8-Bit, Right Direction, Complementary Output, CMOS, PDSO16")
      (libsource (lib "Pennsylvania State University") (part "74HC165D,653-Symbol-1"))
    )
    (comp (ref "U7")
      (value "74HC165D,653")
      (footprint "FP-SOT109-1-IPC_B")
      (description "Parallel In Serial Out, HC/UH Series, 8-Bit, Right Direction, Complementary Output, CMOS, PDSO16")
      (libsource (lib "Pennsylvania State University") (part "74HC165D,653-Symbol-1"))
    )
    (comp (ref "U8")
      (value "74HC165D,653")
      (footprint "FP-SOT109-1-IPC_B")
      (description "Parallel In Serial Out, HC/UH Series, 8-Bit, Right Direction, Complementary Output, CMOS, PDSO16")
      (libsource (lib "Pennsylvania State University") (part "74HC165D,653-Symbol-1"))
    )
    (comp (ref "U9")
      (value "74HC165D,653")
      (footprint "FP-SOT109-1-IPC_B")
      (description "Parallel In Serial Out, HC/UH Series, 8-Bit, Right Direction, Complementary Output, CMOS, PDSO16")
      (libsource (lib "Pennsylvania State University") (part "74HC165D,653-Symbol-1"))
    )
    (comp (ref "U10")
      (value "74HC165D,653")
      (footprint "FP-SOT109-1-IPC_B")
      (description "Parallel In Serial Out, HC/UH Series, 8-Bit, Right Direction, Complementary Output, CMOS, PDSO16")
      (libsource (lib "Pennsylvania State University") (part "74HC165D,653-Symbol-1"))
    )
    (comp (ref "U11")
      (value "74HC165D,653")
      (footprint "FP-SOT109-1-IPC_B")
      (description "Parallel In Serial Out, HC/UH Series, 8-Bit, Right Direction, Complementary Output, CMOS, PDSO16")
      (libsource (lib "Pennsylvania State University") (part "74HC165D,653-Symbol-1"))
    )
    (comp (ref "U12")
      (value "74HC165D,653")
      (footprint "FP-SOT109-1-IPC_B")
      (description "Parallel In Serial Out, HC/UH Series, 8-Bit, Right Direction, Complementary Output, CMOS, PDSO16")
      (libsource (lib "Pennsylvania State University") (part "74HC165D,653-Symbol-1"))
    )
    (comp (ref "U13")
      (value "74HC165D,653")
      (footprint "FP-SOT109-1-IPC_B")
      (description "Parallel In Serial Out, HC/UH Series, 8-Bit, Right Direction, Complementary Output, CMOS, PDSO16")
      (libsource (lib "Pennsylvania State University") (part "74HC165D,653-Symbol-1"))
    )
    (comp (ref "U14")
      (value "74HC165D,653")
      (footprint "FP-SOT109-1-IPC_B")
      (description "Parallel In Serial Out, HC/UH Series, 8-Bit, Right Direction, Complementary Output, CMOS, PDSO16")
      (libsource (lib "Pennsylvania State University") (part "74HC165D,653-Symbol-1"))
    )
    (comp (ref "U15")
      (value "74HC165D,653")
      (footprint "FP-SOT109-1-IPC_B")
      (description "Parallel In Serial Out, HC/UH Series, 8-Bit, Right Direction, Complementary Output, CMOS, PDSO16")
      (libsource (lib "Pennsylvania State University") (part "74HC165D,653-Symbol-1"))
    )
    (comp (ref "U16")
      (value "74HC165D,653")
      (footprint "FP-SOT109-1-IPC_B")
      (description "Parallel In Serial Out, HC/UH Series, 8-Bit, Right Direction, Complementary Output, CMOS, PDSO16")
      (libsource (lib "Pennsylvania State University") (part "74HC165D,653-Symbol-1"))
    )
    (comp (ref "U17")
      (value "74HC165D,653")
      (footprint "FP-SOT109-1-IPC_B")
      (description "Parallel In Serial Out, HC/UH Series, 8-Bit, Right Direction, Complementary Output, CMOS, PDSO16")
      (libsource (lib "Pennsylvania State University") (part "74HC165D,653-Symbol-1"))
    )
    (comp (ref "Y1")
      (value "W25Q128JVSIQ TR")
      (footprint "SOIC127P790X216-8N")
      (description "Flash, 16MX8, PDSO8")
      (libsource (lib "Pennsylvania State University") (part "W25Q128JVSIQ TR-Symbol-1"))
    )
    (comp (ref "Y2")
      (value "ABM8G-12.000MHZ-18-D2Y-T")
      (footprint "FP-ABM8G-MFG")
      (description "Crystal 12MHz ±20ppm (Tol) ±30ppm (Stability) 18pF FUND 120Ω 4-Pin SMD T/R")
      (fields (field (name "TOLERANCE") "20ppm"))
      (libsource (lib "Altium Content Vault") (part "48e526d86b7f2615d98721063c72f49"))
    )
  )
  (nets
    (net (code "1") (name "+3V3 VCC") (class "Default")
      (node (ref "C10") (pin "1") (pinfunction "1_1") (pintype "passive"))
      (node (ref "C11") (pin "1") (pinfunction "1_1") (pintype "passive"))
      (node (ref "C12") (pin "1") (pinfunction "1_1") (pintype "passive"))
      (node (ref "C13") (pin "1") (pinfunction "1_1") (pintype "passive"))
      (node (ref "C14") (pin "1") (pinfunction "1_1") (pintype "passive"))
      (node (ref "C17") (pin "1") (pinfunction "1_1") (pintype "passive"))
      (node (ref "C19") (pin "1") (pinfunction "1_1") (pintype "passive"))
      (node (ref "C2") (pin "1") (pinfunction "1_1") (pintype "passive"))
      (node (ref "C20") (pin "1") (pinfunction "1_1") (pintype "passive"))
      (node (ref "C21") (pin "1") (pinfunction "1_1") (pintype "passive"))
      (node (ref "C25") (pin "1") (pinfunction "1_1") (pintype "passive"))
      (node (ref "C26") (pin "1") (pinfunction "1_1") (pintype "passive"))
      (node (ref "C27") (pin "1") (pinfunction "1_1") (pintype "passive"))
      (node (ref "C28") (pin "1") (pinfunction "1_1") (pintype "passive"))
      (node (ref "C29") (pin "1") (pinfunction "1_1") (pintype "passive"))
      (node (ref "C3") (pin "1") (pinfunction "1_1") (pintype "passive"))
      (node (ref "C30") (pin "1") (pinfunction "1_1") (pintype "passive"))
      (node (ref "C31") (pin "1") (pinfunction "1_1") (pintype "passive"))
      (node (ref "C32") (pin "1") (pinfunction "1_1") (pintype "passive"))
      (node (ref "C33") (pin "1") (pinfunction "1_1") (pintype "passive"))
      (node (ref "C34") (pin "1") (pinfunction "1_1") (pintype "passive"))
      (node (ref "C35") (pin "1") (pinfunction "1_1") (pintype "passive"))
      (node (ref "C36") (pin "1") (pinfunction "1_1") (pintype "passive"))
      (node (ref "C37") (pin "1") (pinfunction "1_1") (pintype "passive"))
      (node (ref "C38") (pin "1") (pinfunction "1_1") (pintype "passive"))
      (node (ref "C7") (pin "1") (pinfunction "1_1") (pintype "passive"))
      (node (ref "C8") (pin "1") (pinfunction "1_1") (pintype "passive"))
      (node (ref "C9") (pin "1") (pinfunction "1_1") (pintype "passive"))
      (node (ref "FP1") (pin "2") (pinfunction "2_2") (pintype "passive"))
      (node (ref "P2") (pin "2") (pinfunction "2_2") (pintype "passive"))
      (node (ref "R1") (pin "2") (pinfunction "2_2") (pintype "passive"))
      (node (ref "R10") (pin "1") (pinfunction "1_1") (pintype "passive"))
      (node (ref "R10") (pin "2") (pinfunction "2_2") (pintype "passive"))
      (node (ref "R10") (pin "3") (pinfunction "3_3") (pintype "passive"))
      (node (ref "R10") (pin "4") (pinfunction "4_4") (pintype "passive"))
      (node (ref "R11") (pin "1") (pinfunction "1_1") (pintype "passive"))
      (node (ref "R11") (pin "2") (pinfunction "2_2") (pintype "passive"))
      (node (ref "R11") (pin "3") (pinfunction "3_3") (pintype "passive"))
      (node (ref "R11") (pin "4") (pinfunction "4_4") (pintype "passive"))
      (node (ref "R12") (pin "1") (pinfunction "1_1") (pintype "passive"))
      (node (ref "R12") (pin "2") (pinfunction "2_2") (pintype "passive"))
      (node (ref "R12") (pin "3") (pinfunction "3_3") (pintype "passive"))
      (node (ref "R12") (pin "4") (pinfunction "4_4") (pintype "passive"))
      (node (ref "R13") (pin "1") (pinfunction "1_1") (pintype "passive"))
      (node (ref "R13") (pin "2") (pinfunction "2_2") (pintype "passive"))
      (node (ref "R13") (pin "3") (pinfunction "3_3") (pintype "passive"))
      (node (ref "R13") (pin "4") (pinfunction "4_4") (pintype "passive"))
      (node (ref "R14") (pin "1") (pinfunction "1_1") (pintype "passive"))
      (node (ref "R14") (pin "2") (pinfunction "2_2") (pintype "passive"))
      (node (ref "R14") (pin "3") (pinfunction "3_3") (pintype "passive"))
      (node (ref "R14") (pin "4") (pinfunction "4_4") (pintype "passive"))
      (node (ref "R15") (pin "1") (pinfunction "1_1") (pintype "passive"))
      (node (ref "R15") (pin "2") (pinfunction "2_2") (pintype "passive"))
      (node (ref "R15") (pin "3") (pinfunction "3_3") (pintype "passive"))
      (node (ref "R15") (pin "4") (pinfunction "4_4") (pintype "passive"))
      (node (ref "R16") (pin "1") (pinfunction "1_1") (pintype "passive"))
      (node (ref "R16") (pin "2") (pinfunction "2_2") (pintype "passive"))
      (node (ref "R16") (pin "3") (pinfunction "3_3") (pintype "passive"))
      (node (ref "R16") (pin "4") (pinfunction "4_4") (pintype "passive"))
      (node (ref "R17") (pin "1") (pinfunction "1_1") (pintype "passive"))
      (node (ref "R17") (pin "2") (pinfunction "2_2") (pintype "passive"))
      (node (ref "R17") (pin "3") (pinfunction "3_3") (pintype "passive"))
      (node (ref "R17") (pin "4") (pinfunction "4_4") (pintype "passive"))
      (node (ref "R18") (pin "1") (pinfunction "1_1") (pintype "passive"))
      (node (ref "R18") (pin "2") (pinfunction "2_2") (pintype "passive"))
      (node (ref "R18") (pin "3") (pinfunction "3_3") (pintype "passive"))
      (node (ref "R18") (pin "4") (pinfunction "4_4") (pintype "passive"))
      (node (ref "R19") (pin "1") (pinfunction "1_1") (pintype "passive"))
      (node (ref "R19") (pin "2") (pinfunction "2_2") (pintype "passive"))
      (node (ref "R19") (pin "3") (pinfunction "3_3") (pintype "passive"))
      (node (ref "R19") (pin "4") (pinfunction "4_4") (pintype "passive"))
      (node (ref "R20") (pin "1") (pinfunction "1_1") (pintype "passive"))
      (node (ref "R20") (pin "2") (pinfunction "2_2") (pintype "passive"))
      (node (ref "R20") (pin "3") (pinfunction "3_3") (pintype "passive"))
      (node (ref "R20") (pin "4") (pinfunction "4_4") (pintype "passive"))
      (node (ref "R21") (pin "1") (pinfunction "1_1") (pintype "passive"))
      (node (ref "R21") (pin "2") (pinfunction "2_2") (pintype "passive"))
      (node (ref "R21") (pin "3") (pinfunction "3_3") (pintype "passive"))
      (node (ref "R21") (pin "4") (pinfunction "4_4") (pintype "passive"))
      (node (ref "R22") (pin "1") (pinfunction "1_1") (pintype "passive"))
      (node (ref "R22") (pin "2") (pinfunction "2_2") (pintype "passive"))
      (node (ref "R22") (pin "3") (pinfunction "3_3") (pintype "passive"))
      (node (ref "R22") (pin "4") (pinfunction "4_4") (pintype "passive"))
      (node (ref "R23") (pin "1") (pinfunction "1_1") (pintype "passive"))
      (node (ref "R23") (pin "2") (pinfunction "2_2") (pintype "passive"))
      (node (ref "R23") (pin "3") (pinfunction "3_3") (pintype "passive"))
      (node (ref "R23") (pin "4") (pinfunction "4_4") (pintype "passive"))
      (node (ref "R24") (pin "1") (pinfunction "1_1") (pintype "passive"))
      (node (ref "R24") (pin "2") (pinfunction "2_2") (pintype "passive"))
      (node (ref "R24") (pin "3") (pinfunction "3_3") (pintype "passive"))
      (node (ref "R24") (pin "4") (pinfunction "4_4") (pintype "passive"))
      (node (ref "R25") (pin "1") (pinfunction "1_1") (pintype "passive"))
      (node (ref "R25") (pin "2") (pinfunction "2_2") (pintype "passive"))
      (node (ref "R25") (pin "3") (pinfunction "3_3") (pintype "passive"))
      (node (ref "R25") (pin "4") (pinfunction "4_4") (pintype "passive"))
      (node (ref "R26") (pin "1") (pinfunction "1_1") (pintype "passive"))
      (node (ref "R26") (pin "2") (pinfunction "2_2") (pintype "passive"))
      (node (ref "R26") (pin "3") (pinfunction "3_3") (pintype "passive"))
      (node (ref "R26") (pin "4") (pinfunction "4_4") (pintype "passive"))
      (node (ref "R27") (pin "1") (pinfunction "1_1") (pintype "passive"))
      (node (ref "R27") (pin "2") (pinfunction "2_2") (pintype "passive"))
      (node (ref "R27") (pin "3") (pinfunction "3_3") (pintype "passive"))
      (node (ref "R27") (pin "4") (pinfunction "4_4") (pintype "passive"))
      (node (ref "R28") (pin "1") (pinfunction "1_1") (pintype "passive"))
      (node (ref "R28") (pin "2") (pinfunction "2_2") (pintype "passive"))
      (node (ref "R28") (pin "3") (pinfunction "3_3") (pintype "passive"))
      (node (ref "R28") (pin "4") (pinfunction "4_4") (pintype "passive"))
      (node (ref "R29") (pin "1") (pinfunction "1_1") (pintype "passive"))
      (node (ref "R29") (pin "2") (pinfunction "2_2") (pintype "passive"))
      (node (ref "R29") (pin "3") (pinfunction "3_3") (pintype "passive"))
      (node (ref "R29") (pin "4") (pinfunction "4_4") (pintype "passive"))
      (node (ref "R30") (pin "1") (pinfunction "1_1") (pintype "passive"))
      (node (ref "R30") (pin "2") (pinfunction "2_2") (pintype "passive"))
      (node (ref "R30") (pin "3") (pinfunction "3_3") (pintype "passive"))
      (node (ref "R30") (pin "4") (pinfunction "4_4") (pintype "passive"))
      (node (ref "R31") (pin "1") (pinfunction "1_1") (pintype "passive"))
      (node (ref "R31") (pin "2") (pinfunction "2_2") (pintype "passive"))
      (node (ref "R31") (pin "3") (pinfunction "3_3") (pintype "passive"))
      (node (ref "R31") (pin "4") (pinfunction "4_4") (pintype "passive"))
      (node (ref "R32") (pin "1") (pinfunction "1_1") (pintype "passive"))
      (node (ref "R32") (pin "2") (pinfunction "2_2") (pintype "passive"))
      (node (ref "R32") (pin "3") (pinfunction "3_3") (pintype "passive"))
      (node (ref "R32") (pin "4") (pinfunction "4_4") (pintype "passive"))
      (node (ref "R33") (pin "1") (pinfunction "1_1") (pintype "passive"))
      (node (ref "R33") (pin "2") (pinfunction "2_2") (pintype "passive"))
      (node (ref "R33") (pin "3") (pinfunction "3_3") (pintype "passive"))
      (node (ref "R33") (pin "4") (pinfunction "4_4") (pintype "passive"))
      (node (ref "R34") (pin "1") (pinfunction "1_1") (pintype "passive"))
      (node (ref "R34") (pin "2") (pinfunction "2_2") (pintype "passive"))
      (node (ref "R34") (pin "3") (pinfunction "3_3") (pintype "passive"))
      (node (ref "R34") (pin "4") (pinfunction "4_4") (pintype "passive"))
      (node (ref "R4") (pin "1") (pinfunction "1_1") (pintype "passive"))
      (node (ref "R7") (pin "1") (pinfunction "1_1") (pintype "passive"))
      (node (ref "R7") (pin "2") (pinfunction "2_2") (pintype "passive"))
      (node (ref "R7") (pin "3") (pinfunction "3_3") (pintype "passive"))
      (node (ref "R7") (pin "4") (pinfunction "4_4") (pintype "passive"))
      (node (ref "R8") (pin "1") (pinfunction "1_1") (pintype "passive"))
      (node (ref "R8") (pin "2") (pinfunction "2_2") (pintype "passive"))
      (node (ref "R8") (pin "3") (pinfunction "3_3") (pintype "passive"))
      (node (ref "R8") (pin "4") (pinfunction "4_4") (pintype "passive"))
      (node (ref "R9") (pin "1") (pinfunction "1_1") (pintype "passive"))
      (node (ref "R9") (pin "2") (pinfunction "2_2") (pintype "passive"))
      (node (ref "R9") (pin "3") (pinfunction "3_3") (pintype "passive"))
      (node (ref "R9") (pin "4") (pinfunction "4_4") (pintype "passive"))
      (node (ref "U1") (pin "3") (pinfunction "OUT_3") (pintype "power_in"))
      (node (ref "U10") (pin "16") (pinfunction "VCC_16") (pintype "passive"))
      (node (ref "U11") (pin "16") (pinfunction "VCC_16") (pintype "passive"))
      (node (ref "U12") (pin "16") (pinfunction "VCC_16") (pintype "passive"))
      (node (ref "U13") (pin "16") (pinfunction "VCC_16") (pintype "passive"))
      (node (ref "U14") (pin "16") (pinfunction "VCC_16") (pintype "passive"))
      (node (ref "U15") (pin "16") (pinfunction "VCC_16") (pintype "passive"))
      (node (ref "U16") (pin "16") (pinfunction "VCC_16") (pintype "passive"))
      (node (ref "U17") (pin "16") (pinfunction "VCC_16") (pintype "passive"))
      (node (ref "U2") (pin "1") (pinfunction "VIN_1") (pintype "passive"))
      (node (ref "U3") (pin "1") (pinfunction "IOVDD_1") (pintype "passive"))
      (node (ref "U3") (pin "10") (pinfunction "IOVDD_10") (pintype "passive"))
      (node (ref "U3") (pin "22") (pinfunction "IOVDD_22") (pintype "passive"))
      (node (ref "U3") (pin "33") (pinfunction "IOVDD_33") (pintype "passive"))
      (node (ref "U3") (pin "42") (pinfunction "IOVDD_42") (pintype "passive"))
      (node (ref "U3") (pin "43") (pinfunction "ADC_AVDD_43") (pintype "passive"))
      (node (ref "U3") (pin "44") (pinfunction "VREG_VIN_44") (pintype "passive"))
      (node (ref "U3") (pin "48") (pinfunction "USB_VDD_48") (pintype "passive"))
      (node (ref "U3") (pin "49") (pinfunction "IOVDD_49") (pintype "passive"))
      (node (ref "U4") (pin "16") (pinfunction "VCC_16") (pintype "passive"))
      (node (ref "U5") (pin "16") (pinfunction "VCC_16") (pintype "passive"))
      (node (ref "U6") (pin "16") (pinfunction "VCC_16") (pintype "passive"))
      (node (ref "U7") (pin "16") (pinfunction "VCC_16") (pintype "passive"))
      (node (ref "U8") (pin "16") (pinfunction "VCC_16") (pintype "passive"))
      (node (ref "U9") (pin "16") (pinfunction "VCC_16") (pintype "passive"))
      (node (ref "Y1") (pin "8") (pinfunction "VCC_8") (pintype "passive"))
    )
    (net (code "2") (name "+5V VCC") (class "Default")
      (node (ref "C1") (pin "1") (pinfunction "1_1") (pintype "passive"))
      (node (ref "LED1") (pin "1") (pinfunction "VDD_1") (pintype "power_in"))
      (node (ref "LED10") (pin "1") (pinfunction "VDD_1") (pintype "power_in"))
      (node (ref "LED100") (pin "1") (pinfunction "VDD_1") (pintype "power_in"))
      (node (ref "LED101") (pin "1") (pinfunction "VDD_1") (pintype "power_in"))
      (node (ref "LED102") (pin "1") (pinfunction "VDD_1") (pintype "power_in"))
      (node (ref "LED103") (pin "1") (pinfunction "VDD_1") (pintype "power_in"))
      (node (ref "LED104") (pin "1") (pinfunction "VDD_1") (pintype "power_in"))
      (node (ref "LED105") (pin "1") (pinfunction "VDD_1") (pintype "power_in"))
      (node (ref "LED106") (pin "1") (pinfunction "VDD_1") (pintype "power_in"))
      (node (ref "LED107") (pin "1") (pinfunction "VDD_1") (pintype "power_in"))
      (node (ref "LED108") (pin "1") (pinfunction "VDD_1") (pintype "power_in"))
      (node (ref "LED109") (pin "1") (pinfunction "VDD_1") (pintype "power_in"))
      (node (ref "LED11") (pin "1") (pinfunction "VDD_1") (pintype "power_in"))
      (node (ref "LED110") (pin "1") (pinfunction "VDD_1") (pintype "power_in"))
      (node (ref "LED111") (pin "1") (pinfunction "VDD_1") (pintype "power_in"))
      (node (ref "LED112") (pin "1") (pinfunction "VDD_1") (pintype "power_in"))
      (node (ref "LED12") (pin "1") (pinfunction "VDD_1") (pintype "power_in"))
      (node (ref "LED13") (pin "1") (pinfunction "VDD_1") (pintype "power_in"))
      (node (ref "LED14") (pin "1") (pinfunction "VDD_1") (pintype "power_in"))
      (node (ref "LED15") (pin "1") (pinfunction "VDD_1") (pintype "power_in"))
      (node (ref "LED16") (pin "1") (pinfunction "VDD_1") (pintype "power_in"))
      (node (ref "LED17") (pin "1") (pinfunction "VDD_1") (pintype "power_in"))
      (node (ref "LED18") (pin "1") (pinfunction "VDD_1") (pintype "power_in"))
      (node (ref "LED19") (pin "1") (pinfunction "VDD_1") (pintype "power_in"))
      (node (ref "LED2") (pin "1") (pinfunction "VDD_1") (pintype "power_in"))
      (node (ref "LED20") (pin "1") (pinfunction "VDD_1") (pintype "power_in"))
      (node (ref "LED21") (pin "1") (pinfunction "VDD_1") (pintype "power_in"))
      (node (ref "LED22") (pin "1") (pinfunction "VDD_1") (pintype "power_in"))
      (node (ref "LED23") (pin "1") (pinfunction "VDD_1") (pintype "power_in"))
      (node (ref "LED24") (pin "1") (pinfunction "VDD_1") (pintype "power_in"))
      (node (ref "LED25") (pin "1") (pinfunction "VDD_1") (pintype "power_in"))
      (node (ref "LED26") (pin "1") (pinfunction "VDD_1") (pintype "power_in"))
      (node (ref "LED27") (pin "1") (pinfunction "VDD_1") (pintype "power_in"))
      (node (ref "LED28") (pin "1") (pinfunction "VDD_1") (pintype "power_in"))
      (node (ref "LED29") (pin "1") (pinfunction "VDD_1") (pintype "power_in"))
      (node (ref "LED3") (pin "1") (pinfunction "VDD_1") (pintype "power_in"))
      (node (ref "LED30") (pin "1") (pinfunction "VDD_1") (pintype "power_in"))
      (node (ref "LED31") (pin "1") (pinfunction "VDD_1") (pintype "power_in"))
      (node (ref "LED32") (pin "1") (pinfunction "VDD_1") (pintype "power_in"))
      (node (ref "LED33") (pin "1") (pinfunction "VDD_1") (pintype "power_in"))
      (node (ref "LED34") (pin "1") (pinfunction "VDD_1") (pintype "power_in"))
      (node (ref "LED35") (pin "1") (pinfunction "VDD_1") (pintype "power_in"))
      (node (ref "LED36") (pin "1") (pinfunction "VDD_1") (pintype "power_in"))
      (node (ref "LED37") (pin "1") (pinfunction "VDD_1") (pintype "power_in"))
      (node (ref "LED38") (pin "1") (pinfunction "VDD_1") (pintype "power_in"))
      (node (ref "LED39") (pin "1") (pinfunction "VDD_1") (pintype "power_in"))
      (node (ref "LED4") (pin "1") (pinfunction "VDD_1") (pintype "power_in"))
      (node (ref "LED40") (pin "1") (pinfunction "VDD_1") (pintype "power_in"))
      (node (ref "LED41") (pin "1") (pinfunction "VDD_1") (pintype "power_in"))
      (node (ref "LED42") (pin "1") (pinfunction "VDD_1") (pintype "power_in"))
      (node (ref "LED43") (pin "1") (pinfunction "VDD_1") (pintype "power_in"))
      (node (ref "LED44") (pin "1") (pinfunction "VDD_1") (pintype "power_in"))
      (node (ref "LED45") (pin "1") (pinfunction "VDD_1") (pintype "power_in"))
      (node (ref "LED46") (pin "1") (pinfunction "VDD_1") (pintype "power_in"))
      (node (ref "LED47") (pin "1") (pinfunction "VDD_1") (pintype "power_in"))
      (node (ref "LED48") (pin "1") (pinfunction "VDD_1") (pintype "power_in"))
      (node (ref "LED49") (pin "1") (pinfunction "VDD_1") (pintype "power_in"))
      (node (ref "LED5") (pin "1") (pinfunction "VDD_1") (pintype "power_in"))
      (node (ref "LED50") (pin "1") (pinfunction "VDD_1") (pintype "power_in"))
      (node (ref "LED51") (pin "1") (pinfunction "VDD_1") (pintype "power_in"))
      (node (ref "LED52") (pin "1") (pinfunction "VDD_1") (pintype "power_in"))
      (node (ref "LED53") (pin "1") (pinfunction "VDD_1") (pintype "power_in"))
      (node (ref "LED54") (pin "1") (pinfunction "VDD_1") (pintype "power_in"))
      (node (ref "LED55") (pin "1") (pinfunction "VDD_1") (pintype "power_in"))
      (node (ref "LED56") (pin "1") (pinfunction "VDD_1") (pintype "power_in"))
      (node (ref "LED57") (pin "1") (pinfunction "VDD_1") (pintype "power_in"))
      (node (ref "LED58") (pin "1") (pinfunction "VDD_1") (pintype "power_in"))
      (node (ref "LED59") (pin "1") (pinfunction "VDD_1") (pintype "power_in"))
      (node (ref "LED6") (pin "1") (pinfunction "VDD_1") (pintype "power_in"))
      (node (ref "LED60") (pin "1") (pinfunction "VDD_1") (pintype "power_in"))
      (node (ref "LED61") (pin "1") (pinfunction "VDD_1") (pintype "power_in"))
      (node (ref "LED62") (pin "1") (pinfunction "VDD_1") (pintype "power_in"))
      (node (ref "LED63") (pin "1") (pinfunction "VDD_1") (pintype "power_in"))
      (node (ref "LED64") (pin "1") (pinfunction "VDD_1") (pintype "power_in"))
      (node (ref "LED65") (pin "1") (pinfunction "VDD_1") (pintype "power_in"))
      (node (ref "LED66") (pin "1") (pinfunction "VDD_1") (pintype "power_in"))
      (node (ref "LED67") (pin "1") (pinfunction "VDD_1") (pintype "power_in"))
      (node (ref "LED68") (pin "1") (pinfunction "VDD_1") (pintype "power_in"))
      (node (ref "LED69") (pin "1") (pinfunction "VDD_1") (pintype "power_in"))
      (node (ref "LED7") (pin "1") (pinfunction "VDD_1") (pintype "power_in"))
      (node (ref "LED70") (pin "1") (pinfunction "VDD_1") (pintype "power_in"))
      (node (ref "LED71") (pin "1") (pinfunction "VDD_1") (pintype "power_in"))
      (node (ref "LED72") (pin "1") (pinfunction "VDD_1") (pintype "power_in"))
      (node (ref "LED73") (pin "1") (pinfunction "VDD_1") (pintype "power_in"))
      (node (ref "LED74") (pin "1") (pinfunction "VDD_1") (pintype "power_in"))
      (node (ref "LED75") (pin "1") (pinfunction "VDD_1") (pintype "power_in"))
      (node (ref "LED76") (pin "1") (pinfunction "VDD_1") (pintype "power_in"))
      (node (ref "LED77") (pin "1") (pinfunction "VDD_1") (pintype "power_in"))
      (node (ref "LED78") (pin "1") (pinfunction "VDD_1") (pintype "power_in"))
      (node (ref "LED79") (pin "1") (pinfunction "VDD_1") (pintype "power_in"))
      (node (ref "LED8") (pin "1") (pinfunction "VDD_1") (pintype "power_in"))
      (node (ref "LED80") (pin "1") (pinfunction "VDD_1") (pintype "power_in"))
      (node (ref "LED81") (pin "1") (pinfunction "VDD_1") (pintype "power_in"))
      (node (ref "LED82") (pin "1") (pinfunction "VDD_1") (pintype "power_in"))
      (node (ref "LED83") (pin "1") (pinfunction "VDD_1") (pintype "power_in"))
      (node (ref "LED84") (pin "1") (pinfunction "VDD_1") (pintype "power_in"))
      (node (ref "LED85") (pin "1") (pinfunction "VDD_1") (pintype "power_in"))
      (node (ref "LED86") (pin "1") (pinfunction "VDD_1") (pintype "power_in"))
      (node (ref "LED87") (pin "1") (pinfunction "VDD_1") (pintype "power_in"))
      (node (ref "LED88") (pin "1") (pinfunction "VDD_1") (pintype "power_in"))
      (node (ref "LED89") (pin "1") (pinfunction "VDD_1") (pintype "power_in"))
      (node (ref "LED9") (pin "1") (pinfunction "VDD_1") (pintype "power_in"))
      (node (ref "LED90") (pin "1") (pinfunction "VDD_1") (pintype "power_in"))
      (node (ref "LED91") (pin "1") (pinfunction "VDD_1") (pintype "power_in"))
      (node (ref "LED92") (pin "1") (pinfunction "VDD_1") (pintype "power_in"))
      (node (ref "LED93") (pin "1") (pinfunction "VDD_1") (pintype "power_in"))
      (node (ref "LED94") (pin "1") (pinfunction "VDD_1") (pintype "power_in"))
      (node (ref "LED95") (pin "1") (pinfunction "VDD_1") (pintype "power_in"))
      (node (ref "LED96") (pin "1") (pinfunction "VDD_1") (pintype "power_in"))
      (node (ref "LED97") (pin "1") (pinfunction "VDD_1") (pintype "power_in"))
      (node (ref "LED98") (pin "1") (pinfunction "VDD_1") (pintype "power_in"))
      (node (ref "LED99") (pin "1") (pinfunction "VDD_1") (pintype "power_in"))
      (node (ref "P1") (pin "1") (pinfunction "1_1") (pintype "passive"))
      (node (ref "U1") (pin "1") (pinfunction "INPUT_1") (pintype "power_in"))
    )
    (net (code "3") (name "/1V1") (class "Default")
      (node (ref "C16") (pin "1") (pinfunction "1_1") (pintype "passive"))
      (node (ref "C4") (pin "1") (pinfunction "1_1") (pintype "passive"))
      (node (ref "C5") (pin "1") (pinfunction "1_1") (pintype "passive"))
      (node (ref "C6") (pin "1") (pinfunction "1_1") (pintype "passive"))
      (node (ref "U3") (pin "23") (pinfunction "DVDD_23") (pintype "passive"))
      (node (ref "U3") (pin "45") (pinfunction "VREG_VOUT_45") (pintype "passive"))
      (node (ref "U3") (pin "50") (pinfunction "DVDD_50") (pintype "passive"))
    )
    (net (code "4") (name "/CLKCTRL") (class "Default")
      (node (ref "U10") (pin "2") (pinfunction "CP_2") (pintype "input"))
      (node (ref "U11") (pin "2") (pinfunction "CP_2") (pintype "input"))
      (node (ref "U12") (pin "2") (pinfunction "CP_2") (pintype "input"))
      (node (ref "U13") (pin "2") (pinfunction "CP_2") (pintype "input"))
      (node (ref "U14") (pin "2") (pinfunction "CP_2") (pintype "input"))
      (node (ref "U15") (pin "2") (pinfunction "CP_2") (pintype "input"))
      (node (ref "U16") (pin "2") (pinfunction "CP_2") (pintype "input"))
      (node (ref "U17") (pin "2") (pinfunction "CP_2") (pintype "input"))
      (node (ref "U3") (pin "27") (pinfunction "GPIO16_27") (pintype "passive"))
      (node (ref "U4") (pin "2") (pinfunction "CP_2") (pintype "input"))
      (node (ref "U5") (pin "2") (pinfunction "CP_2") (pintype "input"))
      (node (ref "U6") (pin "2") (pinfunction "CP_2") (pintype "input"))
      (node (ref "U7") (pin "2") (pinfunction "CP_2") (pintype "input"))
      (node (ref "U8") (pin "2") (pinfunction "CP_2") (pintype "input"))
      (node (ref "U9") (pin "2") (pinfunction "CP_2") (pintype "input"))
    )
    (net (code "5") (name "/CLKINH") (class "Default")
      (node (ref "U10") (pin "15") (pinfunction "~{CE}_15") (pintype "input"))
      (node (ref "U11") (pin "15") (pinfunction "~{CE}_15") (pintype "input"))
      (node (ref "U12") (pin "15") (pinfunction "~{CE}_15") (pintype "input"))
      (node (ref "U13") (pin "15") (pinfunction "~{CE}_15") (pintype "input"))
      (node (ref "U14") (pin "15") (pinfunction "~{CE}_15") (pintype "input"))
      (node (ref "U15") (pin "15") (pinfunction "~{CE}_15") (pintype "input"))
      (node (ref "U16") (pin "15") (pinfunction "~{CE}_15") (pintype "input"))
      (node (ref "U17") (pin "15") (pinfunction "~{CE}_15") (pintype "input"))
      (node (ref "U3") (pin "28") (pinfunction "GPIO17_28") (pintype "passive"))
      (node (ref "U4") (pin "15") (pinfunction "~{CE}_15") (pintype "input"))
      (node (ref "U5") (pin "15") (pinfunction "~{CE}_15") (pintype "input"))
      (node (ref "U6") (pin "15") (pinfunction "~{CE}_15") (pintype "input"))
      (node (ref "U7") (pin "15") (pinfunction "~{CE}_15") (pintype "input"))
      (node (ref "U8") (pin "15") (pinfunction "~{CE}_15") (pintype "input"))
      (node (ref "U9") (pin "15") (pinfunction "~{CE}_15") (pintype "input"))
    )
    (net (code "6") (name "/CapsLED") (class "Default")
      (node (ref "LED69") (pin "4") (pinfunction "DIN_4") (pintype "input"))
      (node (ref "U3") (pin "15") (pinfunction "GPIO12_15") (pintype "passive"))
    )
    (net (code "7") (name "/ENCCLK") (class "Default")
      (node (ref "C15") (pin "2") (pinfunction "2_2") (pintype "passive"))
      (node (ref "R2") (pin "1") (pinfunction "1_1") (pintype "passive"))
      (node (ref "U3") (pin "12") (pinfunction "GPIO9_12") (pintype "passive"))
    )
    (net (code "8") (name "/ENCDT") (class "Default")
      (node (ref "C18") (pin "1") (pinfunction "1_1") (pintype "passive"))
      (node (ref "R3") (pin "1") (pinfunction "1_1") (pintype "passive"))
      (node (ref "U3") (pin "13") (pinfunction "GPIO10_13") (pintype "passive"))
    )
    (net (code "9") (name "/ENCSW") (class "Default")
      (node (ref "ENC1") (pin "1") (pinfunction "1_1") (pintype "passive"))
      (node (ref "U3") (pin "11") (pinfunction "GPIO8_11") (pintype "passive"))
    )
    (net (code "10") (name "/FP_CTRL") (class "Default")
      (node (ref "U2") (pin "3") (pinfunction "CTRL_3") (pintype "passive"))
      (node (ref "U3") (pin "37") (pinfunction "GPIO25_37") (pintype "passive"))
    )
    (net (code "11") (name "/FP_TOUCH_OUT") (class "Default")
      (node (ref "FP1") (pin "1") (pinfunction "1_1") (pintype "passive"))
      (node (ref "U3") (pin "41") (pinfunction "GPIO29_41") (pintype "passive"))
    )
    (net (code "12") (name "/FP_UART_RX") (class "Default")
      (node (ref "FP1") (pin "5") (pinfunction "5_5") (pintype "passive"))
      (node (ref "U3") (pin "40") (pinfunction "GPIO28_40") (pintype "passive"))
    )
    (net (code "13") (name "/FP_UART_TX") (class "Default")
      (node (ref "FP1") (pin "4") (pinfunction "4_4") (pintype "passive"))
      (node (ref "U3") (pin "39") (pinfunction "GPIO27_39") (pintype "passive"))
    )
    (net (code "14") (name "/FP_VDD") (class "Default")
      (node (ref "C23") (pin "1") (pinfunction "1_1") (pintype "passive"))
      (node (ref "FP1") (pin "3") (pinfunction "3_3") (pintype "passive"))
      (node (ref "U2") (pin "5") (pinfunction "VOUT_5") (pintype "passive"))
    )
    (net (code "15") (name "/I2C0_SCL_Display") (class "Default")
      (node (ref "P2") (pin "3") (pinfunction "3_3") (pintype "passive"))
      (node (ref "U3") (pin "35") (pinfunction "GPIO23_35") (pintype "passive"))
    )
    (net (code "16") (name "/I2C0_SDA_Display") (class "Default")
      (node (ref "P2") (pin "4") (pinfunction "4_4") (pintype "passive"))
      (node (ref "U3") (pin "34") (pinfunction "GPIO22_34") (pintype "passive"))
    )
    (net (code "17") (name "/KBLIGHTING_IN") (class "Default")
      (node (ref "LED1") (pin "4") (pinfunction "DIN_4") (pintype "input"))
      (node (ref "U3") (pin "14") (pinfunction "GPIO11_14") (pintype "passive"))
    )
    (net (code "18") (name "/KBLIGHT_ROW1END") (class "Default")
      (node (ref "LED28") (pin "2") (pinfunction "DOUT_2") (pintype "output"))
      (node (ref "LED29") (pin "4") (pinfunction "DIN_4") (pintype "input"))
    )
    (net (code "19") (name "/KBLIGHT_ROW2END") (class "Default")
      (node (ref "LED56") (pin "2") (pinfunction "DOUT_2") (pintype "output"))
      (node (ref "LED57") (pin "4") (pinfunction "DIN_4") (pintype "input"))
    )
    (net (code "20") (name "/KBLIGHT_ROW3END") (class "Default")
      (node (ref "LED84") (pin "2") (pinfunction "DOUT_2") (pintype "output"))
      (node (ref "LED85") (pin "4") (pinfunction "DIN_4") (pintype "input"))
    )
    (net (code "21") (name "/MATRIX QH") (class "Default")
      (node (ref "U3") (pin "30") (pinfunction "GPIO19_30") (pintype "passive"))
      (node (ref "U4") (pin "9") (pinfunction "Q7_9") (pintype "output"))
    )
    (net (code "22") (name "/MATRIX SH{slash}LD") (class "Default")
      (node (ref "U10") (pin "1") (pinfunction "~{PL}_1") (pintype "input"))
      (node (ref "U11") (pin "1") (pinfunction "~{PL}_1") (pintype "input"))
      (node (ref "U12") (pin "1") (pinfunction "~{PL}_1") (pintype "input"))
      (node (ref "U13") (pin "1") (pinfunction "~{PL}_1") (pintype "input"))
      (node (ref "U14") (pin "1") (pinfunction "~{PL}_1") (pintype "input"))
      (node (ref "U15") (pin "1") (pinfunction "~{PL}_1") (pintype "input"))
      (node (ref "U16") (pin "1") (pinfunction "~{PL}_1") (pintype "input"))
      (node (ref "U17") (pin "1") (pinfunction "~{PL}_1") (pintype "input"))
      (node (ref "U3") (pin "29") (pinfunction "GPIO18_29") (pintype "passive"))
      (node (ref "U4") (pin "1") (pinfunction "~{PL}_1") (pintype "input"))
      (node (ref "U5") (pin "1") (pinfunction "~{PL}_1") (pintype "input"))
      (node (ref "U6") (pin "1") (pinfunction "~{PL}_1") (pintype "input"))
      (node (ref "U7") (pin "1") (pinfunction "~{PL}_1") (pintype "input"))
      (node (ref "U8") (pin "1") (pinfunction "~{PL}_1") (pintype "input"))
      (node (ref "U9") (pin "1") (pinfunction "~{PL}_1") (pintype "input"))
    )
    (net (code "23") (name "/MCU_USB_D_N") (class "Default")
      (node (ref "R6") (pin "2") (pinfunction "2_2") (pintype "passive"))
      (node (ref "U3") (pin "46") (pinfunction "USB_DM_46") (pintype "passive"))
    )
    (net (code "24") (name "/MCU_USB_D_P") (class "Default")
      (node (ref "R5") (pin "2") (pinfunction "2_2") (pintype "passive"))
      (node (ref "U3") (pin "47") (pinfunction "USB_DP_47") (pintype "passive"))
    )
    (net (code "25") (name "/MCU_USB_D_R_N") (class "Default")
      (node (ref "P1") (pin "2") (pinfunction "2_2") (pintype "passive"))
      (node (ref "R6") (pin "1") (pinfunction "1_1") (pintype "passive"))
    )
    (net (code "26") (name "/MCU_USB_D_R_P") (class "Default")
      (node (ref "P1") (pin "3") (pinfunction "3_3") (pintype "passive"))
      (node (ref "R5") (pin "1") (pinfunction "1_1") (pintype "passive"))
    )
    (net (code "27") (name "/QSPI_SCLK") (class "Default")
      (node (ref "U3") (pin "52") (pinfunction "QSPI_SCLK_52") (pintype "passive"))
      (node (ref "Y1") (pin "6") (pinfunction "CLK_6") (pintype "input"))
    )
    (net (code "28") (name "/QSPI_SD0") (class "Default")
      (node (ref "U3") (pin "53") (pinfunction "QSPI_SD0_53") (pintype "passive"))
      (node (ref "Y1") (pin "5") (pinfunction "DI_(IO0)_5") (pintype "bidirectional"))
    )
    (net (code "29") (name "/QSPI_SD1") (class "Default")
      (node (ref "U3") (pin "55") (pinfunction "QSPI_SD1_55") (pintype "passive"))
      (node (ref "Y1") (pin "2") (pinfunction "DO_(IO1)_2") (pintype "bidirectional"))
    )
    (net (code "30") (name "/QSPI_SD2") (class "Default")
      (node (ref "U3") (pin "54") (pinfunction "QSPI_SD2_54") (pintype "passive"))
      (node (ref "Y1") (pin "3") (pinfunction "/WP_(IO2)_3") (pintype "bidirectional"))
    )
    (net (code "31") (name "/QSPI_SD3") (class "Default")
      (node (ref "U3") (pin "51") (pinfunction "QSPI_SD3_51") (pintype "passive"))
      (node (ref "Y1") (pin "7") (pinfunction "/RESET_(IO3)_7") (pintype "input"))
    )
    (net (code "32") (name "/QSPI_SS_N") (class "Default")
      (node (ref "U3") (pin "56") (pinfunction "QSPI_SS_N_56") (pintype "passive"))
      (node (ref "Y1") (pin "1") (pinfunction "/CS_1") (pintype "input"))
    )
    (net (code "33") (name "/SERNEXT") (class "Default")
      (node (ref "U13") (pin "10") (pinfunction "DS_10") (pintype "input"))
      (node (ref "U14") (pin "9") (pinfunction "Q7_9") (pintype "output"))
    )
    (net (code "34") (name "/XIN RP2040") (class "Default")
      (node (ref "C24") (pin "2") (pinfunction "2_2") (pintype "passive"))
      (node (ref "U3") (pin "20") (pinfunction "XIN_20") (pintype "passive"))
      (node (ref "Y2") (pin "1") (pinfunction "1_1") (pintype "passive"))
    )
    (net (code "35") (name "/XOUT RP2040") (class "Default")
      (node (ref "C22") (pin "2") (pinfunction "2_2") (pintype "passive"))
      (node (ref "U3") (pin "21") (pinfunction "XOUT_21") (pintype "passive"))
      (node (ref "Y2") (pin "3") (pinfunction "3_3") (pintype "passive"))
    )
    (net (code "36") (name "GND") (class "Default")
      (node (ref "C1") (pin "2") (pinfunction "2_2") (pintype "passive"))
      (node (ref "C10") (pin "2") (pinfunction "2_2") (pintype "passive"))
      (node (ref "C11") (pin "2") (pinfunction "2_2") (pintype "passive"))
      (node (ref "C12") (pin "2") (pinfunction "2_2") (pintype "passive"))
      (node (ref "C13") (pin "2") (pinfunction "2_2") (pintype "passive"))
      (node (ref "C14") (pin "2") (pinfunction "2_2") (pintype "passive"))
      (node (ref "C15") (pin "1") (pinfunction "1_1") (pintype "passive"))
      (node (ref "C16") (pin "2") (pinfunction "2_2") (pintype "passive"))
      (node (ref "C17") (pin "2") (pinfunction "2_2") (pintype "passive"))
      (node (ref "C18") (pin "2") (pinfunction "2_2") (pintype "passive"))
      (node (ref "C19") (pin "2") (pinfunction "2_2") (pintype "passive"))
      (node (ref "C2") (pin "2") (pinfunction "2_2") (pintype "passive"))
      (node (ref "C20") (pin "2") (pinfunction "2_2") (pintype "passive"))
      (node (ref "C21") (pin "2") (pinfunction "2_2") (pintype "passive"))
      (node (ref "C22") (pin "1") (pinfunction "1_1") (pintype "passive"))
      (node (ref "C23") (pin "2") (pinfunction "2_2") (pintype "passive"))
      (node (ref "C24") (pin "1") (pinfunction "1_1") (pintype "passive"))
      (node (ref "C25") (pin "2") (pinfunction "2_2") (pintype "passive"))
      (node (ref "C26") (pin "2") (pinfunction "2_2") (pintype "passive"))
      (node (ref "C27") (pin "2") (pinfunction "2_2") (pintype "passive"))
      (node (ref "C28") (pin "2") (pinfunction "2_2") (pintype "passive"))
      (node (ref "C29") (pin "2") (pinfunction "2_2") (pintype "passive"))
      (node (ref "C3") (pin "2") (pinfunction "2_2") (pintype "passive"))
      (node (ref "C30") (pin "2") (pinfunction "2_2") (pintype "passive"))
      (node (ref "C31") (pin "2") (pinfunction "2_2") (pintype "passive"))
      (node (ref "C32") (pin "2") (pinfunction "2_2") (pintype "passive"))
      (node (ref "C33") (pin "2") (pinfunction "2_2") (pintype "passive"))
      (node (ref "C34") (pin "2") (pinfunction "2_2") (pintype "passive"))
      (node (ref "C35") (pin "2") (pinfunction "2_2") (pintype "passive"))
      (node (ref "C36") (pin "2") (pinfunction "2_2") (pintype "passive"))
      (node (ref "C37") (pin "2") (pinfunction "2_2") (pintype "passive"))
      (node (ref "C38") (pin "2") (pinfunction "2_2") (pintype "passive"))
      (node (ref "C4") (pin "2") (pinfunction "2_2") (pintype "passive"))
      (node (ref "C5") (pin "2") (pinfunction "2_2") (pintype "passive"))
      (node (ref "C6") (pin "2") (pinfunction "2_2") (pintype "passive"))
      (node (ref "C7") (pin "2") (pinfunction "2_2") (pintype "passive"))
      (node (ref "C8") (pin "2") (pinfunction "2_2") (pintype "passive"))
      (node (ref "C9") (pin "2") (pinfunction "2_2") (pintype "passive"))
      (node (ref "ENC1") (pin "2") (pinfunction "2_2") (pintype "passive"))
      (node (ref "ENC1") (pin "3") (pinfunction "MNT_1_3") (pintype "passive"))
      (node (ref "ENC1") (pin "4") (pinfunction "MNT_2_4") (pintype "passive"))
      (node (ref "ENC1") (pin "C") (pinfunction "COMMON_C") (pintype "passive"))
      (node (ref "FP1") (pin "10") (pinfunction "10_10") (pintype "passive"))
      (node (ref "FP1") (pin "8") (pinfunction "8_8") (pintype "passive"))
      (node (ref "FP1") (pin "9") (pinfunction "9_9") (pintype "passive"))
      (node (ref "LED1") (pin "3") (pinfunction "VSS_3") (pintype "power_in"))
      (node (ref "LED10") (pin "3") (pinfunction "VSS_3") (pintype "power_in"))
      (node (ref "LED100") (pin "3") (pinfunction "VSS_3") (pintype "power_in"))
      (node (ref "LED101") (pin "3") (pinfunction "VSS_3") (pintype "power_in"))
      (node (ref "LED102") (pin "3") (pinfunction "VSS_3") (pintype "power_in"))
      (node (ref "LED103") (pin "3") (pinfunction "VSS_3") (pintype "power_in"))
      (node (ref "LED104") (pin "3") (pinfunction "VSS_3") (pintype "power_in"))
      (node (ref "LED105") (pin "3") (pinfunction "VSS_3") (pintype "power_in"))
      (node (ref "LED106") (pin "3") (pinfunction "VSS_3") (pintype "power_in"))
      (node (ref "LED107") (pin "3") (pinfunction "VSS_3") (pintype "power_in"))
      (node (ref "LED108") (pin "3") (pinfunction "VSS_3") (pintype "power_in"))
      (node (ref "LED109") (pin "3") (pinfunction "VSS_3") (pintype "power_in"))
      (node (ref "LED11") (pin "3") (pinfunction "VSS_3") (pintype "power_in"))
      (node (ref "LED110") (pin "3") (pinfunction "VSS_3") (pintype "power_in"))
      (node (ref "LED111") (pin "3") (pinfunction "VSS_3") (pintype "power_in"))
      (node (ref "LED112") (pin "3") (pinfunction "VSS_3") (pintype "power_in"))
      (node (ref "LED12") (pin "3") (pinfunction "VSS_3") (pintype "power_in"))
      (node (ref "LED13") (pin "3") (pinfunction "VSS_3") (pintype "power_in"))
      (node (ref "LED14") (pin "3") (pinfunction "VSS_3") (pintype "power_in"))
      (node (ref "LED15") (pin "3") (pinfunction "VSS_3") (pintype "power_in"))
      (node (ref "LED16") (pin "3") (pinfunction "VSS_3") (pintype "power_in"))
      (node (ref "LED17") (pin "3") (pinfunction "VSS_3") (pintype "power_in"))
      (node (ref "LED18") (pin "3") (pinfunction "VSS_3") (pintype "power_in"))
      (node (ref "LED19") (pin "3") (pinfunction "VSS_3") (pintype "power_in"))
      (node (ref "LED2") (pin "3") (pinfunction "VSS_3") (pintype "power_in"))
      (node (ref "LED20") (pin "3") (pinfunction "VSS_3") (pintype "power_in"))
      (node (ref "LED21") (pin "3") (pinfunction "VSS_3") (pintype "power_in"))
      (node (ref "LED22") (pin "3") (pinfunction "VSS_3") (pintype "power_in"))
      (node (ref "LED23") (pin "3") (pinfunction "VSS_3") (pintype "power_in"))
      (node (ref "LED24") (pin "3") (pinfunction "VSS_3") (pintype "power_in"))
      (node (ref "LED25") (pin "3") (pinfunction "VSS_3") (pintype "power_in"))
      (node (ref "LED26") (pin "3") (pinfunction "VSS_3") (pintype "power_in"))
      (node (ref "LED27") (pin "3") (pinfunction "VSS_3") (pintype "power_in"))
      (node (ref "LED28") (pin "3") (pinfunction "VSS_3") (pintype "power_in"))
      (node (ref "LED29") (pin "3") (pinfunction "VSS_3") (pintype "power_in"))
      (node (ref "LED3") (pin "3") (pinfunction "VSS_3") (pintype "power_in"))
      (node (ref "LED30") (pin "3") (pinfunction "VSS_3") (pintype "power_in"))
      (node (ref "LED31") (pin "3") (pinfunction "VSS_3") (pintype "power_in"))
      (node (ref "LED32") (pin "3") (pinfunction "VSS_3") (pintype "power_in"))
      (node (ref "LED33") (pin "3") (pinfunction "VSS_3") (pintype "power_in"))
      (node (ref "LED34") (pin "3") (pinfunction "VSS_3") (pintype "power_in"))
      (node (ref "LED35") (pin "3") (pinfunction "VSS_3") (pintype "power_in"))
      (node (ref "LED36") (pin "3") (pinfunction "VSS_3") (pintype "power_in"))
      (node (ref "LED37") (pin "3") (pinfunction "VSS_3") (pintype "power_in"))
      (node (ref "LED38") (pin "3") (pinfunction "VSS_3") (pintype "power_in"))
      (node (ref "LED39") (pin "3") (pinfunction "VSS_3") (pintype "power_in"))
      (node (ref "LED4") (pin "3") (pinfunction "VSS_3") (pintype "power_in"))
      (node (ref "LED40") (pin "3") (pinfunction "VSS_3") (pintype "power_in"))
      (node (ref "LED41") (pin "3") (pinfunction "VSS_3") (pintype "power_in"))
      (node (ref "LED42") (pin "3") (pinfunction "VSS_3") (pintype "power_in"))
      (node (ref "LED43") (pin "3") (pinfunction "VSS_3") (pintype "power_in"))
      (node (ref "LED44") (pin "3") (pinfunction "VSS_3") (pintype "power_in"))
      (node (ref "LED45") (pin "3") (pinfunction "VSS_3") (pintype "power_in"))
      (node (ref "LED46") (pin "3") (pinfunction "VSS_3") (pintype "power_in"))
      (node (ref "LED47") (pin "3") (pinfunction "VSS_3") (pintype "power_in"))
      (node (ref "LED48") (pin "3") (pinfunction "VSS_3") (pintype "power_in"))
      (node (ref "LED49") (pin "3") (pinfunction "VSS_3") (pintype "power_in"))
      (node (ref "LED5") (pin "3") (pinfunction "VSS_3") (pintype "power_in"))
      (node (ref "LED50") (pin "3") (pinfunction "VSS_3") (pintype "power_in"))
      (node (ref "LED51") (pin "3") (pinfunction "VSS_3") (pintype "power_in"))
      (node (ref "LED52") (pin "3") (pinfunction "VSS_3") (pintype "power_in"))
      (node (ref "LED53") (pin "3") (pinfunction "VSS_3") (pintype "power_in"))
      (node (ref "LED54") (pin "3") (pinfunction "VSS_3") (pintype "power_in"))
      (node (ref "LED55") (pin "3") (pinfunction "VSS_3") (pintype "power_in"))
      (node (ref "LED56") (pin "3") (pinfunction "VSS_3") (pintype "power_in"))
      (node (ref "LED57") (pin "3") (pinfunction "VSS_3") (pintype "power_in"))
      (node (ref "LED58") (pin "3") (pinfunction "VSS_3") (pintype "power_in"))
      (node (ref "LED59") (pin "3") (pinfunction "VSS_3") (pintype "power_in"))
      (node (ref "LED6") (pin "3") (pinfunction "VSS_3") (pintype "power_in"))
      (node (ref "LED60") (pin "3") (pinfunction "VSS_3") (pintype "power_in"))
      (node (ref "LED61") (pin "3") (pinfunction "VSS_3") (pintype "power_in"))
      (node (ref "LED62") (pin "3") (pinfunction "VSS_3") (pintype "power_in"))
      (node (ref "LED63") (pin "3") (pinfunction "VSS_3") (pintype "power_in"))
      (node (ref "LED64") (pin "3") (pinfunction "VSS_3") (pintype "power_in"))
      (node (ref "LED65") (pin "3") (pinfunction "VSS_3") (pintype "power_in"))
      (node (ref "LED66") (pin "3") (pinfunction "VSS_3") (pintype "power_in"))
      (node (ref "LED67") (pin "3") (pinfunction "VSS_3") (pintype "power_in"))
      (node (ref "LED68") (pin "3") (pinfunction "VSS_3") (pintype "power_in"))
      (node (ref "LED69") (pin "3") (pinfunction "VSS_3") (pintype "power_in"))
      (node (ref "LED7") (pin "3") (pinfunction "VSS_3") (pintype "power_in"))
      (node (ref "LED70") (pin "3") (pinfunction "VSS_3") (pintype "power_in"))
      (node (ref "LED71") (pin "3") (pinfunction "VSS_3") (pintype "power_in"))
      (node (ref "LED72") (pin "3") (pinfunction "VSS_3") (pintype "power_in"))
      (node (ref "LED73") (pin "3") (pinfunction "VSS_3") (pintype "power_in"))
      (node (ref "LED74") (pin "3") (pinfunction "VSS_3") (pintype "power_in"))
      (node (ref "LED75") (pin "3") (pinfunction "VSS_3") (pintype "power_in"))
      (node (ref "LED76") (pin "3") (pinfunction "VSS_3") (pintype "power_in"))
      (node (ref "LED77") (pin "3") (pinfunction "VSS_3") (pintype "power_in"))
      (node (ref "LED78") (pin "3") (pinfunction "VSS_3") (pintype "power_in"))
      (node (ref "LED79") (pin "3") (pinfunction "VSS_3") (pintype "power_in"))
      (node (ref "LED8") (pin "3") (pinfunction "VSS_3") (pintype "power_in"))
      (node (ref "LED80") (pin "3") (pinfunction "VSS_3") (pintype "power_in"))
      (node (ref "LED81") (pin "3") (pinfunction "VSS_3") (pintype "power_in"))
      (node (ref "LED82") (pin "3") (pinfunction "VSS_3") (pintype "power_in"))
      (node (ref "LED83") (pin "3") (pinfunction "VSS_3") (pintype "power_in"))
      (node (ref "LED84") (pin "3") (pinfunction "VSS_3") (pintype "power_in"))
      (node (ref "LED85") (pin "3") (pinfunction "VSS_3") (pintype "power_in"))
      (node (ref "LED86") (pin "3") (pinfunction "VSS_3") (pintype "power_in"))
      (node (ref "LED87") (pin "3") (pinfunction "VSS_3") (pintype "power_in"))
      (node (ref "LED88") (pin "3") (pinfunction "VSS_3") (pintype "power_in"))
      (node (ref "LED89") (pin "3") (pinfunction "VSS_3") (pintype "power_in"))
      (node (ref "LED9") (pin "3") (pinfunction "VSS_3") (pintype "power_in"))
      (node (ref "LED90") (pin "3") (pinfunction "VSS_3") (pintype "power_in"))
      (node (ref "LED91") (pin "3") (pinfunction "VSS_3") (pintype "power_in"))
      (node (ref "LED92") (pin "3") (pinfunction "VSS_3") (pintype "power_in"))
      (node (ref "LED93") (pin "3") (pinfunction "VSS_3") (pintype "power_in"))
      (node (ref "LED94") (pin "3") (pinfunction "VSS_3") (pintype "power_in"))
      (node (ref "LED95") (pin "3") (pinfunction "VSS_3") (pintype "power_in"))
      (node (ref "LED96") (pin "3") (pinfunction "VSS_3") (pintype "power_in"))
      (node (ref "LED97") (pin "3") (pinfunction "VSS_3") (pintype "power_in"))
      (node (ref "LED98") (pin "3") (pinfunction "VSS_3") (pintype "power_in"))
      (node (ref "LED99") (pin "3") (pinfunction "VSS_3") (pintype "power_in"))
      (node (ref "P1") (pin "4") (pinfunction "4_4") (pintype "passive"))
      (node (ref "P2") (pin "1") (pinfunction "1_1") (pintype "passive"))
      (node (ref "SW1") (pin "2") (pinfunction "2_2") (pintype "passive"))
      (node (ref "SW10") (pin "2") (pinfunction "2_2") (pintype "passive"))
      (node (ref "SW100") (pin "2") (pinfunction "2_2") (pintype "passive"))
      (node (ref "SW101") (pin "2") (pinfunction "2_2") (pintype "passive"))
      (node (ref "SW102") (pin "2") (pinfunction "2_2") (pintype "passive"))
      (node (ref "SW103") (pin "2") (pinfunction "2_2") (pintype "passive"))
      (node (ref "SW104") (pin "2") (pinfunction "2_2") (pintype "passive"))
      (node (ref "SW105") (pin "2") (pinfunction "2_2") (pintype "passive"))
      (node (ref "SW106") (pin "2") (pinfunction "2_2") (pintype "passive"))
      (node (ref "SW107") (pin "2") (pinfunction "2_2") (pintype "passive"))
      (node (ref "SW108") (pin "2") (pinfunction "2_2") (pintype "passive"))
      (node (ref "SW109") (pin "2") (pinfunction "2_2") (pintype "passive"))
      (node (ref "SW11") (pin "2") (pinfunction "2_2") (pintype "passive"))
      (node (ref "SW110") (pin "2") (pinfunction "2_2") (pintype "passive"))
      (node (ref "SW111") (pin "2") (pinfunction "2_2") (pintype "passive"))
      (node (ref "SW112") (pin "2") (pinfunction "2_2") (pintype "passive"))
      (node (ref "SW12") (pin "2") (pinfunction "2_2") (pintype "passive"))
      (node (ref "SW13") (pin "2") (pinfunction "2_2") (pintype "passive"))
      (node (ref "SW14") (pin "2") (pinfunction "2_2") (pintype "passive"))
      (node (ref "SW15") (pin "2") (pinfunction "2_2") (pintype "passive"))
      (node (ref "SW16") (pin "2") (pinfunction "2_2") (pintype "passive"))
      (node (ref "SW17") (pin "2") (pinfunction "2_2") (pintype "passive"))
      (node (ref "SW18") (pin "2") (pinfunction "2_2") (pintype "passive"))
      (node (ref "SW19") (pin "2") (pinfunction "2_2") (pintype "passive"))
      (node (ref "SW2") (pin "2") (pinfunction "2_2") (pintype "passive"))
      (node (ref "SW20") (pin "2") (pinfunction "2_2") (pintype "passive"))
      (node (ref "SW21") (pin "2") (pinfunction "2_2") (pintype "passive"))
      (node (ref "SW22") (pin "2") (pinfunction "2_2") (pintype "passive"))
      (node (ref "SW23") (pin "2") (pinfunction "2_2") (pintype "passive"))
      (node (ref "SW24") (pin "2") (pinfunction "2_2") (pintype "passive"))
      (node (ref "SW25") (pin "2") (pinfunction "2_2") (pintype "passive"))
      (node (ref "SW26") (pin "2") (pinfunction "2_2") (pintype "passive"))
      (node (ref "SW27") (pin "2") (pinfunction "2_2") (pintype "passive"))
      (node (ref "SW28") (pin "2") (pinfunction "2_2") (pintype "passive"))
      (node (ref "SW29") (pin "2") (pinfunction "2_2") (pintype "passive"))
      (node (ref "SW3") (pin "2") (pinfunction "2_2") (pintype "passive"))
      (node (ref "SW30") (pin "2") (pinfunction "2_2") (pintype "passive"))
      (node (ref "SW31") (pin "2") (pinfunction "2_2") (pintype "passive"))
      (node (ref "SW32") (pin "2") (pinfunction "2_2") (pintype "passive"))
      (node (ref "SW33") (pin "2") (pinfunction "2_2") (pintype "passive"))
      (node (ref "SW34") (pin "2") (pinfunction "2_2") (pintype "passive"))
      (node (ref "SW35") (pin "2") (pinfunction "2_2") (pintype "passive"))
      (node (ref "SW36") (pin "2") (pinfunction "2_2") (pintype "passive"))
      (node (ref "SW37") (pin "2") (pinfunction "2_2") (pintype "passive"))
      (node (ref "SW38") (pin "2") (pinfunction "2_2") (pintype "passive"))
      (node (ref "SW39") (pin "2") (pinfunction "2_2") (pintype "passive"))
      (node (ref "SW4") (pin "2") (pinfunction "2_2") (pintype "passive"))
      (node (ref "SW40") (pin "2") (pinfunction "2_2") (pintype "passive"))
      (node (ref "SW41") (pin "2") (pinfunction "2_2") (pintype "passive"))
      (node (ref "SW42") (pin "2") (pinfunction "2_2") (pintype "passive"))
      (node (ref "SW43") (pin "2") (pinfunction "2_2") (pintype "passive"))
      (node (ref "SW44") (pin "2") (pinfunction "2_2") (pintype "passive"))
      (node (ref "SW45") (pin "2") (pinfunction "2_2") (pintype "passive"))
      (node (ref "SW46") (pin "2") (pinfunction "2_2") (pintype "passive"))
      (node (ref "SW47") (pin "2") (pinfunction "2_2") (pintype "passive"))
      (node (ref "SW48") (pin "2") (pinfunction "2_2") (pintype "passive"))
      (node (ref "SW49") (pin "2") (pinfunction "2_2") (pintype "passive"))
      (node (ref "SW5") (pin "2") (pinfunction "2_2") (pintype "passive"))
      (node (ref "SW50") (pin "2") (pinfunction "2_2") (pintype "passive"))
      (node (ref "SW51") (pin "2") (pinfunction "2_2") (pintype "passive"))
      (node (ref "SW52") (pin "2") (pinfunction "2_2") (pintype "passive"))
      (node (ref "SW53") (pin "2") (pinfunction "2_2") (pintype "passive"))
      (node (ref "SW54") (pin "2") (pinfunction "2_2") (pintype "passive"))
      (node (ref "SW55") (pin "2") (pinfunction "2_2") (pintype "passive"))
      (node (ref "SW56") (pin "2") (pinfunction "2_2") (pintype "passive"))
      (node (ref "SW57") (pin "2") (pinfunction "2_2") (pintype "passive"))
      (node (ref "SW58") (pin "2") (pinfunction "2_2") (pintype "passive"))
      (node (ref "SW59") (pin "2") (pinfunction "2_2") (pintype "passive"))
      (node (ref "SW6") (pin "2") (pinfunction "2_2") (pintype "passive"))
      (node (ref "SW60") (pin "2") (pinfunction "2_2") (pintype "passive"))
      (node (ref "SW61") (pin "2") (pinfunction "2_2") (pintype "passive"))
      (node (ref "SW62") (pin "2") (pinfunction "2_2") (pintype "passive"))
      (node (ref "SW63") (pin "2") (pinfunction "2_2") (pintype "passive"))
      (node (ref "SW64") (pin "2") (pinfunction "2_2") (pintype "passive"))
      (node (ref "SW65") (pin "2") (pinfunction "2_2") (pintype "passive"))
      (node (ref "SW66") (pin "2") (pinfunction "2_2") (pintype "passive"))
      (node (ref "SW67") (pin "2") (pinfunction "2_2") (pintype "passive"))
      (node (ref "SW68") (pin "2") (pinfunction "2_2") (pintype "passive"))
      (node (ref "SW69") (pin "2") (pinfunction "2_2") (pintype "passive"))
      (node (ref "SW7") (pin "2") (pinfunction "2_2") (pintype "passive"))
      (node (ref "SW70") (pin "2") (pinfunction "2_2") (pintype "passive"))
      (node (ref "SW71") (pin "2") (pinfunction "2_2") (pintype "passive"))
      (node (ref "SW72") (pin "2") (pinfunction "2_2") (pintype "passive"))
      (node (ref "SW73") (pin "2") (pinfunction "2_2") (pintype "passive"))
      (node (ref "SW74") (pin "2") (pinfunction "2_2") (pintype "passive"))
      (node (ref "SW75") (pin "2") (pinfunction "2_2") (pintype "passive"))
      (node (ref "SW76") (pin "2") (pinfunction "2_2") (pintype "passive"))
      (node (ref "SW77") (pin "2") (pinfunction "2_2") (pintype "passive"))
      (node (ref "SW78") (pin "2") (pinfunction "2_2") (pintype "passive"))
      (node (ref "SW79") (pin "2") (pinfunction "2_2") (pintype "passive"))
      (node (ref "SW8") (pin "2") (pinfunction "2_2") (pintype "passive"))
      (node (ref "SW80") (pin "2") (pinfunction "2_2") (pintype "passive"))
      (node (ref "SW81") (pin "2") (pinfunction "2_2") (pintype "passive"))
      (node (ref "SW82") (pin "2") (pinfunction "2_2") (pintype "passive"))
      (node (ref "SW83") (pin "2") (pinfunction "2_2") (pintype "passive"))
      (node (ref "SW84") (pin "2") (pinfunction "2_2") (pintype "passive"))
      (node (ref "SW85") (pin "2") (pinfunction "2_2") (pintype "passive"))
      (node (ref "SW86") (pin "2") (pinfunction "2_2") (pintype "passive"))
      (node (ref "SW87") (pin "2") (pinfunction "2_2") (pintype "passive"))
      (node (ref "SW88") (pin "2") (pinfunction "2_2") (pintype "passive"))
      (node (ref "SW89") (pin "2") (pinfunction "2_2") (pintype "passive"))
      (node (ref "SW9") (pin "2") (pinfunction "2_2") (pintype "passive"))
      (node (ref "SW90") (pin "2") (pinfunction "2_2") (pintype "passive"))
      (node (ref "SW91") (pin "2") (pinfunction "2_2") (pintype "passive"))
      (node (ref "SW92") (pin "2") (pinfunction "2_2") (pintype "passive"))
      (node (ref "SW93") (pin "2") (pinfunction "2_2") (pintype "passive"))
      (node (ref "SW94") (pin "2") (pinfunction "2_2") (pintype "passive"))
      (node (ref "SW95") (pin "2") (pinfunction "2_2") (pintype "passive"))
      (node (ref "SW96") (pin "2") (pinfunction "2_2") (pintype "passive"))
      (node (ref "SW97") (pin "2") (pinfunction "2_2") (pintype "passive"))
      (node (ref "SW98") (pin "2") (pinfunction "2_2") (pintype "passive"))
      (node (ref "SW99") (pin "2") (pinfunction "2_2") (pintype "passive"))
      (node (ref "U1") (pin "2") (pinfunction "GND_2") (pintype "power_in"))
      (node (ref "U1") (pin "4") (pinfunction "GND_4") (pintype "power_in"))
      (node (ref "U10") (pin "8") (pinfunction "GND_8") (pintype "passive"))
      (node (ref "U11") (pin "8") (pinfunction "GND_8") (pintype "passive"))
      (node (ref "U12") (pin "8") (pinfunction "GND_8") (pintype "passive"))
      (node (ref "U13") (pin "8") (pinfunction "GND_8") (pintype "passive"))
      (node (ref "U14") (pin "8") (pinfunction "GND_8") (pintype "passive"))
      (node (ref "U15") (pin "8") (pinfunction "GND_8") (pintype "passive"))
      (node (ref "U16") (pin "8") (pinfunction "GND_8") (pintype "passive"))
      (node (ref "U17") (pin "8") (pinfunction "GND_8") (pintype "passive"))
      (node (ref "U2") (pin "2") (pinfunction "GND_2") (pintype "passive"))
      (node (ref "U3") (pin "19") (pinfunction "TESTEN_19") (pintype "passive"))
      (node (ref "U3") (pin "57") (pinfunction "GND_57") (pintype "passive"))
      (node (ref "U4") (pin "8") (pinfunction "GND_8") (pintype "passive"))
      (node (ref "U5") (pin "8") (pinfunction "GND_8") (pintype "passive"))
      (node (ref "U6") (pin "8") (pinfunction "GND_8") (pintype "passive"))
      (node (ref "U7") (pin "8") (pinfunction "GND_8") (pintype "passive"))
      (node (ref "U8") (pin "8") (pinfunction "GND_8") (pintype "passive"))
      (node (ref "U9") (pin "8") (pinfunction "GND_8") (pintype "passive"))
      (node (ref "Y1") (pin "4") (pinfunction "GND_4") (pintype "passive"))
      (node (ref "Y2") (pin "2") (pinfunction "GND_2") (pintype "power_in"))
      (node (ref "Y2") (pin "4") (pinfunction "GND_4") (pintype "power_in"))
    )
    (net (code "37") (name "Net-(ENC1-CHANNEL_A)") (class "Default")
      (node (ref "ENC1") (pin "A") (pinfunction "CHANNEL_A_A") (pintype "passive"))
      (node (ref "R1") (pin "1") (pinfunction "1_1") (pintype "passive"))
      (node (ref "R2") (pin "2") (pinfunction "2_2") (pintype "passive"))
    )
    (net (code "38") (name "Net-(ENC1-CHANNEL_B)") (class "Default")
      (node (ref "ENC1") (pin "B") (pinfunction "CHANNEL_B_B") (pintype "passive"))
      (node (ref "R3") (pin "2") (pinfunction "2_2") (pintype "passive"))
      (node (ref "R4") (pin "2") (pinfunction "2_2") (pintype "passive"))
    )
    (net (code "39") (name "Net-(LED1-DOUT)") (class "Default")
      (node (ref "LED1") (pin "2") (pinfunction "DOUT_2") (pintype "output"))
      (node (ref "LED2") (pin "4") (pinfunction "DIN_4") (pintype "input"))
    )
    (net (code "40") (name "Net-(LED2-DOUT)") (class "Default")
      (node (ref "LED2") (pin "2") (pinfunction "DOUT_2") (pintype "output"))
      (node (ref "LED3") (pin "4") (pinfunction "DIN_4") (pintype "input"))
    )
    (net (code "41") (name "Net-(LED3-DOUT)") (class "Default")
      (node (ref "LED3") (pin "2") (pinfunction "DOUT_2") (pintype "output"))
      (node (ref "LED4") (pin "4") (pinfunction "DIN_4") (pintype "input"))
    )
    (net (code "42") (name "Net-(LED4-DOUT)") (class "Default")
      (node (ref "LED4") (pin "2") (pinfunction "DOUT_2") (pintype "output"))
      (node (ref "LED5") (pin "4") (pinfunction "DIN_4") (pintype "input"))
    )
    (net (code "43") (name "Net-(LED5-DOUT)") (class "Default")
      (node (ref "LED5") (pin "2") (pinfunction "DOUT_2") (pintype "output"))
      (node (ref "LED6") (pin "4") (pinfunction "DIN_4") (pintype "input"))
    )
    (net (code "44") (name "Net-(LED6-DOUT)") (class "Default")
      (node (ref "LED6") (pin "2") (pinfunction "DOUT_2") (pintype "output"))
      (node (ref "LED7") (pin "4") (pinfunction "DIN_4") (pintype "input"))
    )
    (net (code "45") (name "Net-(LED7-DOUT)") (class "Default")
      (node (ref "LED7") (pin "2") (pinfunction "DOUT_2") (pintype "output"))
      (node (ref "LED8") (pin "4") (pinfunction "DIN_4") (pintype "input"))
    )
    (net (code "46") (name "Net-(LED8-DOUT)") (class "Default")
      (node (ref "LED8") (pin "2") (pinfunction "DOUT_2") (pintype "output"))
      (node (ref "LED9") (pin "4") (pinfunction "DIN_4") (pintype "input"))
    )
    (net (code "47") (name "Net-(LED10-DIN)") (class "Default")
      (node (ref "LED10") (pin "4") (pinfunction "DIN_4") (pintype "input"))
      (node (ref "LED9") (pin "2") (pinfunction "DOUT_2") (pintype "output"))
    )
    (net (code "48") (name "Net-(LED10-DOUT)") (class "Default")
      (node (ref "LED10") (pin "2") (pinfunction "DOUT_2") (pintype "output"))
      (node (ref "LED11") (pin "4") (pinfunction "DIN_4") (pintype "input"))
    )
    (net (code "49") (name "Net-(LED11-DOUT)") (class "Default")
      (node (ref "LED11") (pin "2") (pinfunction "DOUT_2") (pintype "output"))
      (node (ref "LED12") (pin "4") (pinfunction "DIN_4") (pintype "input"))
    )
    (net (code "50") (name "Net-(LED12-DOUT)") (class "Default")
      (node (ref "LED12") (pin "2") (pinfunction "DOUT_2") (pintype "output"))
      (node (ref "LED13") (pin "4") (pinfunction "DIN_4") (pintype "input"))
    )
    (net (code "51") (name "Net-(LED13-DOUT)") (class "Default")
      (node (ref "LED13") (pin "2") (pinfunction "DOUT_2") (pintype "output"))
      (node (ref "LED14") (pin "4") (pinfunction "DIN_4") (pintype "input"))
    )
    (net (code "52") (name "Net-(LED14-DOUT)") (class "Default")
      (node (ref "LED14") (pin "2") (pinfunction "DOUT_2") (pintype "output"))
      (node (ref "LED15") (pin "4") (pinfunction "DIN_4") (pintype "input"))
    )
    (net (code "53") (name "Net-(LED15-DOUT)") (class "Default")
      (node (ref "LED15") (pin "2") (pinfunction "DOUT_2") (pintype "output"))
      (node (ref "LED16") (pin "4") (pinfunction "DIN_4") (pintype "input"))
    )
    (net (code "54") (name "Net-(LED16-DOUT)") (class "Default")
      (node (ref "LED16") (pin "2") (pinfunction "DOUT_2") (pintype "output"))
      (node (ref "LED17") (pin "4") (pinfunction "DIN_4") (pintype "input"))
    )
    (net (code "55") (name "Net-(LED17-DOUT)") (class "Default")
      (node (ref "LED17") (pin "2") (pinfunction "DOUT_2") (pintype "output"))
      (node (ref "LED18") (pin "4") (pinfunction "DIN_4") (pintype "input"))
    )
    (net (code "56") (name "Net-(LED18-DOUT)") (class "Default")
      (node (ref "LED18") (pin "2") (pinfunction "DOUT_2") (pintype "output"))
      (node (ref "LED19") (pin "4") (pinfunction "DIN_4") (pintype "input"))
    )
    (net (code "57") (name "Net-(LED19-DOUT)") (class "Default")
      (node (ref "LED19") (pin "2") (pinfunction "DOUT_2") (pintype "output"))
      (node (ref "LED20") (pin "4") (pinfunction "DIN_4") (pintype "input"))
    )
    (net (code "58") (name "Net-(LED20-DOUT)") (class "Default")
      (node (ref "LED20") (pin "2") (pinfunction "DOUT_2") (pintype "output"))
      (node (ref "LED21") (pin "4") (pinfunction "DIN_4") (pintype "input"))
    )
    (net (code "59") (name "Net-(LED21-DOUT)") (class "Default")
      (node (ref "LED21") (pin "2") (pinfunction "DOUT_2") (pintype "output"))
      (node (ref "LED22") (pin "4") (pinfunction "DIN_4") (pintype "input"))
    )
    (net (code "60") (name "Net-(LED22-DOUT)") (class "Default")
      (node (ref "LED22") (pin "2") (pinfunction "DOUT_2") (pintype "output"))
      (node (ref "LED23") (pin "4") (pinfunction "DIN_4") (pintype "input"))
    )
    (net (code "61") (name "Net-(LED23-DOUT)") (class "Default")
      (node (ref "LED23") (pin "2") (pinfunction "DOUT_2") (pintype "output"))
      (node (ref "LED24") (pin "4") (pinfunction "DIN_4") (pintype "input"))
    )
    (net (code "62") (name "Net-(LED24-DOUT)") (class "Default")
      (node (ref "LED24") (pin "2") (pinfunction "DOUT_2") (pintype "output"))
      (node (ref "LED25") (pin "4") (pinfunction "DIN_4") (pintype "input"))
    )
    (net (code "63") (name "Net-(LED25-DOUT)") (class "Default")
      (node (ref "LED25") (pin "2") (pinfunction "DOUT_2") (pintype "output"))
      (node (ref "LED26") (pin "4") (pinfunction "DIN_4") (pintype "input"))
    )
    (net (code "64") (name "Net-(LED26-DOUT)") (class "Default")
      (node (ref "LED26") (pin "2") (pinfunction "DOUT_2") (pintype "output"))
      (node (ref "LED27") (pin "4") (pinfunction "DIN_4") (pintype "input"))
    )
    (net (code "65") (name "Net-(LED27-DOUT)") (class "Default")
      (node (ref "LED27") (pin "2") (pinfunction "DOUT_2") (pintype "output"))
      (node (ref "LED28") (pin "4") (pinfunction "DIN_4") (pintype "input"))
    )
    (net (code "66") (name "Net-(LED29-DOUT)") (class "Default")
      (node (ref "LED29") (pin "2") (pinfunction "DOUT_2") (pintype "output"))
      (node (ref "LED30") (pin "4") (pinfunction "DIN_4") (pintype "input"))
    )
    (net (code "67") (name "Net-(LED30-DOUT)") (class "Default")
      (node (ref "LED30") (pin "2") (pinfunction "DOUT_2") (pintype "output"))
      (node (ref "LED31") (pin "4") (pinfunction "DIN_4") (pintype "input"))
    )
    (net (code "68") (name "Net-(LED31-DOUT)") (class "Default")
      (node (ref "LED31") (pin "2") (pinfunction "DOUT_2") (pintype "output"))
      (node (ref "LED32") (pin "4") (pinfunction "DIN_4") (pintype "input"))
    )
    (net (code "69") (name "Net-(LED32-DOUT)") (class "Default")
      (node (ref "LED32") (pin "2") (pinfunction "DOUT_2") (pintype "output"))
      (node (ref "LED33") (pin "4") (pinfunction "DIN_4") (pintype "input"))
    )
    (net (code "70") (name "Net-(LED33-DOUT)") (class "Default")
      (node (ref "LED33") (pin "2") (pinfunction "DOUT_2") (pintype "output"))
      (node (ref "LED34") (pin "4") (pinfunction "DIN_4") (pintype "input"))
    )
    (net (code "71") (name "Net-(LED34-DOUT)") (class "Default")
      (node (ref "LED34") (pin "2") (pinfunction "DOUT_2") (pintype "output"))
      (node (ref "LED35") (pin "4") (pinfunction "DIN_4") (pintype "input"))
    )
    (net (code "72") (name "Net-(LED35-DOUT)") (class "Default")
      (node (ref "LED35") (pin "2") (pinfunction "DOUT_2") (pintype "output"))
      (node (ref "LED36") (pin "4") (pinfunction "DIN_4") (pintype "input"))
    )
    (net (code "73") (name "Net-(LED36-DOUT)") (class "Default")
      (node (ref "LED36") (pin "2") (pinfunction "DOUT_2") (pintype "output"))
      (node (ref "LED37") (pin "4") (pinfunction "DIN_4") (pintype "input"))
    )
    (net (code "74") (name "Net-(LED37-DOUT)") (class "Default")
      (node (ref "LED37") (pin "2") (pinfunction "DOUT_2") (pintype "output"))
      (node (ref "LED38") (pin "4") (pinfunction "DIN_4") (pintype "input"))
    )
    (net (code "75") (name "Net-(LED38-DOUT)") (class "Default")
      (node (ref "LED38") (pin "2") (pinfunction "DOUT_2") (pintype "output"))
      (node (ref "LED39") (pin "4") (pinfunction "DIN_4") (pintype "input"))
    )
    (net (code "76") (name "Net-(LED39-DOUT)") (class "Default")
      (node (ref "LED39") (pin "2") (pinfunction "DOUT_2") (pintype "output"))
      (node (ref "LED40") (pin "4") (pinfunction "DIN_4") (pintype "input"))
    )
    (net (code "77") (name "Net-(LED40-DOUT)") (class "Default")
      (node (ref "LED40") (pin "2") (pinfunction "DOUT_2") (pintype "output"))
      (node (ref "LED41") (pin "4") (pinfunction "DIN_4") (pintype "input"))
    )
    (net (code "78") (name "Net-(LED41-DOUT)") (class "Default")
      (node (ref "LED41") (pin "2") (pinfunction "DOUT_2") (pintype "output"))
      (node (ref "LED42") (pin "4") (pinfunction "DIN_4") (pintype "input"))
    )
    (net (code "79") (name "Net-(LED42-DOUT)") (class "Default")
      (node (ref "LED42") (pin "2") (pinfunction "DOUT_2") (pintype "output"))
      (node (ref "LED43") (pin "4") (pinfunction "DIN_4") (pintype "input"))
    )
    (net (code "80") (name "Net-(LED43-DOUT)") (class "Default")
      (node (ref "LED43") (pin "2") (pinfunction "DOUT_2") (pintype "output"))
      (node (ref "LED44") (pin "4") (pinfunction "DIN_4") (pintype "input"))
    )
    (net (code "81") (name "Net-(LED44-DOUT)") (class "Default")
      (node (ref "LED44") (pin "2") (pinfunction "DOUT_2") (pintype "output"))
      (node (ref "LED45") (pin "4") (pinfunction "DIN_4") (pintype "input"))
    )
    (net (code "82") (name "Net-(LED45-DOUT)") (class "Default")
      (node (ref "LED45") (pin "2") (pinfunction "DOUT_2") (pintype "output"))
      (node (ref "LED46") (pin "4") (pinfunction "DIN_4") (pintype "input"))
    )
    (net (code "83") (name "Net-(LED46-DOUT)") (class "Default")
      (node (ref "LED46") (pin "2") (pinfunction "DOUT_2") (pintype "output"))
      (node (ref "LED47") (pin "4") (pinfunction "DIN_4") (pintype "input"))
    )
    (net (code "84") (name "Net-(LED47-DOUT)") (class "Default")
      (node (ref "LED47") (pin "2") (pinfunction "DOUT_2") (pintype "output"))
      (node (ref "LED48") (pin "4") (pinfunction "DIN_4") (pintype "input"))
    )
    (net (code "85") (name "Net-(LED48-DOUT)") (class "Default")
      (node (ref "LED48") (pin "2") (pinfunction "DOUT_2") (pintype "output"))
      (node (ref "LED49") (pin "4") (pinfunction "DIN_4") (pintype "input"))
    )
    (net (code "86") (name "Net-(LED49-DOUT)") (class "Default")
      (node (ref "LED49") (pin "2") (pinfunction "DOUT_2") (pintype "output"))
      (node (ref "LED50") (pin "4") (pinfunction "DIN_4") (pintype "input"))
    )
    (net (code "87") (name "Net-(LED50-DOUT)") (class "Default")
      (node (ref "LED50") (pin "2") (pinfunction "DOUT_2") (pintype "output"))
      (node (ref "LED51") (pin "4") (pinfunction "DIN_4") (pintype "input"))
    )
    (net (code "88") (name "Net-(LED51-DOUT)") (class "Default")
      (node (ref "LED51") (pin "2") (pinfunction "DOUT_2") (pintype "output"))
      (node (ref "LED52") (pin "4") (pinfunction "DIN_4") (pintype "input"))
    )
    (net (code "89") (name "Net-(LED52-DOUT)") (class "Default")
      (node (ref "LED52") (pin "2") (pinfunction "DOUT_2") (pintype "output"))
      (node (ref "LED53") (pin "4") (pinfunction "DIN_4") (pintype "input"))
    )
    (net (code "90") (name "Net-(LED53-DOUT)") (class "Default")
      (node (ref "LED53") (pin "2") (pinfunction "DOUT_2") (pintype "output"))
      (node (ref "LED54") (pin "4") (pinfunction "DIN_4") (pintype "input"))
    )
    (net (code "91") (name "Net-(LED54-DOUT)") (class "Default")
      (node (ref "LED54") (pin "2") (pinfunction "DOUT_2") (pintype "output"))
      (node (ref "LED55") (pin "4") (pinfunction "DIN_4") (pintype "input"))
    )
    (net (code "92") (name "Net-(LED55-DOUT)") (class "Default")
      (node (ref "LED55") (pin "2") (pinfunction "DOUT_2") (pintype "output"))
      (node (ref "LED56") (pin "4") (pinfunction "DIN_4") (pintype "input"))
    )
    (net (code "93") (name "Net-(LED57-DOUT)") (class "Default")
      (node (ref "LED57") (pin "2") (pinfunction "DOUT_2") (pintype "output"))
      (node (ref "LED58") (pin "4") (pinfunction "DIN_4") (pintype "input"))
    )
    (net (code "94") (name "Net-(LED58-DOUT)") (class "Default")
      (node (ref "LED58") (pin "2") (pinfunction "DOUT_2") (pintype "output"))
      (node (ref "LED59") (pin "4") (pinfunction "DIN_4") (pintype "input"))
    )
    (net (code "95") (name "Net-(LED59-DOUT)") (class "Default")
      (node (ref "LED59") (pin "2") (pinfunction "DOUT_2") (pintype "output"))
      (node (ref "LED60") (pin "4") (pinfunction "DIN_4") (pintype "input"))
    )
    (net (code "96") (name "Net-(LED60-DOUT)") (class "Default")
      (node (ref "LED60") (pin "2") (pinfunction "DOUT_2") (pintype "output"))
      (node (ref "LED61") (pin "4") (pinfunction "DIN_4") (pintype "input"))
    )
    (net (code "97") (name "Net-(LED61-DOUT)") (class "Default")
      (node (ref "LED61") (pin "2") (pinfunction "DOUT_2") (pintype "output"))
      (node (ref "LED62") (pin "4") (pinfunction "DIN_4") (pintype "input"))
    )
    (net (code "98") (name "Net-(LED62-DOUT)") (class "Default")
      (node (ref "LED62") (pin "2") (pinfunction "DOUT_2") (pintype "output"))
      (node (ref "LED63") (pin "4") (pinfunction "DIN_4") (pintype "input"))
    )
    (net (code "99") (name "Net-(LED63-DOUT)") (class "Default")
      (node (ref "LED63") (pin "2") (pinfunction "DOUT_2") (pintype "output"))
      (node (ref "LED64") (pin "4") (pinfunction "DIN_4") (pintype "input"))
    )
    (net (code "100") (name "Net-(LED64-DOUT)") (class "Default")
      (node (ref "LED64") (pin "2") (pinfunction "DOUT_2") (pintype "output"))
      (node (ref "LED65") (pin "4") (pinfunction "DIN_4") (pintype "input"))
    )
    (net (code "101") (name "Net-(LED65-DOUT)") (class "Default")
      (node (ref "LED65") (pin "2") (pinfunction "DOUT_2") (pintype "output"))
      (node (ref "LED66") (pin "4") (pinfunction "DIN_4") (pintype "input"))
    )
    (net (code "102") (name "Net-(LED66-DOUT)") (class "Default")
      (node (ref "LED66") (pin "2") (pinfunction "DOUT_2") (pintype "output"))
      (node (ref "LED67") (pin "4") (pinfunction "DIN_4") (pintype "input"))
    )
    (net (code "103") (name "Net-(LED67-DOUT)") (class "Default")
      (node (ref "LED67") (pin "2") (pinfunction "DOUT_2") (pintype "output"))
      (node (ref "LED68") (pin "4") (pinfunction "DIN_4") (pintype "input"))
    )
    (net (code "104") (name "Net-(LED68-DOUT)") (class "Default")
      (node (ref "LED68") (pin "2") (pinfunction "DOUT_2") (pintype "output"))
      (node (ref "LED70") (pin "4") (pinfunction "DIN_4") (pintype "input"))
    )
    (net (code "105") (name "Net-(LED70-DOUT)") (class "Default")
      (node (ref "LED70") (pin "2") (pinfunction "DOUT_2") (pintype "output"))
      (node (ref "LED71") (pin "4") (pinfunction "DIN_4") (pintype "input"))
    )
    (net (code "106") (name "Net-(LED71-DOUT)") (class "Default")
      (node (ref "LED71") (pin "2") (pinfunction "DOUT_2") (pintype "output"))
      (node (ref "LED72") (pin "4") (pinfunction "DIN_4") (pintype "input"))
    )
    (net (code "107") (name "Net-(LED72-DOUT)") (class "Default")
      (node (ref "LED72") (pin "2") (pinfunction "DOUT_2") (pintype "output"))
      (node (ref "LED73") (pin "4") (pinfunction "DIN_4") (pintype "input"))
    )
    (net (code "108") (name "Net-(LED73-DOUT)") (class "Default")
      (node (ref "LED73") (pin "2") (pinfunction "DOUT_2") (pintype "output"))
      (node (ref "LED74") (pin "4") (pinfunction "DIN_4") (pintype "input"))
    )
    (net (code "109") (name "Net-(LED74-DOUT)") (class "Default")
      (node (ref "LED74") (pin "2") (pinfunction "DOUT_2") (pintype "output"))
      (node (ref "LED75") (pin "4") (pinfunction "DIN_4") (pintype "input"))
    )
    (net (code "110") (name "Net-(LED75-DOUT)") (class "Default")
      (node (ref "LED75") (pin "2") (pinfunction "DOUT_2") (pintype "output"))
      (node (ref "LED76") (pin "4") (pinfunction "DIN_4") (pintype "input"))
    )
    (net (code "111") (name "Net-(LED76-DOUT)") (class "Default")
      (node (ref "LED76") (pin "2") (pinfunction "DOUT_2") (pintype "output"))
      (node (ref "LED77") (pin "4") (pinfunction "DIN_4") (pintype "input"))
    )
    (net (code "112") (name "Net-(LED77-DOUT)") (class "Default")
      (node (ref "LED77") (pin "2") (pinfunction "DOUT_2") (pintype "output"))
      (node (ref "LED78") (pin "4") (pinfunction "DIN_4") (pintype "input"))
    )
    (net (code "113") (name "Net-(LED78-DOUT)") (class "Default")
      (node (ref "LED78") (pin "2") (pinfunction "DOUT_2") (pintype "output"))
      (node (ref "LED79") (pin "4") (pinfunction "DIN_4") (pintype "input"))
    )
    (net (code "114") (name "Net-(LED79-DOUT)") (class "Default")
      (node (ref "LED79") (pin "2") (pinfunction "DOUT_2") (pintype "output"))
      (node (ref "LED80") (pin "4") (pinfunction "DIN_4") (pintype "input"))
    )
    (net (code "115") (name "Net-(LED80-DOUT)") (class "Default")
      (node (ref "LED80") (pin "2") (pinfunction "DOUT_2") (pintype "output"))
      (node (ref "LED81") (pin "4") (pinfunction "DIN_4") (pintype "input"))
    )
    (net (code "116") (name "Net-(LED81-DOUT)") (class "Default")
      (node (ref "LED81") (pin "2") (pinfunction "DOUT_2") (pintype "output"))
      (node (ref "LED82") (pin "4") (pinfunction "DIN_4") (pintype "input"))
    )
    (net (code "117") (name "Net-(LED82-DOUT)") (class "Default")
      (node (ref "LED82") (pin "2") (pinfunction "DOUT_2") (pintype "output"))
      (node (ref "LED83") (pin "4") (pinfunction "DIN_4") (pintype "input"))
    )
    (net (code "118") (name "Net-(LED83-DOUT)") (class "Default")
      (node (ref "LED83") (pin "2") (pinfunction "DOUT_2") (pintype "output"))
      (node (ref "LED84") (pin "4") (pinfunction "DIN_4") (pintype "input"))
    )
    (net (code "119") (name "Net-(LED85-DOUT)") (class "Default")
      (node (ref "LED85") (pin "2") (pinfunction "DOUT_2") (pintype "output"))
      (node (ref "LED86") (pin "4") (pinfunction "DIN_4") (pintype "input"))
    )
    (net (code "120") (name "Net-(LED86-DOUT)") (class "Default")
      (node (ref "LED86") (pin "2") (pinfunction "DOUT_2") (pintype "output"))
      (node (ref "LED87") (pin "4") (pinfunction "DIN_4") (pintype "input"))
    )
    (net (code "121") (name "Net-(LED87-DOUT)") (class "Default")
      (node (ref "LED87") (pin "2") (pinfunction "DOUT_2") (pintype "output"))
      (node (ref "LED88") (pin "4") (pinfunction "DIN_4") (pintype "input"))
    )
    (net (code "122") (name "Net-(LED88-DOUT)") (class "Default")
      (node (ref "LED88") (pin "2") (pinfunction "DOUT_2") (pintype "output"))
      (node (ref "LED89") (pin "4") (pinfunction "DIN_4") (pintype "input"))
    )
    (net (code "123") (name "Net-(LED89-DOUT)") (class "Default")
      (node (ref "LED89") (pin "2") (pinfunction "DOUT_2") (pintype "output"))
      (node (ref "LED90") (pin "4") (pinfunction "DIN_4") (pintype "input"))
    )
    (net (code "124") (name "Net-(LED90-DOUT)") (class "Default")
      (node (ref "LED90") (pin "2") (pinfunction "DOUT_2") (pintype "output"))
      (node (ref "LED91") (pin "4") (pinfunction "DIN_4") (pintype "input"))
    )
    (net (code "125") (name "Net-(LED91-DOUT)") (class "Default")
      (node (ref "LED91") (pin "2") (pinfunction "DOUT_2") (pintype "output"))
      (node (ref "LED92") (pin "4") (pinfunction "DIN_4") (pintype "input"))
    )
    (net (code "126") (name "Net-(LED92-DOUT)") (class "Default")
      (node (ref "LED92") (pin "2") (pinfunction "DOUT_2") (pintype "output"))
      (node (ref "LED93") (pin "4") (pinfunction "DIN_4") (pintype "input"))
    )
    (net (code "127") (name "Net-(LED93-DOUT)") (class "Default")
      (node (ref "LED93") (pin "2") (pinfunction "DOUT_2") (pintype "output"))
      (node (ref "LED94") (pin "4") (pinfunction "DIN_4") (pintype "input"))
    )
    (net (code "128") (name "Net-(LED94-DOUT)") (class "Default")
      (node (ref "LED94") (pin "2") (pinfunction "DOUT_2") (pintype "output"))
      (node (ref "LED95") (pin "4") (pinfunction "DIN_4") (pintype "input"))
    )
    (net (code "129") (name "Net-(LED95-DOUT)") (class "Default")
      (node (ref "LED95") (pin "2") (pinfunction "DOUT_2") (pintype "output"))
      (node (ref "LED96") (pin "4") (pinfunction "DIN_4") (pintype "input"))
    )
    (net (code "130") (name "Net-(LED96-DOUT)") (class "Default")
      (node (ref "LED96") (pin "2") (pinfunction "DOUT_2") (pintype "output"))
      (node (ref "LED97") (pin "4") (pinfunction "DIN_4") (pintype "input"))
    )
    (net (code "131") (name "Net-(LED97-DOUT)") (class "Default")
      (node (ref "LED97") (pin "2") (pinfunction "DOUT_2") (pintype "output"))
      (node (ref "LED98") (pin "4") (pinfunction "DIN_4") (pintype "input"))
    )
    (net (code "132") (name "Net-(LED98-DOUT)") (class "Default")
      (node (ref "LED98") (pin "2") (pinfunction "DOUT_2") (pintype "output"))
      (node (ref "LED99") (pin "4") (pinfunction "DIN_4") (pintype "input"))
    )
    (net (code "133") (name "Net-(LED100-DIN)") (class "Default")
      (node (ref "LED100") (pin "4") (pinfunction "DIN_4") (pintype "input"))
      (node (ref "LED99") (pin "2") (pinfunction "DOUT_2") (pintype "output"))
    )
    (net (code "134") (name "Net-(LED100-DOUT)") (class "Default")
      (node (ref "LED100") (pin "2") (pinfunction "DOUT_2") (pintype "output"))
      (node (ref "LED101") (pin "4") (pinfunction "DIN_4") (pintype "input"))
    )
    (net (code "135") (name "Net-(LED101-DOUT)") (class "Default")
      (node (ref "LED101") (pin "2") (pinfunction "DOUT_2") (pintype "output"))
      (node (ref "LED102") (pin "4") (pinfunction "DIN_4") (pintype "input"))
    )
    (net (code "136") (name "Net-(LED102-DOUT)") (class "Default")
      (node (ref "LED102") (pin "2") (pinfunction "DOUT_2") (pintype "output"))
      (node (ref "LED103") (pin "4") (pinfunction "DIN_4") (pintype "input"))
    )
    (net (code "137") (name "Net-(LED103-DOUT)") (class "Default")
      (node (ref "LED103") (pin "2") (pinfunction "DOUT_2") (pintype "output"))
      (node (ref "LED104") (pin "4") (pinfunction "DIN_4") (pintype "input"))
    )
    (net (code "138") (name "Net-(LED104-DOUT)") (class "Default")
      (node (ref "LED104") (pin "2") (pinfunction "DOUT_2") (pintype "output"))
      (node (ref "LED105") (pin "4") (pinfunction "DIN_4") (pintype "input"))
    )
    (net (code "139") (name "Net-(LED105-DOUT)") (class "Default")
      (node (ref "LED105") (pin "2") (pinfunction "DOUT_2") (pintype "output"))
      (node (ref "LED106") (pin "4") (pinfunction "DIN_4") (pintype "input"))
    )
    (net (code "140") (name "Net-(LED106-DOUT)") (class "Default")
      (node (ref "LED106") (pin "2") (pinfunction "DOUT_2") (pintype "output"))
      (node (ref "LED107") (pin "4") (pinfunction "DIN_4") (pintype "input"))
    )
    (net (code "141") (name "Net-(LED107-DOUT)") (class "Default")
      (node (ref "LED107") (pin "2") (pinfunction "DOUT_2") (pintype "output"))
      (node (ref "LED108") (pin "4") (pinfunction "DIN_4") (pintype "input"))
    )
    (net (code "142") (name "Net-(LED108-DOUT)") (class "Default")
      (node (ref "LED108") (pin "2") (pinfunction "DOUT_2") (pintype "output"))
      (node (ref "LED109") (pin "4") (pinfunction "DIN_4") (pintype "input"))
    )
    (net (code "143") (name "Net-(LED109-DOUT)") (class "Default")
      (node (ref "LED109") (pin "2") (pinfunction "DOUT_2") (pintype "output"))
      (node (ref "LED110") (pin "4") (pinfunction "DIN_4") (pintype "input"))
    )
    (net (code "144") (name "Net-(LED110-DOUT)") (class "Default")
      (node (ref "LED110") (pin "2") (pinfunction "DOUT_2") (pintype "output"))
      (node (ref "LED111") (pin "4") (pinfunction "DIN_4") (pintype "input"))
    )
    (net (code "145") (name "Net-(LED111-DOUT)") (class "Default")
      (node (ref "LED111") (pin "2") (pinfunction "DOUT_2") (pintype "output"))
      (node (ref "LED112") (pin "4") (pinfunction "DIN_4") (pintype "input"))
    )
    (net (code "146") (name "Net-(U4-D0)") (class "Default")
      (node (ref "R17") (pin "5") (pinfunction "5_5") (pintype "passive"))
      (node (ref "SW8") (pin "1") (pinfunction "1_1") (pintype "passive"))
      (node (ref "U4") (pin "11") (pinfunction "D0_11") (pintype "input"))
    )
    (net (code "147") (name "Net-(U4-D1)") (class "Default")
      (node (ref "R17") (pin "6") (pinfunction "6_6") (pintype "passive"))
      (node (ref "SW7") (pin "1") (pinfunction "1_1") (pintype "passive"))
      (node (ref "U4") (pin "12") (pinfunction "D1_12") (pintype "input"))
    )
    (net (code "148") (name "Net-(U4-D2)") (class "Default")
      (node (ref "R17") (pin "7") (pinfunction "7_7") (pintype "passive"))
      (node (ref "SW6") (pin "1") (pinfunction "1_1") (pintype "passive"))
      (node (ref "U4") (pin "13") (pinfunction "D2_13") (pintype "input"))
    )
    (net (code "149") (name "Net-(U4-D3)") (class "Default")
      (node (ref "R17") (pin "8") (pinfunction "8_8") (pintype "passive"))
      (node (ref "SW5") (pin "1") (pinfunction "1_1") (pintype "passive"))
      (node (ref "U4") (pin "14") (pinfunction "D3_14") (pintype "input"))
    )
    (net (code "150") (name "Net-(U4-D4)") (class "Default")
      (node (ref "R7") (pin "5") (pinfunction "5_5") (pintype "passive"))
      (node (ref "SW4") (pin "1") (pinfunction "1_1") (pintype "passive"))
      (node (ref "U4") (pin "3") (pinfunction "D4_3") (pintype "input"))
    )
    (net (code "151") (name "Net-(U4-D5)") (class "Default")
      (node (ref "R7") (pin "6") (pinfunction "6_6") (pintype "passive"))
      (node (ref "SW3") (pin "1") (pinfunction "1_1") (pintype "passive"))
      (node (ref "U4") (pin "4") (pinfunction "D5_4") (pintype "input"))
    )
    (net (code "152") (name "Net-(U4-D6)") (class "Default")
      (node (ref "R7") (pin "7") (pinfunction "7_7") (pintype "passive"))
      (node (ref "SW2") (pin "1") (pinfunction "1_1") (pintype "passive"))
      (node (ref "U4") (pin "5") (pinfunction "D6_5") (pintype "input"))
    )
    (net (code "153") (name "Net-(U4-D7)") (class "Default")
      (node (ref "R7") (pin "8") (pinfunction "8_8") (pintype "passive"))
      (node (ref "SW1") (pin "1") (pinfunction "1_1") (pintype "passive"))
      (node (ref "U4") (pin "6") (pinfunction "D7_6") (pintype "input"))
    )
    (net (code "154") (name "Net-(U4-DS)") (class "Default")
      (node (ref "U4") (pin "10") (pinfunction "DS_10") (pintype "input"))
      (node (ref "U5") (pin "9") (pinfunction "Q7_9") (pintype "output"))
    )
    (net (code "155") (name "Net-(U5-D0)") (class "Default")
      (node (ref "R18") (pin "5") (pinfunction "5_5") (pintype "passive"))
      (node (ref "SW16") (pin "1") (pinfunction "1_1") (pintype "passive"))
      (node (ref "U5") (pin "11") (pinfunction "D0_11") (pintype "input"))
    )
    (net (code "156") (name "Net-(U5-D1)") (class "Default")
      (node (ref "R18") (pin "6") (pinfunction "6_6") (pintype "passive"))
      (node (ref "SW15") (pin "1") (pinfunction "1_1") (pintype "passive"))
      (node (ref "U5") (pin "12") (pinfunction "D1_12") (pintype "input"))
    )
    (net (code "157") (name "Net-(U5-D2)") (class "Default")
      (node (ref "R18") (pin "7") (pinfunction "7_7") (pintype "passive"))
      (node (ref "SW14") (pin "1") (pinfunction "1_1") (pintype "passive"))
      (node (ref "U5") (pin "13") (pinfunction "D2_13") (pintype "input"))
    )
    (net (code "158") (name "Net-(U5-D3)") (class "Default")
      (node (ref "R18") (pin "8") (pinfunction "8_8") (pintype "passive"))
      (node (ref "SW13") (pin "1") (pinfunction "1_1") (pintype "passive"))
      (node (ref "U5") (pin "14") (pinfunction "D3_14") (pintype "input"))
    )
    (net (code "159") (name "Net-(U5-D4)") (class "Default")
      (node (ref "R8") (pin "5") (pinfunction "5_5") (pintype "passive"))
      (node (ref "SW12") (pin "1") (pinfunction "1_1") (pintype "passive"))
      (node (ref "U5") (pin "3") (pinfunction "D4_3") (pintype "input"))
    )
    (net (code "160") (name "Net-(U5-D5)") (class "Default")
      (node (ref "R8") (pin "6") (pinfunction "6_6") (pintype "passive"))
      (node (ref "SW11") (pin "1") (pinfunction "1_1") (pintype "passive"))
      (node (ref "U5") (pin "4") (pinfunction "D5_4") (pintype "input"))
    )
    (net (code "161") (name "Net-(U5-D6)") (class "Default")
      (node (ref "R8") (pin "7") (pinfunction "7_7") (pintype "passive"))
      (node (ref "SW10") (pin "1") (pinfunction "1_1") (pintype "passive"))
      (node (ref "U5") (pin "5") (pinfunction "D6_5") (pintype "input"))
    )
    (net (code "162") (name "Net-(U5-D7)") (class "Default")
      (node (ref "R8") (pin "8") (pinfunction "8_8") (pintype "passive"))
      (node (ref "SW9") (pin "1") (pinfunction "1_1") (pintype "passive"))
      (node (ref "U5") (pin "6") (pinfunction "D7_6") (pintype "input"))
    )
    (net (code "163") (name "Net-(U5-DS)") (class "Default")
      (node (ref "U5") (pin "10") (pinfunction "DS_10") (pintype "input"))
      (node (ref "U6") (pin "9") (pinfunction "Q7_9") (pintype "output"))
    )
    (net (code "164") (name "Net-(U6-D0)") (class "Default")
      (node (ref "R19") (pin "5") (pinfunction "5_5") (pintype "passive"))
      (node (ref "SW24") (pin "1") (pinfunction "1_1") (pintype "passive"))
      (node (ref "U6") (pin "11") (pinfunction "D0_11") (pintype "input"))
    )
    (net (code "165") (name "Net-(U6-D1)") (class "Default")
      (node (ref "R19") (pin "6") (pinfunction "6_6") (pintype "passive"))
      (node (ref "SW23") (pin "1") (pinfunction "1_1") (pintype "passive"))
      (node (ref "U6") (pin "12") (pinfunction "D1_12") (pintype "input"))
    )
    (net (code "166") (name "Net-(U6-D2)") (class "Default")
      (node (ref "R19") (pin "7") (pinfunction "7_7") (pintype "passive"))
      (node (ref "SW22") (pin "1") (pinfunction "1_1") (pintype "passive"))
      (node (ref "U6") (pin "13") (pinfunction "D2_13") (pintype "input"))
    )
    (net (code "167") (name "Net-(U6-D3)") (class "Default")
      (node (ref "R19") (pin "8") (pinfunction "8_8") (pintype "passive"))
      (node (ref "SW21") (pin "1") (pinfunction "1_1") (pintype "passive"))
      (node (ref "U6") (pin "14") (pinfunction "D3_14") (pintype "input"))
    )
    (net (code "168") (name "Net-(U6-D4)") (class "Default")
      (node (ref "R9") (pin "5") (pinfunction "5_5") (pintype "passive"))
      (node (ref "SW20") (pin "1") (pinfunction "1_1") (pintype "passive"))
      (node (ref "U6") (pin "3") (pinfunction "D4_3") (pintype "input"))
    )
    (net (code "169") (name "Net-(U6-D5)") (class "Default")
      (node (ref "R9") (pin "6") (pinfunction "6_6") (pintype "passive"))
      (node (ref "SW19") (pin "1") (pinfunction "1_1") (pintype "passive"))
      (node (ref "U6") (pin "4") (pinfunction "D5_4") (pintype "input"))
    )
    (net (code "170") (name "Net-(U6-D6)") (class "Default")
      (node (ref "R9") (pin "7") (pinfunction "7_7") (pintype "passive"))
      (node (ref "SW18") (pin "1") (pinfunction "1_1") (pintype "passive"))
      (node (ref "U6") (pin "5") (pinfunction "D6_5") (pintype "input"))
    )
    (net (code "171") (name "Net-(U6-D7)") (class "Default")
      (node (ref "R9") (pin "8") (pinfunction "8_8") (pintype "passive"))
      (node (ref "SW17") (pin "1") (pinfunction "1_1") (pintype "passive"))
      (node (ref "U6") (pin "6") (pinfunction "D7_6") (pintype "input"))
    )
    (net (code "172") (name "Net-(U6-DS)") (class "Default")
      (node (ref "U6") (pin "10") (pinfunction "DS_10") (pintype "input"))
      (node (ref "U7") (pin "9") (pinfunction "Q7_9") (pintype "output"))
    )
    (net (code "173") (name "Net-(U7-D0)") (class "Default")
      (node (ref "R20") (pin "5") (pinfunction "5_5") (pintype "passive"))
      (node (ref "SW32") (pin "1") (pinfunction "1_1") (pintype "passive"))
      (node (ref "U7") (pin "11") (pinfunction "D0_11") (pintype "input"))
    )
    (net (code "174") (name "Net-(U7-D1)") (class "Default")
      (node (ref "R20") (pin "6") (pinfunction "6_6") (pintype "passive"))
      (node (ref "SW31") (pin "1") (pinfunction "1_1") (pintype "passive"))
      (node (ref "U7") (pin "12") (pinfunction "D1_12") (pintype "input"))
    )
    (net (code "175") (name "Net-(U7-D2)") (class "Default")
      (node (ref "R20") (pin "7") (pinfunction "7_7") (pintype "passive"))
      (node (ref "SW30") (pin "1") (pinfunction "1_1") (pintype "passive"))
      (node (ref "U7") (pin "13") (pinfunction "D2_13") (pintype "input"))
    )
    (net (code "176") (name "Net-(U7-D3)") (class "Default")
      (node (ref "R20") (pin "8") (pinfunction "8_8") (pintype "passive"))
      (node (ref "SW29") (pin "1") (pinfunction "1_1") (pintype "passive"))
      (node (ref "U7") (pin "14") (pinfunction "D3_14") (pintype "input"))
    )
    (net (code "177") (name "Net-(U7-D4)") (class "Default")
      (node (ref "R10") (pin "5") (pinfunction "5_5") (pintype "passive"))
      (node (ref "SW28") (pin "1") (pinfunction "1_1") (pintype "passive"))
      (node (ref "U7") (pin "3") (pinfunction "D4_3") (pintype "input"))
    )
    (net (code "178") (name "Net-(U7-D5)") (class "Default")
      (node (ref "R10") (pin "6") (pinfunction "6_6") (pintype "passive"))
      (node (ref "SW27") (pin "1") (pinfunction "1_1") (pintype "passive"))
      (node (ref "U7") (pin "4") (pinfunction "D5_4") (pintype "input"))
    )
    (net (code "179") (name "Net-(U7-D6)") (class "Default")
      (node (ref "R10") (pin "7") (pinfunction "7_7") (pintype "passive"))
      (node (ref "SW26") (pin "1") (pinfunction "1_1") (pintype "passive"))
      (node (ref "U7") (pin "5") (pinfunction "D6_5") (pintype "input"))
    )
    (net (code "180") (name "Net-(U7-D7)") (class "Default")
      (node (ref "R10") (pin "8") (pinfunction "8_8") (pintype "passive"))
      (node (ref "SW25") (pin "1") (pinfunction "1_1") (pintype "passive"))
      (node (ref "U7") (pin "6") (pinfunction "D7_6") (pintype "input"))
    )
    (net (code "181") (name "Net-(U7-DS)") (class "Default")
      (node (ref "U7") (pin "10") (pinfunction "DS_10") (pintype "input"))
      (node (ref "U8") (pin "9") (pinfunction "Q7_9") (pintype "output"))
    )
    (net (code "182") (name "Net-(U8-D0)") (class "Default")
      (node (ref "R21") (pin "5") (pinfunction "5_5") (pintype "passive"))
      (node (ref "SW40") (pin "1") (pinfunction "1_1") (pintype "passive"))
      (node (ref "U8") (pin "11") (pinfunction "D0_11") (pintype "input"))
    )
    (net (code "183") (name "Net-(U8-D1)") (class "Default")
      (node (ref "R21") (pin "6") (pinfunction "6_6") (pintype "passive"))
      (node (ref "SW39") (pin "1") (pinfunction "1_1") (pintype "passive"))
      (node (ref "U8") (pin "12") (pinfunction "D1_12") (pintype "input"))
    )
    (net (code "184") (name "Net-(U8-D2)") (class "Default")
      (node (ref "R21") (pin "7") (pinfunction "7_7") (pintype "passive"))
      (node (ref "SW38") (pin "1") (pinfunction "1_1") (pintype "passive"))
      (node (ref "U8") (pin "13") (pinfunction "D2_13") (pintype "input"))
    )
    (net (code "185") (name "Net-(U8-D3)") (class "Default")
      (node (ref "R21") (pin "8") (pinfunction "8_8") (pintype "passive"))
      (node (ref "SW37") (pin "1") (pinfunction "1_1") (pintype "passive"))
      (node (ref "U8") (pin "14") (pinfunction "D3_14") (pintype "input"))
    )
    (net (code "186") (name "Net-(U8-D4)") (class "Default")
      (node (ref "R11") (pin "5") (pinfunction "5_5") (pintype "passive"))
      (node (ref "SW36") (pin "1") (pinfunction "1_1") (pintype "passive"))
      (node (ref "U8") (pin "3") (pinfunction "D4_3") (pintype "input"))
    )
    (net (code "187") (name "Net-(U8-D5)") (class "Default")
      (node (ref "R11") (pin "6") (pinfunction "6_6") (pintype "passive"))
      (node (ref "SW35") (pin "1") (pinfunction "1_1") (pintype "passive"))
      (node (ref "U8") (pin "4") (pinfunction "D5_4") (pintype "input"))
    )
    (net (code "188") (name "Net-(U8-D6)") (class "Default")
      (node (ref "R11") (pin "7") (pinfunction "7_7") (pintype "passive"))
      (node (ref "SW34") (pin "1") (pinfunction "1_1") (pintype "passive"))
      (node (ref "U8") (pin "5") (pinfunction "D6_5") (pintype "input"))
    )
    (net (code "189") (name "Net-(U8-D7)") (class "Default")
      (node (ref "R11") (pin "8") (pinfunction "8_8") (pintype "passive"))
      (node (ref "SW33") (pin "1") (pinfunction "1_1") (pintype "passive"))
      (node (ref "U8") (pin "6") (pinfunction "D7_6") (pintype "input"))
    )
    (net (code "190") (name "Net-(U8-DS)") (class "Default")
      (node (ref "U8") (pin "10") (pinfunction "DS_10") (pintype "input"))
      (node (ref "U9") (pin "9") (pinfunction "Q7_9") (pintype "output"))
    )
    (net (code "191") (name "Net-(U9-D0)") (class "Default")
      (node (ref "R22") (pin "5") (pinfunction "5_5") (pintype "passive"))
      (node (ref "SW48") (pin "1") (pinfunction "1_1") (pintype "passive"))
      (node (ref "U9") (pin "11") (pinfunction "D0_11") (pintype "input"))
    )
    (net (code "192") (name "Net-(U9-D1)") (class "Default")
      (node (ref "R22") (pin "6") (pinfunction "6_6") (pintype "passive"))
      (node (ref "SW47") (pin "1") (pinfunction "1_1") (pintype "passive"))
      (node (ref "U9") (pin "12") (pinfunction "D1_12") (pintype "input"))
    )
    (net (code "193") (name "Net-(U9-D2)") (class "Default")
      (node (ref "R22") (pin "7") (pinfunction "7_7") (pintype "passive"))
      (node (ref "SW46") (pin "1") (pinfunction "1_1") (pintype "passive"))
      (node (ref "U9") (pin "13") (pinfunction "D2_13") (pintype "input"))
    )
    (net (code "194") (name "Net-(U9-D3)") (class "Default")
      (node (ref "R22") (pin "8") (pinfunction "8_8") (pintype "passive"))
      (node (ref "SW45") (pin "1") (pinfunction "1_1") (pintype "passive"))
      (node (ref "U9") (pin "14") (pinfunction "D3_14") (pintype "input"))
    )
    (net (code "195") (name "Net-(U9-D4)") (class "Default")
      (node (ref "R12") (pin "5") (pinfunction "5_5") (pintype "passive"))
      (node (ref "SW44") (pin "1") (pinfunction "1_1") (pintype "passive"))
      (node (ref "U9") (pin "3") (pinfunction "D4_3") (pintype "input"))
    )
    (net (code "196") (name "Net-(U9-D5)") (class "Default")
      (node (ref "R12") (pin "6") (pinfunction "6_6") (pintype "passive"))
      (node (ref "SW43") (pin "1") (pinfunction "1_1") (pintype "passive"))
      (node (ref "U9") (pin "4") (pinfunction "D5_4") (pintype "input"))
    )
    (net (code "197") (name "Net-(U9-D6)") (class "Default")
      (node (ref "R12") (pin "7") (pinfunction "7_7") (pintype "passive"))
      (node (ref "SW42") (pin "1") (pinfunction "1_1") (pintype "passive"))
      (node (ref "U9") (pin "5") (pinfunction "D6_5") (pintype "input"))
    )
    (net (code "198") (name "Net-(U9-D7)") (class "Default")
      (node (ref "R12") (pin "8") (pinfunction "8_8") (pintype "passive"))
      (node (ref "SW41") (pin "1") (pinfunction "1_1") (pintype "passive"))
      (node (ref "U9") (pin "6") (pinfunction "D7_6") (pintype "input"))
    )
    (net (code "199") (name "Net-(U10-D0)") (class "Default")
      (node (ref "R23") (pin "5") (pinfunction "5_5") (pintype "passive"))
      (node (ref "SW56") (pin "1") (pinfunction "1_1") (pintype "passive"))
      (node (ref "U10") (pin "11") (pinfunction "D0_11") (pintype "input"))
    )
    (net (code "200") (name "Net-(U10-D1)") (class "Default")
      (node (ref "R23") (pin "6") (pinfunction "6_6") (pintype "passive"))
      (node (ref "SW55") (pin "1") (pinfunction "1_1") (pintype "passive"))
      (node (ref "U10") (pin "12") (pinfunction "D1_12") (pintype "input"))
    )
    (net (code "201") (name "Net-(U10-D2)") (class "Default")
      (node (ref "R23") (pin "7") (pinfunction "7_7") (pintype "passive"))
      (node (ref "SW54") (pin "1") (pinfunction "1_1") (pintype "passive"))
      (node (ref "U10") (pin "13") (pinfunction "D2_13") (pintype "input"))
    )
    (net (code "202") (name "Net-(U10-D3)") (class "Default")
      (node (ref "R23") (pin "8") (pinfunction "8_8") (pintype "passive"))
      (node (ref "SW53") (pin "1") (pinfunction "1_1") (pintype "passive"))
      (node (ref "U10") (pin "14") (pinfunction "D3_14") (pintype "input"))
    )
    (net (code "203") (name "Net-(U10-D4)") (class "Default")
      (node (ref "R13") (pin "5") (pinfunction "5_5") (pintype "passive"))
      (node (ref "SW52") (pin "1") (pinfunction "1_1") (pintype "passive"))
      (node (ref "U10") (pin "3") (pinfunction "D4_3") (pintype "input"))
    )
    (net (code "204") (name "Net-(U10-D5)") (class "Default")
      (node (ref "R13") (pin "6") (pinfunction "6_6") (pintype "passive"))
      (node (ref "SW51") (pin "1") (pinfunction "1_1") (pintype "passive"))
      (node (ref "U10") (pin "4") (pinfunction "D5_4") (pintype "input"))
    )
    (net (code "205") (name "Net-(U10-D6)") (class "Default")
      (node (ref "R13") (pin "7") (pinfunction "7_7") (pintype "passive"))
      (node (ref "SW50") (pin "1") (pinfunction "1_1") (pintype "passive"))
      (node (ref "U10") (pin "5") (pinfunction "D6_5") (pintype "input"))
    )
    (net (code "206") (name "Net-(U10-D7)") (class "Default")
      (node (ref "R13") (pin "8") (pinfunction "8_8") (pintype "passive"))
      (node (ref "SW49") (pin "1") (pinfunction "1_1") (pintype "passive"))
      (node (ref "U10") (pin "6") (pinfunction "D7_6") (pintype "input"))
    )
    (net (code "207") (name "Net-(U10-DS)") (class "Default")
      (node (ref "U10") (pin "10") (pinfunction "DS_10") (pintype "input"))
      (node (ref "U11") (pin "9") (pinfunction "Q7_9") (pintype "output"))
    )
    (net (code "208") (name "Net-(U10-Q7)") (class "Default")
      (node (ref "U10") (pin "9") (pinfunction "Q7_9") (pintype "output"))
      (node (ref "U9") (pin "10") (pinfunction "DS_10") (pintype "input"))
    )
    (net (code "209") (name "Net-(U11-D0)") (class "Default")
      (node (ref "R24") (pin "5") (pinfunction "5_5") (pintype "passive"))
      (node (ref "SW64") (pin "1") (pinfunction "1_1") (pintype "passive"))
      (node (ref "U11") (pin "11") (pinfunction "D0_11") (pintype "input"))
    )
    (net (code "210") (name "Net-(U11-D1)") (class "Default")
      (node (ref "R24") (pin "6") (pinfunction "6_6") (pintype "passive"))
      (node (ref "SW63") (pin "1") (pinfunction "1_1") (pintype "passive"))
      (node (ref "U11") (pin "12") (pinfunction "D1_12") (pintype "input"))
    )
    (net (code "211") (name "Net-(U11-D2)") (class "Default")
      (node (ref "R24") (pin "7") (pinfunction "7_7") (pintype "passive"))
      (node (ref "SW62") (pin "1") (pinfunction "1_1") (pintype "passive"))
      (node (ref "U11") (pin "13") (pinfunction "D2_13") (pintype "input"))
    )
    (net (code "212") (name "Net-(U11-D3)") (class "Default")
      (node (ref "R24") (pin "8") (pinfunction "8_8") (pintype "passive"))
      (node (ref "SW61") (pin "1") (pinfunction "1_1") (pintype "passive"))
      (node (ref "U11") (pin "14") (pinfunction "D3_14") (pintype "input"))
    )
    (net (code "213") (name "Net-(U11-D4)") (class "Default")
      (node (ref "R14") (pin "5") (pinfunction "5_5") (pintype "passive"))
      (node (ref "SW60") (pin "1") (pinfunction "1_1") (pintype "passive"))
      (node (ref "U11") (pin "3") (pinfunction "D4_3") (pintype "input"))
    )
    (net (code "214") (name "Net-(U11-D5)") (class "Default")
      (node (ref "R14") (pin "6") (pinfunction "6_6") (pintype "passive"))
      (node (ref "SW59") (pin "1") (pinfunction "1_1") (pintype "passive"))
      (node (ref "U11") (pin "4") (pinfunction "D5_4") (pintype "input"))
    )
    (net (code "215") (name "Net-(U11-D6)") (class "Default")
      (node (ref "R14") (pin "7") (pinfunction "7_7") (pintype "passive"))
      (node (ref "SW58") (pin "1") (pinfunction "1_1") (pintype "passive"))
      (node (ref "U11") (pin "5") (pinfunction "D6_5") (pintype "input"))
    )
    (net (code "216") (name "Net-(U11-D7)") (class "Default")
      (node (ref "R14") (pin "8") (pinfunction "8_8") (pintype "passive"))
      (node (ref "SW57") (pin "1") (pinfunction "1_1") (pintype "passive"))
      (node (ref "U11") (pin "6") (pinfunction "D7_6") (pintype "input"))
    )
    (net (code "217") (name "Net-(U11-DS)") (class "Default")
      (node (ref "U11") (pin "10") (pinfunction "DS_10") (pintype "input"))
      (node (ref "U12") (pin "9") (pinfunction "Q7_9") (pintype "output"))
    )
    (net (code "218") (name "Net-(U12-D0)") (class "Default")
      (node (ref "R25") (pin "5") (pinfunction "5_5") (pintype "passive"))
      (node (ref "SW72") (pin "1") (pinfunction "1_1") (pintype "passive"))
      (node (ref "U12") (pin "11") (pinfunction "D0_11") (pintype "input"))
    )
    (net (code "219") (name "Net-(U12-D1)") (class "Default")
      (node (ref "R25") (pin "6") (pinfunction "6_6") (pintype "passive"))
      (node (ref "SW71") (pin "1") (pinfunction "1_1") (pintype "passive"))
      (node (ref "U12") (pin "12") (pinfunction "D1_12") (pintype "input"))
    )
    (net (code "220") (name "Net-(U12-D2)") (class "Default")
      (node (ref "R25") (pin "7") (pinfunction "7_7") (pintype "passive"))
      (node (ref "SW70") (pin "1") (pinfunction "1_1") (pintype "passive"))
      (node (ref "U12") (pin "13") (pinfunction "D2_13") (pintype "input"))
    )
    (net (code "221") (name "Net-(U12-D3)") (class "Default")
      (node (ref "R25") (pin "8") (pinfunction "8_8") (pintype "passive"))
      (node (ref "SW69") (pin "1") (pinfunction "1_1") (pintype "passive"))
      (node (ref "U12") (pin "14") (pinfunction "D3_14") (pintype "input"))
    )
    (net (code "222") (name "Net-(U12-D4)") (class "Default")
      (node (ref "R15") (pin "5") (pinfunction "5_5") (pintype "passive"))
      (node (ref "SW68") (pin "1") (pinfunction "1_1") (pintype "passive"))
      (node (ref "U12") (pin "3") (pinfunction "D4_3") (pintype "input"))
    )
    (net (code "223") (name "Net-(U12-D5)") (class "Default")
      (node (ref "R15") (pin "6") (pinfunction "6_6") (pintype "passive"))
      (node (ref "SW67") (pin "1") (pinfunction "1_1") (pintype "passive"))
      (node (ref "U12") (pin "4") (pinfunction "D5_4") (pintype "input"))
    )
    (net (code "224") (name "Net-(U12-D6)") (class "Default")
      (node (ref "R15") (pin "7") (pinfunction "7_7") (pintype "passive"))
      (node (ref "SW66") (pin "1") (pinfunction "1_1") (pintype "passive"))
      (node (ref "U12") (pin "5") (pinfunction "D6_5") (pintype "input"))
    )
    (net (code "225") (name "Net-(U12-D7)") (class "Default")
      (node (ref "R15") (pin "8") (pinfunction "8_8") (pintype "passive"))
      (node (ref "SW65") (pin "1") (pinfunction "1_1") (pintype "passive"))
      (node (ref "U12") (pin "6") (pinfunction "D7_6") (pintype "input"))
    )
    (net (code "226") (name "Net-(U12-DS)") (class "Default")
      (node (ref "U12") (pin "10") (pinfunction "DS_10") (pintype "input"))
      (node (ref "U13") (pin "9") (pinfunction "Q7_9") (pintype "output"))
    )
    (net (code "227") (name "Net-(U13-D0)") (class "Default")
      (node (ref "R26") (pin "5") (pinfunction "5_5") (pintype "passive"))
      (node (ref "SW80") (pin "1") (pinfunction "1_1") (pintype "passive"))
      (node (ref "U13") (pin "11") (pinfunction "D0_11") (pintype "input"))
    )
    (net (code "228") (name "Net-(U13-D1)") (class "Default")
      (node (ref "R26") (pin "6") (pinfunction "6_6") (pintype "passive"))
      (node (ref "SW79") (pin "1") (pinfunction "1_1") (pintype "passive"))
      (node (ref "U13") (pin "12") (pinfunction "D1_12") (pintype "input"))
    )
    (net (code "229") (name "Net-(U13-D2)") (class "Default")
      (node (ref "R26") (pin "7") (pinfunction "7_7") (pintype "passive"))
      (node (ref "SW78") (pin "1") (pinfunction "1_1") (pintype "passive"))
      (node (ref "U13") (pin "13") (pinfunction "D2_13") (pintype "input"))
    )
    (net (code "230") (name "Net-(U13-D3)") (class "Default")
      (node (ref "R26") (pin "8") (pinfunction "8_8") (pintype "passive"))
      (node (ref "SW77") (pin "1") (pinfunction "1_1") (pintype "passive"))
      (node (ref "U13") (pin "14") (pinfunction "D3_14") (pintype "input"))
    )
    (net (code "231") (name "Net-(U13-D4)") (class "Default")
      (node (ref "R16") (pin "5") (pinfunction "5_5") (pintype "passive"))
      (node (ref "SW76") (pin "1") (pinfunction "1_1") (pintype "passive"))
      (node (ref "U13") (pin "3") (pinfunction "D4_3") (pintype "input"))
    )
    (net (code "232") (name "Net-(U13-D5)") (class "Default")
      (node (ref "R16") (pin "6") (pinfunction "6_6") (pintype "passive"))
      (node (ref "SW75") (pin "1") (pinfunction "1_1") (pintype "passive"))
      (node (ref "U13") (pin "4") (pinfunction "D5_4") (pintype "input"))
    )
    (net (code "233") (name "Net-(U13-D6)") (class "Default")
      (node (ref "R16") (pin "7") (pinfunction "7_7") (pintype "passive"))
      (node (ref "SW74") (pin "1") (pinfunction "1_1") (pintype "passive"))
      (node (ref "U13") (pin "5") (pinfunction "D6_5") (pintype "input"))
    )
    (net (code "234") (name "Net-(U13-D7)") (class "Default")
      (node (ref "R16") (pin "8") (pinfunction "8_8") (pintype "passive"))
      (node (ref "SW73") (pin "1") (pinfunction "1_1") (pintype "passive"))
      (node (ref "U13") (pin "6") (pinfunction "D7_6") (pintype "input"))
    )
    (net (code "235") (name "Net-(U14-D0)") (class "Default")
      (node (ref "R31") (pin "5") (pinfunction "5_5") (pintype "passive"))
      (node (ref "SW88") (pin "1") (pinfunction "1_1") (pintype "passive"))
      (node (ref "U14") (pin "11") (pinfunction "D0_11") (pintype "input"))
    )
    (net (code "236") (name "Net-(U14-D1)") (class "Default")
      (node (ref "R31") (pin "6") (pinfunction "6_6") (pintype "passive"))
      (node (ref "SW87") (pin "1") (pinfunction "1_1") (pintype "passive"))
      (node (ref "U14") (pin "12") (pinfunction "D1_12") (pintype "input"))
    )
    (net (code "237") (name "Net-(U14-D2)") (class "Default")
      (node (ref "R31") (pin "7") (pinfunction "7_7") (pintype "passive"))
      (node (ref "SW86") (pin "1") (pinfunction "1_1") (pintype "passive"))
      (node (ref "U14") (pin "13") (pinfunction "D2_13") (pintype "input"))
    )
    (net (code "238") (name "Net-(U14-D3)") (class "Default")
      (node (ref "R31") (pin "8") (pinfunction "8_8") (pintype "passive"))
      (node (ref "SW85") (pin "1") (pinfunction "1_1") (pintype "passive"))
      (node (ref "U14") (pin "14") (pinfunction "D3_14") (pintype "input"))
    )
    (net (code "239") (name "Net-(U14-D4)") (class "Default")
      (node (ref "R27") (pin "5") (pinfunction "5_5") (pintype "passive"))
      (node (ref "SW84") (pin "1") (pinfunction "1_1") (pintype "passive"))
      (node (ref "U14") (pin "3") (pinfunction "D4_3") (pintype "input"))
    )
    (net (code "240") (name "Net-(U14-D5)") (class "Default")
      (node (ref "R27") (pin "6") (pinfunction "6_6") (pintype "passive"))
      (node (ref "SW83") (pin "1") (pinfunction "1_1") (pintype "passive"))
      (node (ref "U14") (pin "4") (pinfunction "D5_4") (pintype "input"))
    )
    (net (code "241") (name "Net-(U14-D6)") (class "Default")
      (node (ref "R27") (pin "7") (pinfunction "7_7") (pintype "passive"))
      (node (ref "SW82") (pin "1") (pinfunction "1_1") (pintype "passive"))
      (node (ref "U14") (pin "5") (pinfunction "D6_5") (pintype "input"))
    )
    (net (code "242") (name "Net-(U14-D7)") (class "Default")
      (node (ref "R27") (pin "8") (pinfunction "8_8") (pintype "passive"))
      (node (ref "SW81") (pin "1") (pinfunction "1_1") (pintype "passive"))
      (node (ref "U14") (pin "6") (pinfunction "D7_6") (pintype "input"))
    )
    (net (code "243") (name "Net-(U14-DS)") (class "Default")
      (node (ref "U14") (pin "10") (pinfunction "DS_10") (pintype "input"))
      (node (ref "U15") (pin "9") (pinfunction "Q7_9") (pintype "output"))
    )
    (net (code "244") (name "Net-(U15-D0)") (class "Default")
      (node (ref "R32") (pin "5") (pinfunction "5_5") (pintype "passive"))
      (node (ref "SW96") (pin "1") (pinfunction "1_1") (pintype "passive"))
      (node (ref "U15") (pin "11") (pinfunction "D0_11") (pintype "input"))
    )
    (net (code "245") (name "Net-(U15-D1)") (class "Default")
      (node (ref "R32") (pin "6") (pinfunction "6_6") (pintype "passive"))
      (node (ref "SW95") (pin "1") (pinfunction "1_1") (pintype "passive"))
      (node (ref "U15") (pin "12") (pinfunction "D1_12") (pintype "input"))
    )
    (net (code "246") (name "Net-(U15-D2)") (class "Default")
      (node (ref "R32") (pin "7") (pinfunction "7_7") (pintype "passive"))
      (node (ref "SW94") (pin "1") (pinfunction "1_1") (pintype "passive"))
      (node (ref "U15") (pin "13") (pinfunction "D2_13") (pintype "input"))
    )
    (net (code "247") (name "Net-(U15-D3)") (class "Default")
      (node (ref "R32") (pin "8") (pinfunction "8_8") (pintype "passive"))
      (node (ref "SW93") (pin "1") (pinfunction "1_1") (pintype "passive"))
      (node (ref "U15") (pin "14") (pinfunction "D3_14") (pintype "input"))
    )
    (net (code "248") (name "Net-(U15-D4)") (class "Default")
      (node (ref "R28") (pin "5") (pinfunction "5_5") (pintype "passive"))
      (node (ref "SW92") (pin "1") (pinfunction "1_1") (pintype "passive"))
      (node (ref "U15") (pin "3") (pinfunction "D4_3") (pintype "input"))
    )
    (net (code "249") (name "Net-(U15-D5)") (class "Default")
      (node (ref "R28") (pin "6") (pinfunction "6_6") (pintype "passive"))
      (node (ref "SW91") (pin "1") (pinfunction "1_1") (pintype "passive"))
      (node (ref "U15") (pin "4") (pinfunction "D5_4") (pintype "input"))
    )
    (net (code "250") (name "Net-(U15-D6)") (class "Default")
      (node (ref "R28") (pin "7") (pinfunction "7_7") (pintype "passive"))
      (node (ref "SW90") (pin "1") (pinfunction "1_1") (pintype "passive"))
      (node (ref "U15") (pin "5") (pinfunction "D6_5") (pintype "input"))
    )
    (net (code "251") (name "Net-(U15-D7)") (class "Default")
      (node (ref "R28") (pin "8") (pinfunction "8_8") (pintype "passive"))
      (node (ref "SW89") (pin "1") (pinfunction "1_1") (pintype "passive"))
      (node (ref "U15") (pin "6") (pinfunction "D7_6") (pintype "input"))
    )
    (net (code "252") (name "Net-(U15-DS)") (class "Default")
      (node (ref "U15") (pin "10") (pinfunction "DS_10") (pintype "input"))
      (node (ref "U16") (pin "9") (pinfunction "Q7_9") (pintype "output"))
    )
    (net (code "253") (name "Net-(U16-D0)") (class "Default")
      (node (ref "R33") (pin "5") (pinfunction "5_5") (pintype "passive"))
      (node (ref "SW104") (pin "1") (pinfunction "1_1") (pintype "passive"))
      (node (ref "U16") (pin "11") (pinfunction "D0_11") (pintype "input"))
    )
    (net (code "254") (name "Net-(U16-D1)") (class "Default")
      (node (ref "R33") (pin "6") (pinfunction "6_6") (pintype "passive"))
      (node (ref "SW103") (pin "1") (pinfunction "1_1") (pintype "passive"))
      (node (ref "U16") (pin "12") (pinfunction "D1_12") (pintype "input"))
    )
    (net (code "255") (name "Net-(U16-D2)") (class "Default")
      (node (ref "R33") (pin "7") (pinfunction "7_7") (pintype "passive"))
      (node (ref "SW102") (pin "1") (pinfunction "1_1") (pintype "passive"))
      (node (ref "U16") (pin "13") (pinfunction "D2_13") (pintype "input"))
    )
    (net (code "256") (name "Net-(U16-D3)") (class "Default")
      (node (ref "R33") (pin "8") (pinfunction "8_8") (pintype "passive"))
      (node (ref "SW101") (pin "1") (pinfunction "1_1") (pintype "passive"))
      (node (ref "U16") (pin "14") (pinfunction "D3_14") (pintype "input"))
    )
    (net (code "257") (name "Net-(U16-D4)") (class "Default")
      (node (ref "R29") (pin "5") (pinfunction "5_5") (pintype "passive"))
      (node (ref "SW100") (pin "1") (pinfunction "1_1") (pintype "passive"))
      (node (ref "U16") (pin "3") (pinfunction "D4_3") (pintype "input"))
    )
    (net (code "258") (name "Net-(U16-D5)") (class "Default")
      (node (ref "R29") (pin "6") (pinfunction "6_6") (pintype "passive"))
      (node (ref "SW99") (pin "1") (pinfunction "1_1") (pintype "passive"))
      (node (ref "U16") (pin "4") (pinfunction "D5_4") (pintype "input"))
    )
    (net (code "259") (name "Net-(U16-D6)") (class "Default")
      (node (ref "R29") (pin "7") (pinfunction "7_7") (pintype "passive"))
      (node (ref "SW98") (pin "1") (pinfunction "1_1") (pintype "passive"))
      (node (ref "U16") (pin "5") (pinfunction "D6_5") (pintype "input"))
    )
    (net (code "260") (name "Net-(U16-D7)") (class "Default")
      (node (ref "R29") (pin "8") (pinfunction "8_8") (pintype "passive"))
      (node (ref "SW97") (pin "1") (pinfunction "1_1") (pintype "passive"))
      (node (ref "U16") (pin "6") (pinfunction "D7_6") (pintype "input"))
    )
    (net (code "261") (name "Net-(U16-DS)") (class "Default")
      (node (ref "U16") (pin "10") (pinfunction "DS_10") (pintype "input"))
      (node (ref "U17") (pin "9") (pinfunction "Q7_9") (pintype "output"))
    )
    (net (code "262") (name "Net-(U17-D0)") (class "Default")
      (node (ref "R34") (pin "5") (pinfunction "5_5") (pintype "passive"))
      (node (ref "SW112") (pin "1") (pinfunction "1_1") (pintype "passive"))
      (node (ref "U17") (pin "11") (pinfunction "D0_11") (pintype "input"))
    )
    (net (code "263") (name "Net-(U17-D1)") (class "Default")
      (node (ref "R34") (pin "6") (pinfunction "6_6") (pintype "passive"))
      (node (ref "SW111") (pin "1") (pinfunction "1_1") (pintype "passive"))
      (node (ref "U17") (pin "12") (pinfunction "D1_12") (pintype "input"))
    )
    (net (code "264") (name "Net-(U17-D2)") (class "Default")
      (node (ref "R34") (pin "7") (pinfunction "7_7") (pintype "passive"))
      (node (ref "SW110") (pin "1") (pinfunction "1_1") (pintype "passive"))
      (node (ref "U17") (pin "13") (pinfunction "D2_13") (pintype "input"))
    )
    (net (code "265") (name "Net-(U17-D3)") (class "Default")
      (node (ref "R34") (pin "8") (pinfunction "8_8") (pintype "passive"))
      (node (ref "SW109") (pin "1") (pinfunction "1_1") (pintype "passive"))
      (node (ref "U17") (pin "14") (pinfunction "D3_14") (pintype "input"))
    )
    (net (code "266") (name "Net-(U17-D4)") (class "Default")
      (node (ref "R30") (pin "5") (pinfunction "5_5") (pintype "passive"))
      (node (ref "SW108") (pin "1") (pinfunction "1_1") (pintype "passive"))
      (node (ref "U17") (pin "3") (pinfunction "D4_3") (pintype "input"))
    )
    (net (code "267") (name "Net-(U17-D5)") (class "Default")
      (node (ref "R30") (pin "6") (pinfunction "6_6") (pintype "passive"))
      (node (ref "SW107") (pin "1") (pinfunction "1_1") (pintype "passive"))
      (node (ref "U17") (pin "4") (pinfunction "D5_4") (pintype "input"))
    )
    (net (code "268") (name "Net-(U17-D6)") (class "Default")
      (node (ref "R30") (pin "7") (pinfunction "7_7") (pintype "passive"))
      (node (ref "SW106") (pin "1") (pinfunction "1_1") (pintype "passive"))
      (node (ref "U17") (pin "5") (pinfunction "D6_5") (pintype "input"))
    )
    (net (code "269") (name "Net-(U17-D7)") (class "Default")
      (node (ref "R30") (pin "8") (pinfunction "8_8") (pintype "passive"))
      (node (ref "SW105") (pin "1") (pinfunction "1_1") (pintype "passive"))
      (node (ref "U17") (pin "6") (pinfunction "D7_6") (pintype "input"))
    )
    (net (code "270") (name "unconnected-(FP1-MNT_1-Pad11)") (class "Default")
      (node (ref "FP1") (pin "11") (pinfunction "MNT_1_11") (pintype "passive+no_connect"))
    )
    (net (code "271") (name "unconnected-(FP1-MNT_2-Pad12)") (class "Default")
      (node (ref "FP1") (pin "12") (pinfunction "MNT_2_12") (pintype "passive+no_connect"))
    )
    (net (code "272") (name "unconnected-(FP1-Pad6)") (class "Default")
      (node (ref "FP1") (pin "6") (pinfunction "6_6") (pintype "passive+no_connect"))
    )
    (net (code "273") (name "unconnected-(FP1-Pad7)") (class "Default")
      (node (ref "FP1") (pin "7") (pinfunction "7_7") (pintype "passive+no_connect"))
    )
    (net (code "274") (name "unconnected-(LED69-DOUT-Pad2)") (class "Default")
      (node (ref "LED69") (pin "2") (pinfunction "DOUT_2") (pintype "output"))
    )
    (net (code "275") (name "unconnected-(LED112-DOUT-Pad2)") (class "Default")
      (node (ref "LED112") (pin "2") (pinfunction "DOUT_2") (pintype "output"))
    )
    (net (code "276") (name "unconnected-(U2-NC-Pad4)") (class "Default")
      (node (ref "U2") (pin "4") (pinfunction "NC_4") (pintype "passive+no_connect"))
    )
    (net (code "277") (name "unconnected-(U3-GPIO0-Pad2)") (class "Default")
      (node (ref "U3") (pin "2") (pinfunction "GPIO0_2") (pintype "passive"))
    )
    (net (code "278") (name "unconnected-(U3-GPIO1-Pad3)") (class "Default")
      (node (ref "U3") (pin "3") (pinfunction "GPIO1_3") (pintype "passive"))
    )
    (net (code "279") (name "unconnected-(U3-GPIO2-Pad4)") (class "Default")
      (node (ref "U3") (pin "4") (pinfunction "GPIO2_4") (pintype "passive"))
    )
    (net (code "280") (name "unconnected-(U3-GPIO3-Pad5)") (class "Default")
      (node (ref "U3") (pin "5") (pinfunction "GPIO3_5") (pintype "passive"))
    )
    (net (code "281") (name "unconnected-(U3-GPIO4-Pad6)") (class "Default")
      (node (ref "U3") (pin "6") (pinfunction "GPIO4_6") (pintype "passive"))
    )
    (net (code "282") (name "unconnected-(U3-GPIO5-Pad7)") (class "Default")
      (node (ref "U3") (pin "7") (pinfunction "GPIO5_7") (pintype "passive"))
    )
    (net (code "283") (name "unconnected-(U3-GPIO6-Pad8)") (class "Default")
      (node (ref "U3") (pin "8") (pinfunction "GPIO6_8") (pintype "passive"))
    )
    (net (code "284") (name "unconnected-(U3-GPIO7-Pad9)") (class "Default")
      (node (ref "U3") (pin "9") (pinfunction "GPIO7_9") (pintype "passive"))
    )
    (net (code "285") (name "unconnected-(U3-GPIO13-Pad16)") (class "Default")
      (node (ref "U3") (pin "16") (pinfunction "GPIO13_16") (pintype "passive"))
    )
    (net (code "286") (name "unconnected-(U3-GPIO14-Pad17)") (class "Default")
      (node (ref "U3") (pin "17") (pinfunction "GPIO14_17") (pintype "passive"))
    )
    (net (code "287") (name "unconnected-(U3-GPIO15-Pad18)") (class "Default")
      (node (ref "U3") (pin "18") (pinfunction "GPIO15_18") (pintype "passive"))
    )
    (net (code "288") (name "unconnected-(U3-GPIO20-Pad31)") (class "Default")
      (node (ref "U3") (pin "31") (pinfunction "GPIO20_31") (pintype "passive"))
    )
    (net (code "289") (name "unconnected-(U3-GPIO21-Pad32)") (class "Default")
      (node (ref "U3") (pin "32") (pinfunction "GPIO21_32") (pintype "passive"))
    )
    (net (code "290") (name "unconnected-(U3-GPIO24-Pad36)") (class "Default")
      (node (ref "U3") (pin "36") (pinfunction "GPIO24_36") (pintype "passive"))
    )
    (net (code "291") (name "unconnected-(U3-GPIO26-Pad38)") (class "Default")
      (node (ref "U3") (pin "38") (pinfunction "GPIO26_38") (pintype "passive"))
    )
    (net (code "292") (name "unconnected-(U3-RUN-Pad26)") (class "Default")
      (node (ref "U3") (pin "26") (pinfunction "RUN_26") (pintype "passive+no_connect"))
    )
    (net (code "293") (name "unconnected-(U3-SWCLK-Pad24)") (class "Default")
      (node (ref "U3") (pin "24") (pinfunction "SWCLK_24") (pintype "passive+no_connect"))
    )
    (net (code "294") (name "unconnected-(U3-SWDIO-Pad25)") (class "Default")
      (node (ref "U3") (pin "25") (pinfunction "SWDIO_25") (pintype "passive+no_connect"))
    )
    (net (code "295") (name "unconnected-(U4-~{Q7}-Pad7)") (class "Default")
      (node (ref "U4") (pin "7") (pinfunction "~{Q7}_7") (pintype "output+no_connect"))
    )
    (net (code "296") (name "unconnected-(U5-~{Q7}-Pad7)") (class "Default")
      (node (ref "U5") (pin "7") (pinfunction "~{Q7}_7") (pintype "output+no_connect"))
    )
    (net (code "297") (name "unconnected-(U6-~{Q7}-Pad7)") (class "Default")
      (node (ref "U6") (pin "7") (pinfunction "~{Q7}_7") (pintype "output+no_connect"))
    )
    (net (code "298") (name "unconnected-(U7-~{Q7}-Pad7)") (class "Default")
      (node (ref "U7") (pin "7") (pinfunction "~{Q7}_7") (pintype "output+no_connect"))
    )
    (net (code "299") (name "unconnected-(U8-~{Q7}-Pad7)") (class "Default")
      (node (ref "U8") (pin "7") (pinfunction "~{Q7}_7") (pintype "output+no_connect"))
    )
    (net (code "300") (name "unconnected-(U9-~{Q7}-Pad7)") (class "Default")
      (node (ref "U9") (pin "7") (pinfunction "~{Q7}_7") (pintype "output+no_connect"))
    )
    (net (code "301") (name "unconnected-(U10-~{Q7}-Pad7)") (class "Default")
      (node (ref "U10") (pin "7") (pinfunction "~{Q7}_7") (pintype "output+no_connect"))
    )
    (net (code "302") (name "unconnected-(U11-~{Q7}-Pad7)") (class "Default")
      (node (ref "U11") (pin "7") (pinfunction "~{Q7}_7") (pintype "output+no_connect"))
    )
    (net (code "303") (name "unconnected-(U12-~{Q7}-Pad7)") (class "Default")
      (node (ref "U12") (pin "7") (pinfunction "~{Q7}_7") (pintype "output+no_connect"))
    )
    (net (code "304") (name "unconnected-(U13-~{Q7}-Pad7)") (class "Default")
      (node (ref "U13") (pin "7") (pinfunction "~{Q7}_7") (pintype "output+no_connect"))
    )
    (net (code "305") (name "unconnected-(U14-~{Q7}-Pad7)") (class "Default")
      (node (ref "U14") (pin "7") (pinfunction "~{Q7}_7") (pintype "output+no_connect"))
    )
    (net (code "306") (name "unconnected-(U15-~{Q7}-Pad7)") (class "Default")
      (node (ref "U15") (pin "7") (pinfunction "~{Q7}_7") (pintype "output+no_connect"))
    )
    (net (code "307") (name "unconnected-(U16-~{Q7}-Pad7)") (class "Default")
      (node (ref "U16") (pin "7") (pinfunction "~{Q7}_7") (pintype "output+no_connect"))
    )
    (net (code "308") (name "unconnected-(U17-DS-Pad10)") (class "Default")
      (node (ref "U17") (pin "10") (pinfunction "DS_10") (pintype "input+no_connect"))
    )
    (net (code "309") (name "unconnected-(U17-~{Q7}-Pad7)") (class "Default")
      (node (ref "U17") (pin "7") (pinfunction "~{Q7}_7") (pintype "output+no_connect"))
    )
  )
)
